# STALO_1.net
KiCad netlist of a schematic drawn in Altium Designer
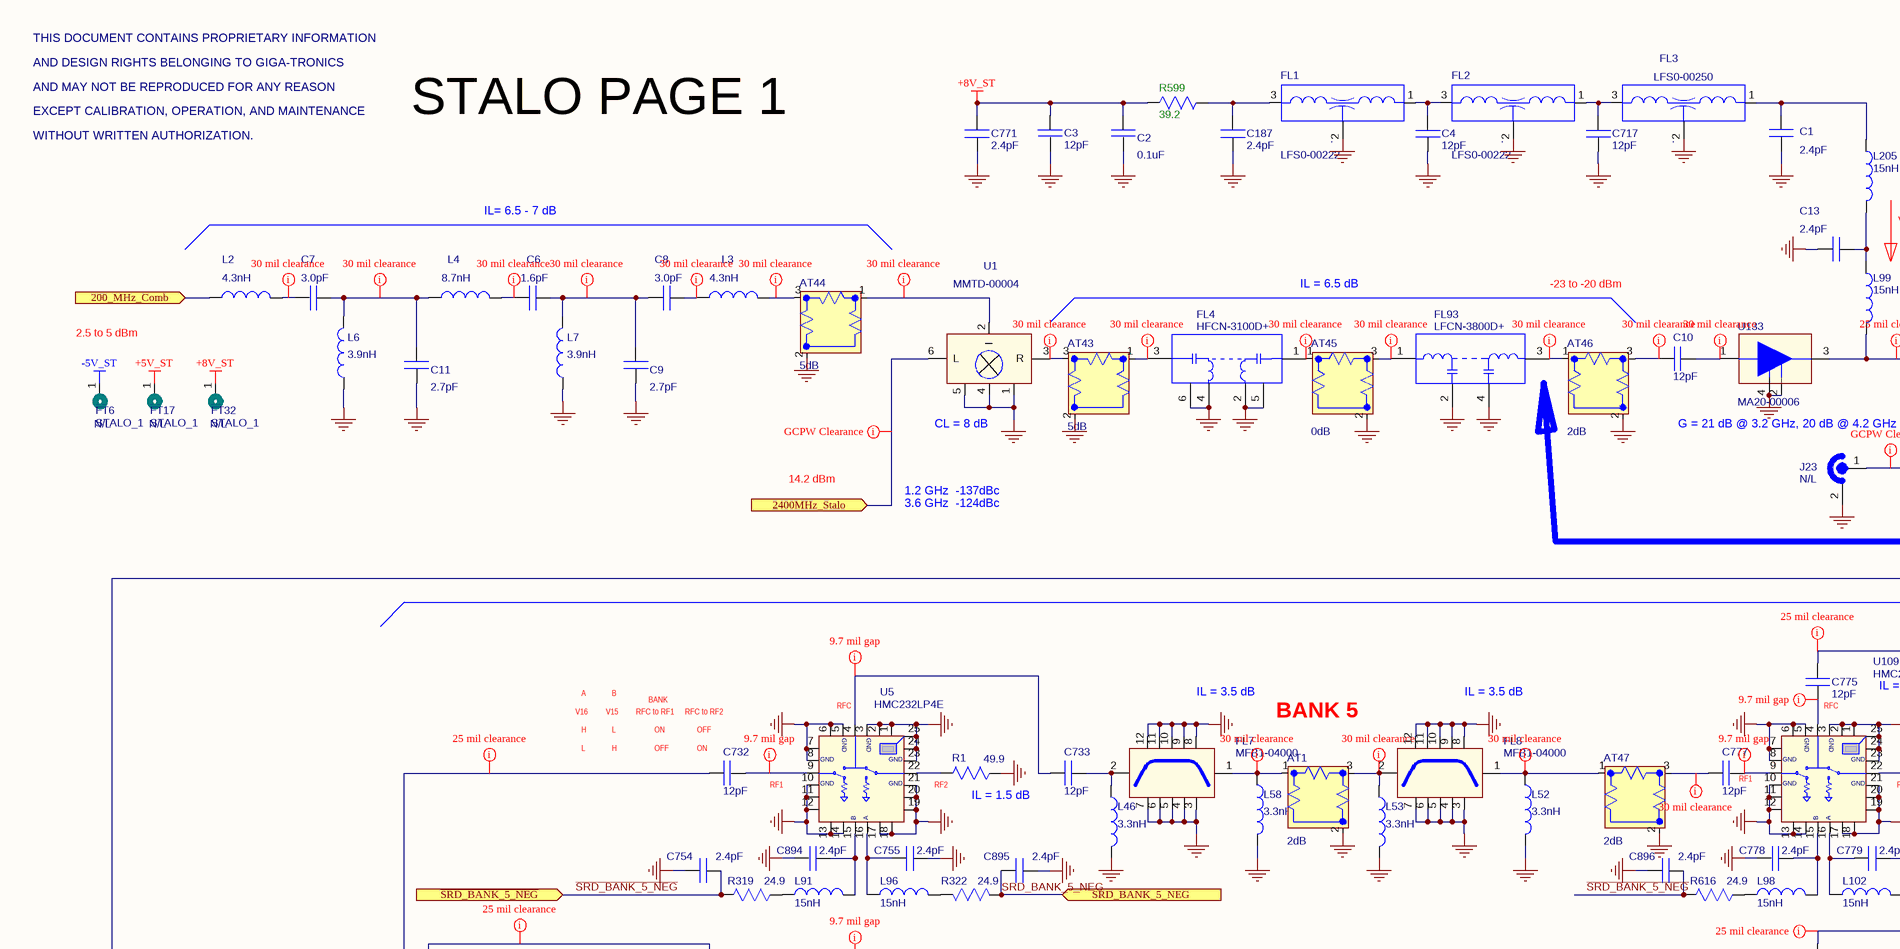
[diagram p0: STALO_1.SchDoc, top left]
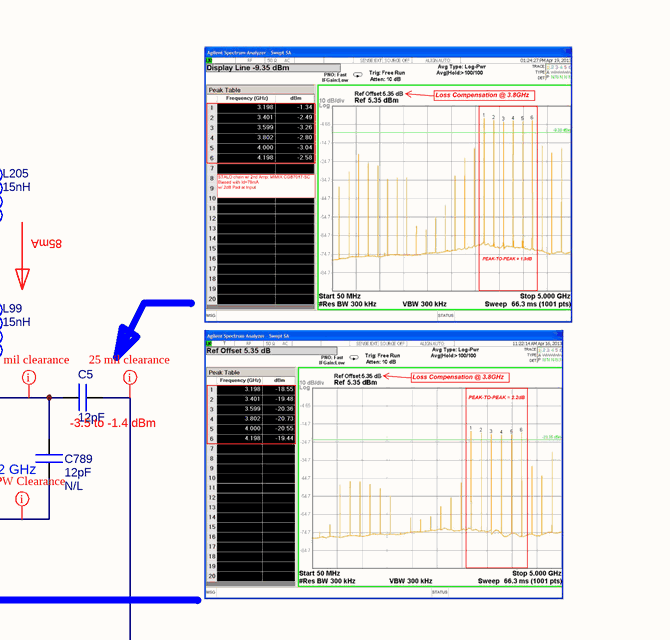
[diagram p1: STALO_1.SchDoc, top right]
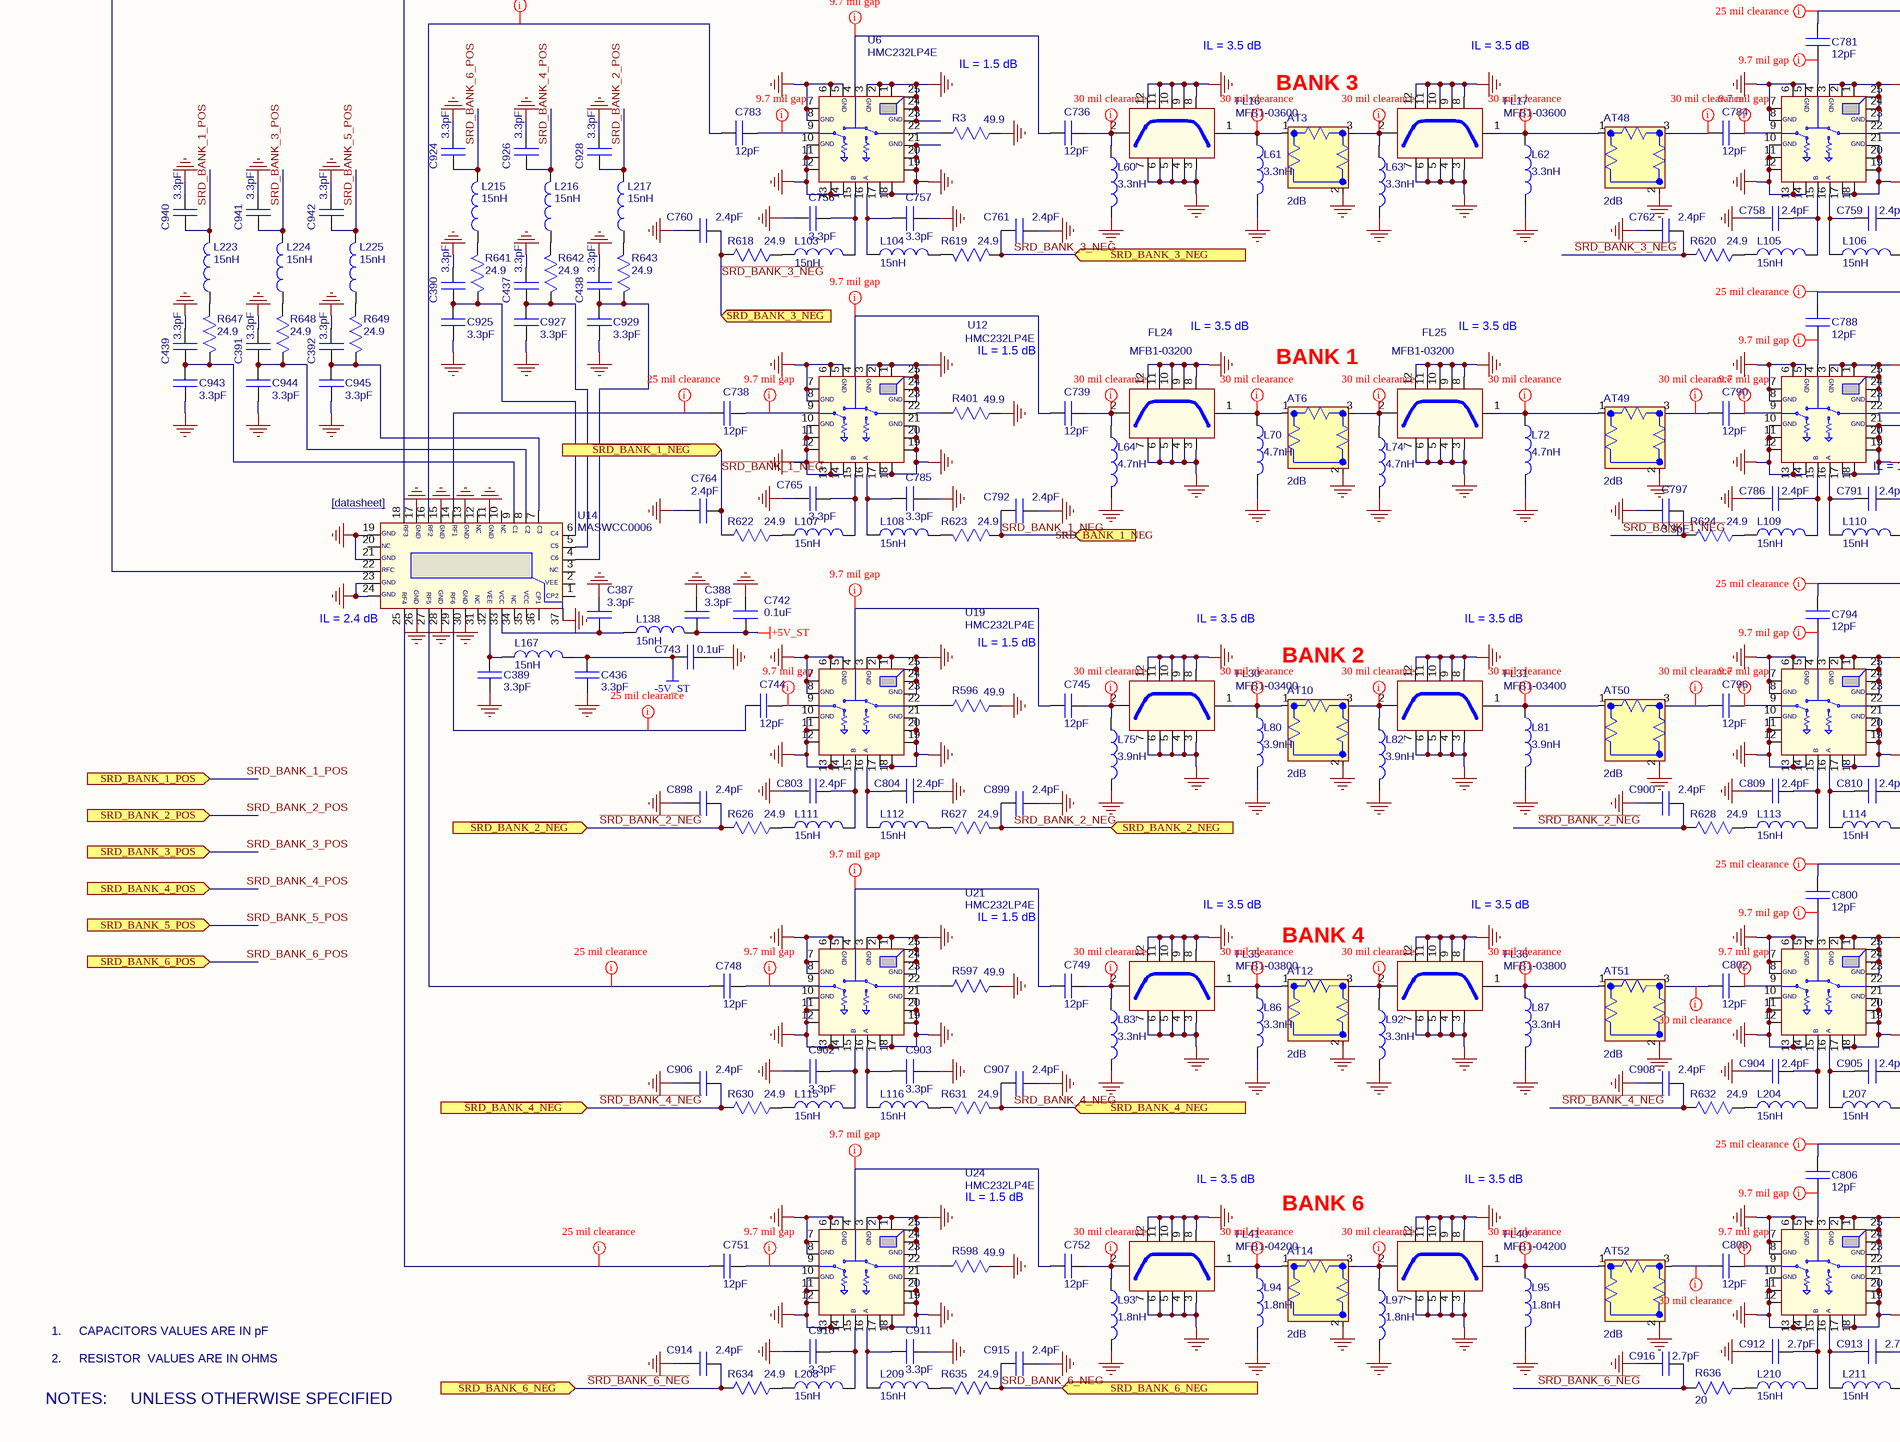
[diagram p2: STALO_1.SchDoc, bottom left]
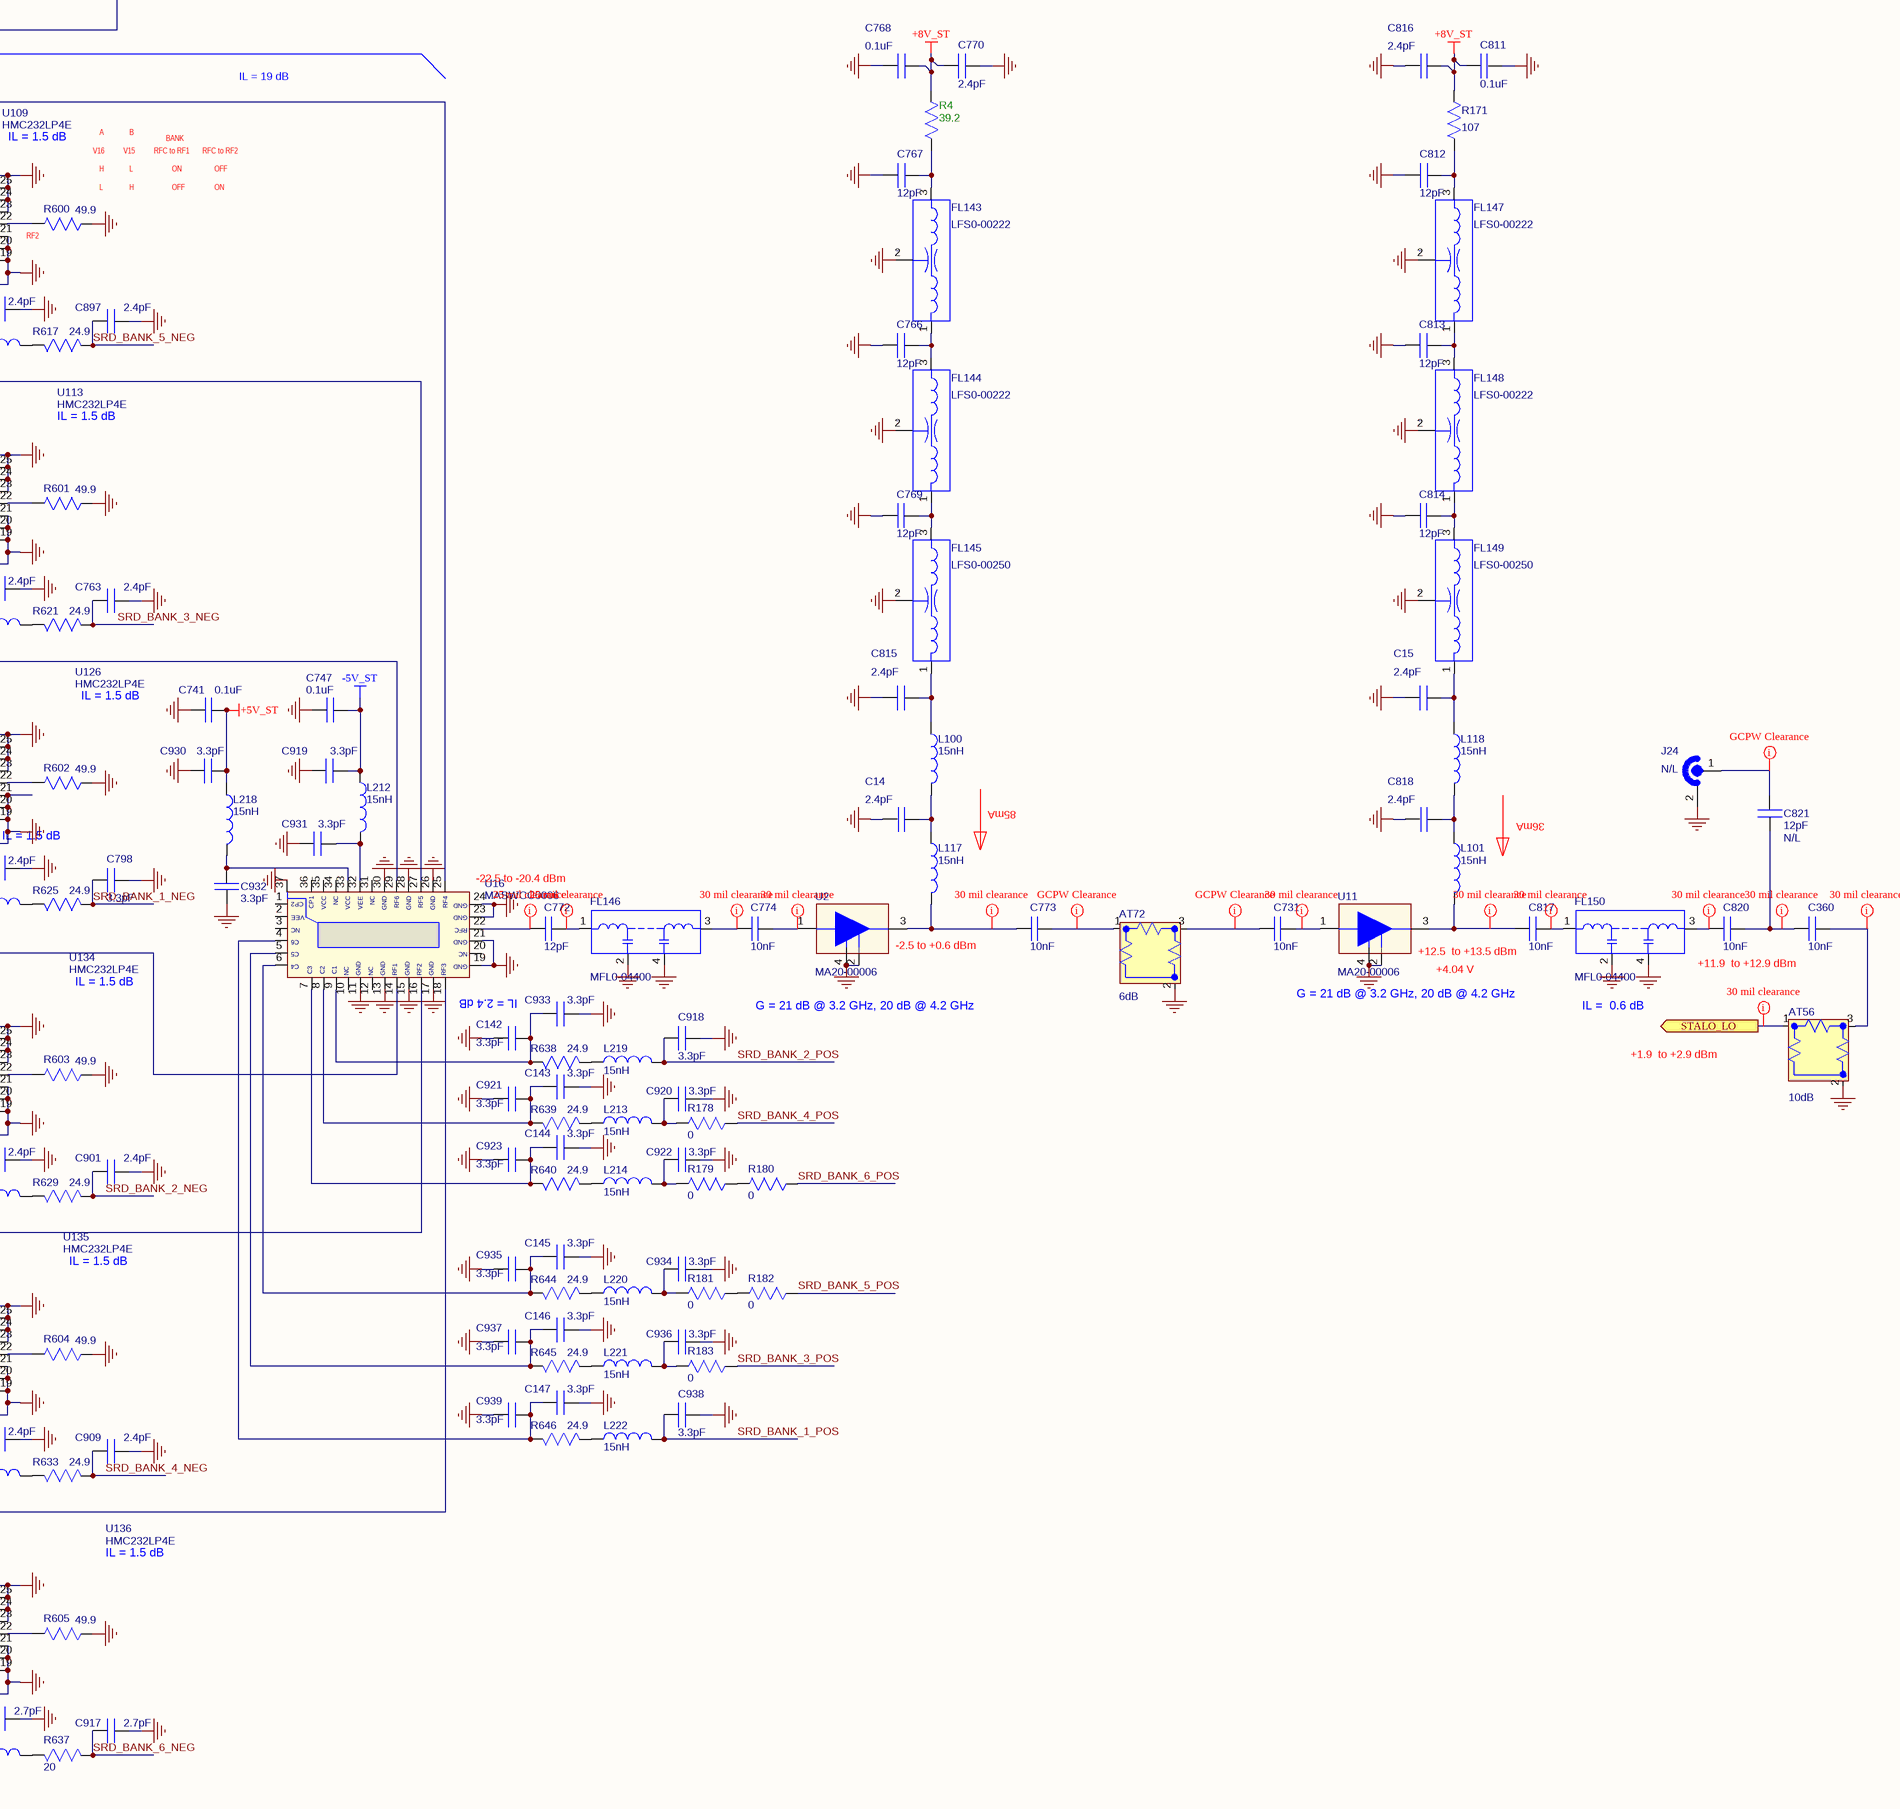
[diagram p3: STALO_1.SchDoc, bottom right]

(export (version "E")
  (design (tool "Eeschema 10.0.6"))
  (components
    (comp (ref "AT1")
      (value "2dB")
      (footprint "ATTN-IMS-0805")
      (description "PAD;CHIP;2dB;+/-.3dB;.08 x .05;50 OHM;FACE DOWN")
      (fields (field (name "APPROVED") "CL"))
      (libsource (lib "Giga-tronics") (part "MPFC-A1002"))
    )
    (comp (ref "AT3")
      (value "2dB")
      (footprint "ATTN-IMS-0805")
      (description "PAD;CHIP;2dB;+/-.3dB;.08 x .05;50 OHM;FACE DOWN")
      (fields (field (name "APPROVED") "CL"))
      (libsource (lib "Giga-tronics") (part "MPFC-A1002"))
    )
    (comp (ref "AT6")
      (value "2dB")
      (footprint "ATTN-IMS-0805")
      (description "PAD;CHIP;2dB;+/-.3dB;.08 x .05;50 OHM;FACE DOWN")
      (fields (field (name "APPROVED") "CL"))
      (libsource (lib "Giga-tronics") (part "MPFC-A1002"))
    )
    (comp (ref "AT10")
      (value "2dB")
      (footprint "ATTN-IMS-0805")
      (description "PAD;CHIP;2dB;+/-.3dB;.08 x .05;50 OHM;FACE DOWN")
      (fields (field (name "APPROVED") "CL"))
      (libsource (lib "Giga-tronics") (part "MPFC-A1002"))
    )
    (comp (ref "AT12")
      (value "2dB")
      (footprint "ATTN-IMS-0805")
      (description "PAD;CHIP;2dB;+/-.3dB;.08 x .05;50 OHM;FACE DOWN")
      (fields (field (name "APPROVED") "CL"))
      (libsource (lib "Giga-tronics") (part "MPFC-A1002"))
    )
    (comp (ref "AT14")
      (value "2dB")
      (footprint "ATTN-IMS-0805")
      (description "PAD;CHIP;2dB;+/-.3dB;.08 x .05;50 OHM;FACE DOWN")
      (fields (field (name "APPROVED") "CL"))
      (libsource (lib "Giga-tronics") (part "MPFC-A1002"))
    )
    (comp (ref "AT43")
      (value "5dB")
      (footprint "ATTN-IMS-0805")
      (description "PAD;CHIP;5dB;+/-.3dB;.08 x .05;50 OHM;FACE DOWN")
      (fields (field (name "APPROVED") "CL"))
      (libsource (lib "Giga-tronics") (part "MPFC-A1005"))
    )
    (comp (ref "AT44")
      (value "5dB")
      (footprint "ATTN-IMS-0805")
      (description "PAD;CHIP;5dB;+/-.3dB;.08 x .05;50 OHM;FACE DOWN")
      (fields (field (name "APPROVED") "CL"))
      (libsource (lib "Giga-tronics") (part "MPFC-A1005"))
    )
    (comp (ref "AT45")
      (value "0dB")
      (footprint "ATTN-IMS-0805")
      (description "PAD;CHIP;0dB;+/-.3dB;.08 x .05;50 OHM;FACE DOWN")
      (fields (field (name "APPROVED") "CL"))
      (libsource (lib "Giga-tronics") (part "MPFC-A1000"))
    )
    (comp (ref "AT46")
      (value "2dB")
      (footprint "ATTN-IMS-0805")
      (description "PAD;CHIP;2dB;+/-.3dB;.08 x .05;50 OHM;FACE DOWN")
      (fields (field (name "APPROVED") "CL"))
      (libsource (lib "Giga-tronics") (part "MPFC-A1002"))
    )
    (comp (ref "AT47")
      (value "2dB")
      (footprint "ATTN-IMS-0805")
      (description "PAD;CHIP;2dB;+/-.3dB;.08 x .05;50 OHM;FACE DOWN")
      (fields (field (name "APPROVED") "CL"))
      (libsource (lib "Giga-tronics") (part "MPFC-A1002"))
    )
    (comp (ref "AT48")
      (value "2dB")
      (footprint "ATTN-IMS-0805")
      (description "PAD;CHIP;2dB;+/-.3dB;.08 x .05;50 OHM;FACE DOWN")
      (fields (field (name "APPROVED") "CL"))
      (libsource (lib "Giga-tronics") (part "MPFC-A1002"))
    )
    (comp (ref "AT49")
      (value "2dB")
      (footprint "ATTN-IMS-0805")
      (description "PAD;CHIP;2dB;+/-.3dB;.08 x .05;50 OHM;FACE DOWN")
      (fields (field (name "APPROVED") "CL"))
      (libsource (lib "Giga-tronics") (part "MPFC-A1002"))
    )
    (comp (ref "AT50")
      (value "2dB")
      (footprint "ATTN-IMS-0805")
      (description "PAD;CHIP;2dB;+/-.3dB;.08 x .05;50 OHM;FACE DOWN")
      (fields (field (name "APPROVED") "CL"))
      (libsource (lib "Giga-tronics") (part "MPFC-A1002"))
    )
    (comp (ref "AT51")
      (value "2dB")
      (footprint "ATTN-IMS-0805")
      (description "PAD;CHIP;2dB;+/-.3dB;.08 x .05;50 OHM;FACE DOWN")
      (fields (field (name "APPROVED") "CL"))
      (libsource (lib "Giga-tronics") (part "MPFC-A1002"))
    )
    (comp (ref "AT52")
      (value "2dB")
      (footprint "ATTN-IMS-0805")
      (description "PAD;CHIP;2dB;+/-.3dB;.08 x .05;50 OHM;FACE DOWN")
      (fields (field (name "APPROVED") "CL"))
      (libsource (lib "Giga-tronics") (part "MPFC-A1002"))
    )
    (comp (ref "AT56")
      (value "10dB")
      (footprint "ATTN-IMS-0805")
      (description "PAD;CHIP;10dB;+/-.3dB;.08 x .05;50 OHM;FACE DOWN")
      (fields (field (name "APPROVED") "CL"))
      (libsource (lib "Giga-tronics") (part "MPFC-A1010"))
    )
    (comp (ref "AT72")
      (value "6dB")
      (footprint "ATTN-IMS-0805")
      (description "PAD;CHIP;6dB;+/-.3dB;.08 x .05;50 OHM;FACE DOWN")
      (fields (field (name "APPROVED") "CL"))
      (libsource (lib "Giga-tronics") (part "MPFC-A1006"))
    )
    (comp (ref "C1")
      (value "2.4pF")
      (footprint "CAP-0402-RF")
      (description "2.4 PF;200V;.05PF;HIGH Q;SMT;CERAMIC;0402")
      (fields (field (name "APPROVED") "CL"))
      (libsource (lib "Giga-tronics") (part "CK41-00024"))
    )
    (comp (ref "C2")
      (value "0.1uF")
      (footprint "CAP-0603-H035-N")
      (description ".1UF;10%;X7R;16V;CHIP;0603")
      (fields (field (name "APPROVED") "CL"))
      (libsource (lib "Giga-tronics") (part "CK45-04100"))
    )
    (comp (ref "C3")
      (value "12pF")
      (footprint "CAP-0402-N")
      (description "12 PF;5%;COG;>50V;CHIP;0402")
      (fields (field (name "APPROVED") "CL"))
      (libsource (lib "Giga-tronics") (part "CK40-00120"))
    )
    (comp (ref "C4")
      (value "12pF")
      (footprint "CAP-0402-N")
      (description "12 PF;5%;COG;>50V;CHIP;0402")
      (fields (field (name "APPROVED") "CL"))
      (libsource (lib "Giga-tronics") (part "CK40-00120"))
    )
    (comp (ref "C5")
      (value "12pF")
      (footprint "CAP-0402-N")
      (description "12 PF;5%;COG;>50V;CHIP;0402")
      (fields (field (name "APPROVED") "CL"))
      (libsource (lib "Giga-tronics") (part "CK40-00120"))
    )
    (comp (ref "C6")
      (value "1.6pF")
      (footprint "CAP-0402-RF")
      (description "1.6 PF;200V;.05PF;HIGH Q;SMT;CERAMIC;0402")
      (fields (field (name "APPROVED") "CL"))
      (libsource (lib "Giga-tronics") (part "CK41-00016"))
    )
    (comp (ref "C7")
      (value "3.0pF")
      (footprint "CAP-0402-RF")
      (description "3.0 PF;200V;.05PF;HIGH Q;SMT;CERAMIC;0402")
      (fields (field (name "APPROVED") "CL"))
      (libsource (lib "Giga-tronics") (part "CK41-00030"))
    )
    (comp (ref "C8")
      (value "3.0pF")
      (footprint "CAP-0402-RF")
      (description "3.0 PF;200V;.05PF;HIGH Q;SMT;CERAMIC;0402")
      (fields (field (name "APPROVED") "CL"))
      (libsource (lib "Giga-tronics") (part "CK41-00030"))
    )
    (comp (ref "C9")
      (value "2.7pF")
      (footprint "CAP-0402-RF")
      (description "2.7 PF;200V;.05PF;HIGH Q;SMT;CERAMIC;0402")
      (fields (field (name "APPROVED") "CL"))
      (libsource (lib "Giga-tronics") (part "CK41-00027"))
    )
    (comp (ref "C10")
      (value "12pF")
      (footprint "CAP-0402-N")
      (description "12 PF;5%;COG;>50V;CHIP;0402")
      (fields (field (name "APPROVED") "CL"))
      (libsource (lib "Giga-tronics") (part "CK40-00120"))
    )
    (comp (ref "C11")
      (value "2.7pF")
      (footprint "CAP-0402-RF")
      (description "2.7 PF;200V;.05PF;HIGH Q;SMT;CERAMIC;0402")
      (fields (field (name "APPROVED") "CL"))
      (libsource (lib "Giga-tronics") (part "CK41-00027"))
    )
    (comp (ref "C13")
      (value "2.4pF")
      (footprint "CAP-0402-RF")
      (description "2.4 PF;200V;.05PF;HIGH Q;SMT;CERAMIC;0402")
      (fields (field (name "APPROVED") "CL"))
      (libsource (lib "Giga-tronics") (part "CK41-00024"))
    )
    (comp (ref "C14")
      (value "2.4pF")
      (footprint "CAP-0402-RF")
      (description "2.4 PF;200V;.05PF;HIGH Q;SMT;CERAMIC;0402")
      (fields (field (name "APPROVED") "CL"))
      (libsource (lib "Giga-tronics") (part "CK41-00024"))
    )
    (comp (ref "C15")
      (value "2.4pF")
      (footprint "CAP-0402-RF")
      (description "2.4 PF;200V;.05PF;HIGH Q;SMT;CERAMIC;0402")
      (fields (field (name "APPROVED") "CL"))
      (libsource (lib "Giga-tronics") (part "CK41-00024"))
    )
    (comp (ref "C142")
      (value "3.3pF")
      (footprint "CAP-0201-N")
      (description "3.3pF;5%;COG;50V;CHIP;0201")
      (fields (field (name "APPROVED") "CL"))
      (libsource (lib "Giga-tronics") (part "CK35-00033"))
    )
    (comp (ref "C143")
      (value "3.3pF")
      (footprint "CAP-0201-N")
      (description "3.3pF;5%;COG;50V;CHIP;0201")
      (fields (field (name "APPROVED") "CL"))
      (libsource (lib "Giga-tronics") (part "CK35-00033"))
    )
    (comp (ref "C144")
      (value "3.3pF")
      (footprint "CAP-0201-N")
      (description "3.3pF;5%;COG;50V;CHIP;0201")
      (fields (field (name "APPROVED") "CL"))
      (libsource (lib "Giga-tronics") (part "CK35-00033"))
    )
    (comp (ref "C145")
      (value "3.3pF")
      (footprint "CAP-0201-N")
      (description "3.3pF;5%;COG;50V;CHIP;0201")
      (fields (field (name "APPROVED") "CL"))
      (libsource (lib "Giga-tronics") (part "CK35-00033"))
    )
    (comp (ref "C146")
      (value "3.3pF")
      (footprint "CAP-0201-N")
      (description "3.3pF;5%;COG;50V;CHIP;0201")
      (fields (field (name "APPROVED") "CL"))
      (libsource (lib "Giga-tronics") (part "CK35-00033"))
    )
    (comp (ref "C147")
      (value "3.3pF")
      (footprint "CAP-0201-N")
      (description "3.3pF;5%;COG;50V;CHIP;0201")
      (fields (field (name "APPROVED") "CL"))
      (libsource (lib "Giga-tronics") (part "CK35-00033"))
    )
    (comp (ref "C187")
      (value "2.4pF")
      (footprint "CAP-0402-RF")
      (description "2.4 PF;200V;.05PF;HIGH Q;SMT;CERAMIC;0402")
      (fields (field (name "APPROVED") "CL"))
      (libsource (lib "Giga-tronics") (part "CK41-00024"))
    )
    (comp (ref "C360")
      (value "10nF")
      (footprint "CAP-0402-N")
      (description "10nF;10%;X7R;16 WVDC;CHIP;0402")
      (fields (field (name "APPROVED") "CL"))
      (libsource (lib "Giga-tronics") (part "TCC3-03100"))
    )
    (comp (ref "C387")
      (value "3.3pF")
      (footprint "CAP-0201-N")
      (description "3.3pF;5%;COG;50V;CHIP;0201")
      (fields (field (name "APPROVED") "CL"))
      (libsource (lib "Giga-tronics") (part "CK35-00033"))
    )
    (comp (ref "C388")
      (value "3.3pF")
      (footprint "CAP-0201-N")
      (description "3.3pF;5%;COG;50V;CHIP;0201")
      (fields (field (name "APPROVED") "CL"))
      (libsource (lib "Giga-tronics") (part "CK35-00033"))
    )
    (comp (ref "C389")
      (value "3.3pF")
      (footprint "CAP-0201-N")
      (description "3.3pF;5%;COG;50V;CHIP;0201")
      (fields (field (name "APPROVED") "CL"))
      (libsource (lib "Giga-tronics") (part "CK35-00033"))
    )
    (comp (ref "C390")
      (value "3.3pF")
      (footprint "CAP-0201-N")
      (description "3.3pF;5%;COG;50V;CHIP;0201")
      (fields (field (name "APPROVED") "CL"))
      (libsource (lib "Giga-tronics") (part "CK35-00033"))
    )
    (comp (ref "C391")
      (value "3.3pF")
      (footprint "CAP-0201-N")
      (description "3.3pF;5%;COG;50V;CHIP;0201")
      (fields (field (name "APPROVED") "CL"))
      (libsource (lib "Giga-tronics") (part "CK35-00033"))
    )
    (comp (ref "C392")
      (value "3.3pF")
      (footprint "CAP-0201-N")
      (description "3.3pF;5%;COG;50V;CHIP;0201")
      (fields (field (name "APPROVED") "CL"))
      (libsource (lib "Giga-tronics") (part "CK35-00033"))
    )
    (comp (ref "C436")
      (value "3.3pF")
      (footprint "CAP-0201-N")
      (description "3.3pF;5%;COG;50V;CHIP;0201")
      (fields (field (name "APPROVED") "CL"))
      (libsource (lib "Giga-tronics") (part "CK35-00033"))
    )
    (comp (ref "C437")
      (value "3.3pF")
      (footprint "CAP-0201-N")
      (description "3.3pF;5%;COG;50V;CHIP;0201")
      (fields (field (name "APPROVED") "CL"))
      (libsource (lib "Giga-tronics") (part "CK35-00033"))
    )
    (comp (ref "C438")
      (value "3.3pF")
      (footprint "CAP-0201-N")
      (description "3.3pF;5%;COG;50V;CHIP;0201")
      (fields (field (name "APPROVED") "CL"))
      (libsource (lib "Giga-tronics") (part "CK35-00033"))
    )
    (comp (ref "C439")
      (value "3.3pF")
      (footprint "CAP-0201-N")
      (description "3.3pF;5%;COG;50V;CHIP;0201")
      (fields (field (name "APPROVED") "CL"))
      (libsource (lib "Giga-tronics") (part "CK35-00033"))
    )
    (comp (ref "C717")
      (value "12pF")
      (footprint "CAP-0402-N")
      (description "12 PF;5%;COG;>50V;CHIP;0402")
      (fields (field (name "APPROVED") "CL"))
      (libsource (lib "Giga-tronics") (part "CK40-00120"))
    )
    (comp (ref "C731")
      (value "10nF")
      (footprint "CAP-0402-N")
      (description "10nF;10%;X7R;16 WVDC;CHIP;0402")
      (fields (field (name "APPROVED") "CL"))
      (libsource (lib "Giga-tronics") (part "TCC3-03100"))
    )
    (comp (ref "C732")
      (value "12pF")
      (footprint "CAP-0402-N")
      (description "12 PF;5%;COG;>50V;CHIP;0402")
      (fields (field (name "APPROVED") "CL"))
      (libsource (lib "Giga-tronics") (part "CK40-00120"))
    )
    (comp (ref "C733")
      (value "12pF")
      (footprint "CAP-0402-N")
      (description "12 PF;5%;COG;>50V;CHIP;0402")
      (fields (field (name "APPROVED") "CL"))
      (libsource (lib "Giga-tronics") (part "CK40-00120"))
    )
    (comp (ref "C736")
      (value "12pF")
      (footprint "CAP-0402-N")
      (description "12 PF;5%;COG;>50V;CHIP;0402")
      (fields (field (name "APPROVED") "CL"))
      (libsource (lib "Giga-tronics") (part "CK40-00120"))
    )
    (comp (ref "C738")
      (value "12pF")
      (footprint "CAP-0402-N")
      (description "12 PF;5%;COG;>50V;CHIP;0402")
      (fields (field (name "APPROVED") "CL"))
      (libsource (lib "Giga-tronics") (part "CK40-00120"))
    )
    (comp (ref "C739")
      (value "12pF")
      (footprint "CAP-0402-N")
      (description "12 PF;5%;COG;>50V;CHIP;0402")
      (fields (field (name "APPROVED") "CL"))
      (libsource (lib "Giga-tronics") (part "CK40-00120"))
    )
    (comp (ref "C741")
      (value "0.1uF")
      (footprint "CAP-0402-N")
      (description ".1 UF,10%;X7R;16V,CHIP;0402")
      (fields (field (name "APPROVED") "CL"))
      (libsource (lib "Giga-tronics") (part "CK40-04100"))
    )
    (comp (ref "C742")
      (value "0.1uF")
      (footprint "CAP-0402-N")
      (description ".1 UF,10%;X7R;16V,CHIP;0402")
      (fields (field (name "APPROVED") "CL"))
      (libsource (lib "Giga-tronics") (part "CK40-04100"))
    )
    (comp (ref "C743")
      (value "0.1uF")
      (footprint "CAP-0402-N")
      (description ".1 UF,10%;X7R;16V,CHIP;0402")
      (fields (field (name "APPROVED") "CL"))
      (libsource (lib "Giga-tronics") (part "CK40-04100"))
    )
    (comp (ref "C744")
      (value "12pF")
      (footprint "CAP-0402-N")
      (description "12 PF;5%;COG;>50V;CHIP;0402")
      (fields (field (name "APPROVED") "CL"))
      (libsource (lib "Giga-tronics") (part "CK40-00120"))
    )
    (comp (ref "C745")
      (value "12pF")
      (footprint "CAP-0402-N")
      (description "12 PF;5%;COG;>50V;CHIP;0402")
      (fields (field (name "APPROVED") "CL"))
      (libsource (lib "Giga-tronics") (part "CK40-00120"))
    )
    (comp (ref "C747")
      (value "0.1uF")
      (footprint "CAP-0402-N")
      (description ".1 UF,10%;X7R;16V,CHIP;0402")
      (fields (field (name "APPROVED") "CL"))
      (libsource (lib "Giga-tronics") (part "CK40-04100"))
    )
    (comp (ref "C748")
      (value "12pF")
      (footprint "CAP-0402-N")
      (description "12 PF;5%;COG;>50V;CHIP;0402")
      (fields (field (name "APPROVED") "CL"))
      (libsource (lib "Giga-tronics") (part "CK40-00120"))
    )
    (comp (ref "C749")
      (value "12pF")
      (footprint "CAP-0402-N")
      (description "12 PF;5%;COG;>50V;CHIP;0402")
      (fields (field (name "APPROVED") "CL"))
      (libsource (lib "Giga-tronics") (part "CK40-00120"))
    )
    (comp (ref "C751")
      (value "12pF")
      (footprint "CAP-0402-N")
      (description "12 PF;5%;COG;>50V;CHIP;0402")
      (fields (field (name "APPROVED") "CL"))
      (libsource (lib "Giga-tronics") (part "CK40-00120"))
    )
    (comp (ref "C752")
      (value "12pF")
      (footprint "CAP-0402-N")
      (description "12 PF;5%;COG;>50V;CHIP;0402")
      (fields (field (name "APPROVED") "CL"))
      (libsource (lib "Giga-tronics") (part "CK40-00120"))
    )
    (comp (ref "C754")
      (value "2.4pF")
      (footprint "CAP-0402-RF")
      (description "2.4 PF;200V;.05PF;HIGH Q;SMT;CERAMIC;0402")
      (fields (field (name "APPROVED") "CL"))
      (libsource (lib "Giga-tronics") (part "CK41-00024"))
    )
    (comp (ref "C755")
      (value "2.4pF")
      (footprint "CAP-0402-RF")
      (description "2.4 PF;200V;.05PF;HIGH Q;SMT;CERAMIC;0402")
      (fields (field (name "APPROVED") "CL"))
      (libsource (lib "Giga-tronics") (part "CK41-00024"))
    )
    (comp (ref "C756")
      (value "3.3pF")
      (footprint "CAP-0201-N")
      (description "3.3pF;5%;COG;50V;CHIP;0201")
      (fields (field (name "APPROVED") "CL"))
      (libsource (lib "Giga-tronics") (part "CK35-00033"))
    )
    (comp (ref "C757")
      (value "3.3pF")
      (footprint "CAP-0201-N")
      (description "3.3pF;5%;COG;50V;CHIP;0201")
      (fields (field (name "APPROVED") "CL"))
      (libsource (lib "Giga-tronics") (part "CK35-00033"))
    )
    (comp (ref "C758")
      (value "2.4pF")
      (footprint "CAP-0402-RF")
      (description "2.4 PF;200V;.05PF;HIGH Q;SMT;CERAMIC;0402")
      (fields (field (name "APPROVED") "CL"))
      (libsource (lib "Giga-tronics") (part "CK41-00024"))
    )
    (comp (ref "C759")
      (value "2.4pF")
      (footprint "CAP-0402-RF")
      (description "2.4 PF;200V;.05PF;HIGH Q;SMT;CERAMIC;0402")
      (fields (field (name "APPROVED") "CL"))
      (libsource (lib "Giga-tronics") (part "CK41-00024"))
    )
    (comp (ref "C760")
      (value "2.4pF")
      (footprint "CAP-0402-RF")
      (description "2.4 PF;200V;.05PF;HIGH Q;SMT;CERAMIC;0402")
      (fields (field (name "APPROVED") "CL"))
      (libsource (lib "Giga-tronics") (part "CK41-00024"))
    )
    (comp (ref "C761")
      (value "2.4pF")
      (footprint "CAP-0402-RF")
      (description "2.4 PF;200V;.05PF;HIGH Q;SMT;CERAMIC;0402")
      (fields (field (name "APPROVED") "CL"))
      (libsource (lib "Giga-tronics") (part "CK41-00024"))
    )
    (comp (ref "C762")
      (value "2.4pF")
      (footprint "CAP-0402-RF")
      (description "2.4 PF;200V;.05PF;HIGH Q;SMT;CERAMIC;0402")
      (fields (field (name "APPROVED") "CL"))
      (libsource (lib "Giga-tronics") (part "CK41-00024"))
    )
    (comp (ref "C763")
      (value "2.4pF")
      (footprint "CAP-0402-RF")
      (description "2.4 PF;200V;.05PF;HIGH Q;SMT;CERAMIC;0402")
      (fields (field (name "APPROVED") "CL"))
      (libsource (lib "Giga-tronics") (part "CK41-00024"))
    )
    (comp (ref "C764")
      (value "2.4pF")
      (footprint "CAP-0402-RF")
      (description "2.4 PF;200V;.05PF;HIGH Q;SMT;CERAMIC;0402")
      (fields (field (name "APPROVED") "CL"))
      (libsource (lib "Giga-tronics") (part "CK41-00024"))
    )
    (comp (ref "C765")
      (value "3.3pF")
      (footprint "CAP-0201-N")
      (description "3.3pF;5%;COG;50V;CHIP;0201")
      (fields (field (name "APPROVED") "CL"))
      (libsource (lib "Giga-tronics") (part "CK35-00033"))
    )
    (comp (ref "C766")
      (value "12pF")
      (footprint "CAP-0402-N")
      (description "12 PF;5%;COG;>50V;CHIP;0402")
      (fields (field (name "APPROVED") "CL"))
      (libsource (lib "Giga-tronics") (part "CK40-00120"))
    )
    (comp (ref "C767")
      (value "12pF")
      (footprint "CAP-0402-N")
      (description "12 PF;5%;COG;>50V;CHIP;0402")
      (fields (field (name "APPROVED") "CL"))
      (libsource (lib "Giga-tronics") (part "CK40-00120"))
    )
    (comp (ref "C768")
      (value "0.1uF")
      (footprint "CAP-0603-H035-N")
      (description ".1UF;10%;X7R;16V;CHIP;0603")
      (fields (field (name "APPROVED") "CL"))
      (libsource (lib "Giga-tronics") (part "CK45-04100"))
    )
    (comp (ref "C769")
      (value "12pF")
      (footprint "CAP-0402-N")
      (description "12 PF;5%;COG;>50V;CHIP;0402")
      (fields (field (name "APPROVED") "CL"))
      (libsource (lib "Giga-tronics") (part "CK40-00120"))
    )
    (comp (ref "C770")
      (value "2.4pF")
      (footprint "CAP-0402-RF")
      (description "2.4 PF;200V;.05PF;HIGH Q;SMT;CERAMIC;0402")
      (fields (field (name "APPROVED") "CL"))
      (libsource (lib "Giga-tronics") (part "CK41-00024"))
    )
    (comp (ref "C771")
      (value "2.4pF")
      (footprint "CAP-0402-RF")
      (description "2.4 PF;200V;.05PF;HIGH Q;SMT;CERAMIC;0402")
      (fields (field (name "APPROVED") "CL"))
      (libsource (lib "Giga-tronics") (part "CK41-00024"))
    )
    (comp (ref "C772")
      (value "12pF")
      (footprint "CAP-0402-N")
      (description "12 PF;5%;COG;>50V;CHIP;0402")
      (fields (field (name "APPROVED") "CL"))
      (libsource (lib "Giga-tronics") (part "CK40-00120"))
    )
    (comp (ref "C773")
      (value "10nF")
      (footprint "CAP-0402-N")
      (description "10nF;10%;X7R;16 WVDC;CHIP;0402")
      (fields (field (name "APPROVED") "CL"))
      (libsource (lib "Giga-tronics") (part "TCC3-03100"))
    )
    (comp (ref "C774")
      (value "10nF")
      (footprint "CAP-0402-N")
      (description "10nF;10%;X7R;16 WVDC;CHIP;0402")
      (fields (field (name "APPROVED") "CL"))
      (libsource (lib "Giga-tronics") (part "TCC3-03100"))
    )
    (comp (ref "C775")
      (value "12pF")
      (footprint "CAP-0402-N")
      (description "12 PF;5%;COG;>50V;CHIP;0402")
      (fields (field (name "APPROVED") "CL"))
      (libsource (lib "Giga-tronics") (part "CK40-00120"))
    )
    (comp (ref "C777")
      (value "12pF")
      (footprint "CAP-0402-N")
      (description "12 PF;5%;COG;>50V;CHIP;0402")
      (fields (field (name "APPROVED") "CL"))
      (libsource (lib "Giga-tronics") (part "CK40-00120"))
    )
    (comp (ref "C778")
      (value "2.4pF")
      (footprint "CAP-0402-RF")
      (description "2.4 PF;200V;.05PF;HIGH Q;SMT;CERAMIC;0402")
      (fields (field (name "APPROVED") "CL"))
      (libsource (lib "Giga-tronics") (part "CK41-00024"))
    )
    (comp (ref "C779")
      (value "2.4pF")
      (footprint "CAP-0402-RF")
      (description "2.4 PF;200V;.05PF;HIGH Q;SMT;CERAMIC;0402")
      (fields (field (name "APPROVED") "CL"))
      (libsource (lib "Giga-tronics") (part "CK41-00024"))
    )
    (comp (ref "C781")
      (value "12pF")
      (footprint "CAP-0402-N")
      (description "12 PF;5%;COG;>50V;CHIP;0402")
      (fields (field (name "APPROVED") "CL"))
      (libsource (lib "Giga-tronics") (part "CK40-00120"))
    )
    (comp (ref "C783")
      (value "12pF")
      (footprint "CAP-0402-N")
      (description "12 PF;5%;COG;>50V;CHIP;0402")
      (fields (field (name "APPROVED") "CL"))
      (libsource (lib "Giga-tronics") (part "CK40-00120"))
    )
    (comp (ref "C784")
      (value "12pF")
      (footprint "CAP-0402-N")
      (description "12 PF;5%;COG;>50V;CHIP;0402")
      (fields (field (name "APPROVED") "CL"))
      (libsource (lib "Giga-tronics") (part "CK40-00120"))
    )
    (comp (ref "C785")
      (value "3.3pF")
      (footprint "CAP-0201-N")
      (description "3.3pF;5%;COG;50V;CHIP;0201")
      (fields (field (name "APPROVED") "CL"))
      (libsource (lib "Giga-tronics") (part "CK35-00033"))
    )
    (comp (ref "C786")
      (value "2.4pF")
      (footprint "CAP-0402-RF")
      (description "2.4 PF;200V;.05PF;HIGH Q;SMT;CERAMIC;0402")
      (fields (field (name "APPROVED") "CL"))
      (libsource (lib "Giga-tronics") (part "CK41-00024"))
    )
    (comp (ref "C788")
      (value "12pF")
      (footprint "CAP-0402-N")
      (description "12 PF;5%;COG;>50V;CHIP;0402")
      (fields (field (name "APPROVED") "CL"))
      (libsource (lib "Giga-tronics") (part "CK40-00120"))
    )
    (comp (ref "C789")
      (value "12pF")
      (footprint "CAP-0402-N")
      (description "12 PF;5%;COG;>50V;CHIP;0402")
      (fields (field (name "NOLOAD") "N/L") (field (name "APPROVED") "CL"))
      (libsource (lib "Giga-tronics") (part "CK40-00120"))
    )
    (comp (ref "C790")
      (value "12pF")
      (footprint "CAP-0402-N")
      (description "12 PF;5%;COG;>50V;CHIP;0402")
      (fields (field (name "APPROVED") "CL"))
      (libsource (lib "Giga-tronics") (part "CK40-00120"))
    )
    (comp (ref "C791")
      (value "2.4pF")
      (footprint "CAP-0402-RF")
      (description "2.4 PF;200V;.05PF;HIGH Q;SMT;CERAMIC;0402")
      (fields (field (name "APPROVED") "CL"))
      (libsource (lib "Giga-tronics") (part "CK41-00024"))
    )
    (comp (ref "C792")
      (value "2.4pF")
      (footprint "CAP-0402-RF")
      (description "2.4 PF;200V;.05PF;HIGH Q;SMT;CERAMIC;0402")
      (fields (field (name "APPROVED") "CL"))
      (libsource (lib "Giga-tronics") (part "CK41-00024"))
    )
    (comp (ref "C794")
      (value "12pF")
      (footprint "CAP-0402-N")
      (description "12 PF;5%;COG;>50V;CHIP;0402")
      (fields (field (name "APPROVED") "CL"))
      (libsource (lib "Giga-tronics") (part "CK40-00120"))
    )
    (comp (ref "C796")
      (value "12pF")
      (footprint "CAP-0402-N")
      (description "12 PF;5%;COG;>50V;CHIP;0402")
      (fields (field (name "APPROVED") "CL"))
      (libsource (lib "Giga-tronics") (part "CK40-00120"))
    )
    (comp (ref "C797")
      (value "3.3pF")
      (footprint "CAP-0201-N")
      (description "3.3pF;5%;COG;50V;CHIP;0201")
      (fields (field (name "APPROVED") "CL"))
      (libsource (lib "Giga-tronics") (part "CK35-00033"))
    )
    (comp (ref "C798")
      (value "3.3pF")
      (footprint "CAP-0201-N")
      (description "3.3pF;5%;COG;50V;CHIP;0201")
      (fields (field (name "APPROVED") "CL"))
      (libsource (lib "Giga-tronics") (part "CK35-00033"))
    )
    (comp (ref "C800")
      (value "12pF")
      (footprint "CAP-0402-N")
      (description "12 PF;5%;COG;>50V;CHIP;0402")
      (fields (field (name "APPROVED") "CL"))
      (libsource (lib "Giga-tronics") (part "CK40-00120"))
    )
    (comp (ref "C802")
      (value "12pF")
      (footprint "CAP-0402-N")
      (description "12 PF;5%;COG;>50V;CHIP;0402")
      (fields (field (name "APPROVED") "CL"))
      (libsource (lib "Giga-tronics") (part "CK40-00120"))
    )
    (comp (ref "C803")
      (value "2.4pF")
      (footprint "CAP-0402-RF")
      (description "2.4 PF;200V;.05PF;HIGH Q;SMT;CERAMIC;0402")
      (fields (field (name "APPROVED") "CL"))
      (libsource (lib "Giga-tronics") (part "CK41-00024"))
    )
    (comp (ref "C804")
      (value "2.4pF")
      (footprint "CAP-0402-RF")
      (description "2.4 PF;200V;.05PF;HIGH Q;SMT;CERAMIC;0402")
      (fields (field (name "APPROVED") "CL"))
      (libsource (lib "Giga-tronics") (part "CK41-00024"))
    )
    (comp (ref "C806")
      (value "12pF")
      (footprint "CAP-0402-N")
      (description "12 PF;5%;COG;>50V;CHIP;0402")
      (fields (field (name "APPROVED") "CL"))
      (libsource (lib "Giga-tronics") (part "CK40-00120"))
    )
    (comp (ref "C808")
      (value "12pF")
      (footprint "CAP-0402-N")
      (description "12 PF;5%;COG;>50V;CHIP;0402")
      (fields (field (name "APPROVED") "CL"))
      (libsource (lib "Giga-tronics") (part "CK40-00120"))
    )
    (comp (ref "C809")
      (value "2.4pF")
      (footprint "CAP-0402-RF")
      (description "2.4 PF;200V;.05PF;HIGH Q;SMT;CERAMIC;0402")
      (fields (field (name "APPROVED") "CL"))
      (libsource (lib "Giga-tronics") (part "CK41-00024"))
    )
    (comp (ref "C810")
      (value "2.4pF")
      (footprint "CAP-0402-RF")
      (description "2.4 PF;200V;.05PF;HIGH Q;SMT;CERAMIC;0402")
      (fields (field (name "APPROVED") "CL"))
      (libsource (lib "Giga-tronics") (part "CK41-00024"))
    )
    (comp (ref "C811")
      (value "0.1uF")
      (footprint "CAP-0603-H035-N")
      (description ".1UF;10%;X7R;16V;CHIP;0603")
      (fields (field (name "APPROVED") "CL"))
      (libsource (lib "Giga-tronics") (part "CK45-04100"))
    )
    (comp (ref "C812")
      (value "12pF")
      (footprint "CAP-0402-N")
      (description "12 PF;5%;COG;>50V;CHIP;0402")
      (fields (field (name "APPROVED") "CL"))
      (libsource (lib "Giga-tronics") (part "CK40-00120"))
    )
    (comp (ref "C813")
      (value "12pF")
      (footprint "CAP-0402-N")
      (description "12 PF;5%;COG;>50V;CHIP;0402")
      (fields (field (name "APPROVED") "CL"))
      (libsource (lib "Giga-tronics") (part "CK40-00120"))
    )
    (comp (ref "C814")
      (value "12pF")
      (footprint "CAP-0402-N")
      (description "12 PF;5%;COG;>50V;CHIP;0402")
      (fields (field (name "APPROVED") "CL"))
      (libsource (lib "Giga-tronics") (part "CK40-00120"))
    )
    (comp (ref "C815")
      (value "2.4pF")
      (footprint "CAP-0402-RF")
      (description "2.4 PF;200V;.05PF;HIGH Q;SMT;CERAMIC;0402")
      (fields (field (name "APPROVED") "CL"))
      (libsource (lib "Giga-tronics") (part "CK41-00024"))
    )
    (comp (ref "C816")
      (value "2.4pF")
      (footprint "CAP-0402-RF")
      (description "2.4 PF;200V;.05PF;HIGH Q;SMT;CERAMIC;0402")
      (fields (field (name "APPROVED") "CL"))
      (libsource (lib "Giga-tronics") (part "CK41-00024"))
    )
    (comp (ref "C817")
      (value "10nF")
      (footprint "CAP-0402-N")
      (description "10nF;10%;X7R;16 WVDC;CHIP;0402")
      (fields (field (name "APPROVED") "CL"))
      (libsource (lib "Giga-tronics") (part "TCC3-03100"))
    )
    (comp (ref "C818")
      (value "2.4pF")
      (footprint "CAP-0402-RF")
      (description "2.4 PF;200V;.05PF;HIGH Q;SMT;CERAMIC;0402")
      (fields (field (name "APPROVED") "CL"))
      (libsource (lib "Giga-tronics") (part "CK41-00024"))
    )
    (comp (ref "C820")
      (value "10nF")
      (footprint "CAP-0402-N")
      (description "10nF;10%;X7R;16 WVDC;CHIP;0402")
      (fields (field (name "APPROVED") "CL"))
      (libsource (lib "Giga-tronics") (part "TCC3-03100"))
    )
    (comp (ref "C821")
      (value "12pF")
      (footprint "CAP-0402-N")
      (description "12 PF;5%;COG;>50V;CHIP;0402")
      (fields (field (name "NOLOAD") "N/L") (field (name "APPROVED") "CL"))
      (libsource (lib "Giga-tronics") (part "CK40-00120"))
    )
    (comp (ref "C894")
      (value "2.4pF")
      (footprint "CAP-0402-RF")
      (description "2.4 PF;200V;.05PF;HIGH Q;SMT;CERAMIC;0402")
      (fields (field (name "APPROVED") "CL"))
      (libsource (lib "Giga-tronics") (part "CK41-00024"))
    )
    (comp (ref "C895")
      (value "2.4pF")
      (footprint "CAP-0402-RF")
      (description "2.4 PF;200V;.05PF;HIGH Q;SMT;CERAMIC;0402")
      (fields (field (name "APPROVED") "CL"))
      (libsource (lib "Giga-tronics") (part "CK41-00024"))
    )
    (comp (ref "C896")
      (value "2.4pF")
      (footprint "CAP-0402-RF")
      (description "2.4 PF;200V;.05PF;HIGH Q;SMT;CERAMIC;0402")
      (fields (field (name "APPROVED") "CL"))
      (libsource (lib "Giga-tronics") (part "CK41-00024"))
    )
    (comp (ref "C897")
      (value "2.4pF")
      (footprint "CAP-0402-RF")
      (description "2.4 PF;200V;.05PF;HIGH Q;SMT;CERAMIC;0402")
      (fields (field (name "APPROVED") "CL"))
      (libsource (lib "Giga-tronics") (part "CK41-00024"))
    )
    (comp (ref "C898")
      (value "2.4pF")
      (footprint "CAP-0402-RF")
      (description "2.4 PF;200V;.05PF;HIGH Q;SMT;CERAMIC;0402")
      (fields (field (name "APPROVED") "CL"))
      (libsource (lib "Giga-tronics") (part "CK41-00024"))
    )
    (comp (ref "C899")
      (value "2.4pF")
      (footprint "CAP-0402-RF")
      (description "2.4 PF;200V;.05PF;HIGH Q;SMT;CERAMIC;0402")
      (fields (field (name "APPROVED") "CL"))
      (libsource (lib "Giga-tronics") (part "CK41-00024"))
    )
    (comp (ref "C900")
      (value "2.4pF")
      (footprint "CAP-0402-RF")
      (description "2.4 PF;200V;.05PF;HIGH Q;SMT;CERAMIC;0402")
      (fields (field (name "APPROVED") "CL"))
      (libsource (lib "Giga-tronics") (part "CK41-00024"))
    )
    (comp (ref "C901")
      (value "2.4pF")
      (footprint "CAP-0402-RF")
      (description "2.4 PF;200V;.05PF;HIGH Q;SMT;CERAMIC;0402")
      (fields (field (name "APPROVED") "CL"))
      (libsource (lib "Giga-tronics") (part "CK41-00024"))
    )
    (comp (ref "C902")
      (value "3.3pF")
      (footprint "CAP-0201-N")
      (description "3.3pF;5%;COG;50V;CHIP;0201")
      (fields (field (name "APPROVED") "CL"))
      (libsource (lib "Giga-tronics") (part "CK35-00033"))
    )
    (comp (ref "C903")
      (value "3.3pF")
      (footprint "CAP-0201-N")
      (description "3.3pF;5%;COG;50V;CHIP;0201")
      (fields (field (name "APPROVED") "CL"))
      (libsource (lib "Giga-tronics") (part "CK35-00033"))
    )
    (comp (ref "C904")
      (value "2.4pF")
      (footprint "CAP-0402-RF")
      (description "2.4 PF;200V;.05PF;HIGH Q;SMT;CERAMIC;0402")
      (fields (field (name "APPROVED") "CL"))
      (libsource (lib "Giga-tronics") (part "CK41-00024"))
    )
    (comp (ref "C905")
      (value "2.4pF")
      (footprint "CAP-0402-RF")
      (description "2.4 PF;200V;.05PF;HIGH Q;SMT;CERAMIC;0402")
      (fields (field (name "APPROVED") "CL"))
      (libsource (lib "Giga-tronics") (part "CK41-00024"))
    )
    (comp (ref "C906")
      (value "2.4pF")
      (footprint "CAP-0402-RF")
      (description "2.4 PF;200V;.05PF;HIGH Q;SMT;CERAMIC;0402")
      (fields (field (name "APPROVED") "CL"))
      (libsource (lib "Giga-tronics") (part "CK41-00024"))
    )
    (comp (ref "C907")
      (value "2.4pF")
      (footprint "CAP-0402-RF")
      (description "2.4 PF;200V;.05PF;HIGH Q;SMT;CERAMIC;0402")
      (fields (field (name "APPROVED") "CL"))
      (libsource (lib "Giga-tronics") (part "CK41-00024"))
    )
    (comp (ref "C908")
      (value "2.4pF")
      (footprint "CAP-0402-RF")
      (description "2.4 PF;200V;.05PF;HIGH Q;SMT;CERAMIC;0402")
      (fields (field (name "APPROVED") "CL"))
      (libsource (lib "Giga-tronics") (part "CK41-00024"))
    )
    (comp (ref "C909")
      (value "2.4pF")
      (footprint "CAP-0402-RF")
      (description "2.4 PF;200V;.05PF;HIGH Q;SMT;CERAMIC;0402")
      (fields (field (name "APPROVED") "CL"))
      (libsource (lib "Giga-tronics") (part "CK41-00024"))
    )
    (comp (ref "C910")
      (value "3.3pF")
      (footprint "CAP-0201-N")
      (description "3.3pF;5%;COG;50V;CHIP;0201")
      (fields (field (name "APPROVED") "CL"))
      (libsource (lib "Giga-tronics") (part "CK35-00033"))
    )
    (comp (ref "C911")
      (value "3.3pF")
      (footprint "CAP-0201-N")
      (description "3.3pF;5%;COG;50V;CHIP;0201")
      (fields (field (name "APPROVED") "CL"))
      (libsource (lib "Giga-tronics") (part "CK35-00033"))
    )
    (comp (ref "C912")
      (value "2.7pF")
      (footprint "CAP-0201-N")
      (description "2.7pF;5%;COG;50V;CHIP;0201")
      (fields (field (name "APPROVED") "CL"))
      (libsource (lib "Giga-tronics") (part "CK35-00027"))
    )
    (comp (ref "C913")
      (value "2.7pF")
      (footprint "CAP-0201-N")
      (description "2.7pF;5%;COG;50V;CHIP;0201")
      (fields (field (name "APPROVED") "CL"))
      (libsource (lib "Giga-tronics") (part "CK35-00027"))
    )
    (comp (ref "C914")
      (value "2.4pF")
      (footprint "CAP-0402-RF")
      (description "2.4 PF;200V;.05PF;HIGH Q;SMT;CERAMIC;0402")
      (fields (field (name "APPROVED") "CL"))
      (libsource (lib "Giga-tronics") (part "CK41-00024"))
    )
    (comp (ref "C915")
      (value "2.4pF")
      (footprint "CAP-0402-RF")
      (description "2.4 PF;200V;.05PF;HIGH Q;SMT;CERAMIC;0402")
      (fields (field (name "APPROVED") "CL"))
      (libsource (lib "Giga-tronics") (part "CK41-00024"))
    )
    (comp (ref "C916")
      (value "2.7pF")
      (footprint "CAP-0201-N")
      (description "2.7pF;5%;COG;50V;CHIP;0201")
      (fields (field (name "APPROVED") "CL"))
      (libsource (lib "Giga-tronics") (part "CK35-00027"))
    )
    (comp (ref "C917")
      (value "2.7pF")
      (footprint "CAP-0201-N")
      (description "2.7pF;5%;COG;50V;CHIP;0201")
      (fields (field (name "APPROVED") "CL"))
      (libsource (lib "Giga-tronics") (part "CK35-00027"))
    )
    (comp (ref "C918")
      (value "3.3pF")
      (footprint "CAP-0201-N")
      (description "3.3pF;5%;COG;50V;CHIP;0201")
      (fields (field (name "APPROVED") "CL"))
      (libsource (lib "Giga-tronics") (part "CK35-00033"))
    )
    (comp (ref "C919")
      (value "3.3pF")
      (footprint "CAP-0201-N")
      (description "3.3pF;5%;COG;50V;CHIP;0201")
      (fields (field (name "APPROVED") "CL"))
      (libsource (lib "Giga-tronics") (part "CK35-00033"))
    )
    (comp (ref "C920")
      (value "3.3pF")
      (footprint "CAP-0201-N")
      (description "3.3pF;5%;COG;50V;CHIP;0201")
      (fields (field (name "APPROVED") "CL"))
      (libsource (lib "Giga-tronics") (part "CK35-00033"))
    )
    (comp (ref "C921")
      (value "3.3pF")
      (footprint "CAP-0201-N")
      (description "3.3pF;5%;COG;50V;CHIP;0201")
      (fields (field (name "APPROVED") "CL"))
      (libsource (lib "Giga-tronics") (part "CK35-00033"))
    )
    (comp (ref "C922")
      (value "3.3pF")
      (footprint "CAP-0201-N")
      (description "3.3pF;5%;COG;50V;CHIP;0201")
      (fields (field (name "APPROVED") "CL"))
      (libsource (lib "Giga-tronics") (part "CK35-00033"))
    )
    (comp (ref "C923")
      (value "3.3pF")
      (footprint "CAP-0201-N")
      (description "3.3pF;5%;COG;50V;CHIP;0201")
      (fields (field (name "APPROVED") "CL"))
      (libsource (lib "Giga-tronics") (part "CK35-00033"))
    )
    (comp (ref "C924")
      (value "3.3pF")
      (footprint "CAP-0201-N")
      (description "3.3pF;5%;COG;50V;CHIP;0201")
      (fields (field (name "APPROVED") "CL"))
      (libsource (lib "Giga-tronics") (part "CK35-00033"))
    )
    (comp (ref "C925")
      (value "3.3pF")
      (footprint "CAP-0201-N")
      (description "3.3pF;5%;COG;50V;CHIP;0201")
      (fields (field (name "APPROVED") "CL"))
      (libsource (lib "Giga-tronics") (part "CK35-00033"))
    )
    (comp (ref "C926")
      (value "3.3pF")
      (footprint "CAP-0201-N")
      (description "3.3pF;5%;COG;50V;CHIP;0201")
      (fields (field (name "APPROVED") "CL"))
      (libsource (lib "Giga-tronics") (part "CK35-00033"))
    )
    (comp (ref "C927")
      (value "3.3pF")
      (footprint "CAP-0201-N")
      (description "3.3pF;5%;COG;50V;CHIP;0201")
      (fields (field (name "APPROVED") "CL"))
      (libsource (lib "Giga-tronics") (part "CK35-00033"))
    )
    (comp (ref "C928")
      (value "3.3pF")
      (footprint "CAP-0201-N")
      (description "3.3pF;5%;COG;50V;CHIP;0201")
      (fields (field (name "APPROVED") "CL"))
      (libsource (lib "Giga-tronics") (part "CK35-00033"))
    )
    (comp (ref "C929")
      (value "3.3pF")
      (footprint "CAP-0201-N")
      (description "3.3pF;5%;COG;50V;CHIP;0201")
      (fields (field (name "APPROVED") "CL"))
      (libsource (lib "Giga-tronics") (part "CK35-00033"))
    )
    (comp (ref "C930")
      (value "3.3pF")
      (footprint "CAP-0201-N")
      (description "3.3pF;5%;COG;50V;CHIP;0201")
      (fields (field (name "APPROVED") "CL"))
      (libsource (lib "Giga-tronics") (part "CK35-00033"))
    )
    (comp (ref "C931")
      (value "3.3pF")
      (footprint "CAP-0201-N")
      (description "3.3pF;5%;COG;50V;CHIP;0201")
      (fields (field (name "APPROVED") "CL"))
      (libsource (lib "Giga-tronics") (part "CK35-00033"))
    )
    (comp (ref "C932")
      (value "3.3pF")
      (footprint "CAP-0201-N")
      (description "3.3pF;5%;COG;50V;CHIP;0201")
      (fields (field (name "APPROVED") "CL"))
      (libsource (lib "Giga-tronics") (part "CK35-00033"))
    )
    (comp (ref "C933")
      (value "3.3pF")
      (footprint "CAP-0201-N")
      (description "3.3pF;5%;COG;50V;CHIP;0201")
      (fields (field (name "APPROVED") "CL"))
      (libsource (lib "Giga-tronics") (part "CK35-00033"))
    )
    (comp (ref "C934")
      (value "3.3pF")
      (footprint "CAP-0201-N")
      (description "3.3pF;5%;COG;50V;CHIP;0201")
      (fields (field (name "APPROVED") "CL"))
      (libsource (lib "Giga-tronics") (part "CK35-00033"))
    )
    (comp (ref "C935")
      (value "3.3pF")
      (footprint "CAP-0201-N")
      (description "3.3pF;5%;COG;50V;CHIP;0201")
      (fields (field (name "APPROVED") "CL"))
      (libsource (lib "Giga-tronics") (part "CK35-00033"))
    )
    (comp (ref "C936")
      (value "3.3pF")
      (footprint "CAP-0201-N")
      (description "3.3pF;5%;COG;50V;CHIP;0201")
      (fields (field (name "APPROVED") "CL"))
      (libsource (lib "Giga-tronics") (part "CK35-00033"))
    )
    (comp (ref "C937")
      (value "3.3pF")
      (footprint "CAP-0201-N")
      (description "3.3pF;5%;COG;50V;CHIP;0201")
      (fields (field (name "APPROVED") "CL"))
      (libsource (lib "Giga-tronics") (part "CK35-00033"))
    )
    (comp (ref "C938")
      (value "3.3pF")
      (footprint "CAP-0201-N")
      (description "3.3pF;5%;COG;50V;CHIP;0201")
      (fields (field (name "APPROVED") "CL"))
      (libsource (lib "Giga-tronics") (part "CK35-00033"))
    )
    (comp (ref "C939")
      (value "3.3pF")
      (footprint "CAP-0201-N")
      (description "3.3pF;5%;COG;50V;CHIP;0201")
      (fields (field (name "APPROVED") "CL"))
      (libsource (lib "Giga-tronics") (part "CK35-00033"))
    )
    (comp (ref "C940")
      (value "3.3pF")
      (footprint "CAP-0201-N")
      (description "3.3pF;5%;COG;50V;CHIP;0201")
      (fields (field (name "APPROVED") "CL"))
      (libsource (lib "Giga-tronics") (part "CK35-00033"))
    )
    (comp (ref "C941")
      (value "3.3pF")
      (footprint "CAP-0201-N")
      (description "3.3pF;5%;COG;50V;CHIP;0201")
      (fields (field (name "APPROVED") "CL"))
      (libsource (lib "Giga-tronics") (part "CK35-00033"))
    )
    (comp (ref "C942")
      (value "3.3pF")
      (footprint "CAP-0201-N")
      (description "3.3pF;5%;COG;50V;CHIP;0201")
      (fields (field (name "APPROVED") "CL"))
      (libsource (lib "Giga-tronics") (part "CK35-00033"))
    )
    (comp (ref "C943")
      (value "3.3pF")
      (footprint "CAP-0201-N")
      (description "3.3pF;5%;COG;50V;CHIP;0201")
      (fields (field (name "APPROVED") "CL"))
      (libsource (lib "Giga-tronics") (part "CK35-00033"))
    )
    (comp (ref "C944")
      (value "3.3pF")
      (footprint "CAP-0201-N")
      (description "3.3pF;5%;COG;50V;CHIP;0201")
      (fields (field (name "APPROVED") "CL"))
      (libsource (lib "Giga-tronics") (part "CK35-00033"))
    )
    (comp (ref "C945")
      (value "3.3pF")
      (footprint "CAP-0201-N")
      (description "3.3pF;5%;COG;50V;CHIP;0201")
      (fields (field (name "APPROVED") "CL"))
      (libsource (lib "Giga-tronics") (part "CK35-00033"))
    )
    (comp (ref "FL1")
      (value "Filter EMI 2200PF,1206")
      (footprint "FIL-NFE31P-1206-4P")
      (fields (field (name "G_PN") "LFS0-00222") (field (name "APPROVED") "CL"))
      (libsource (lib "Giga-tronics") (part "LFS0-00222"))
    )
    (comp (ref "FL2")
      (value "Filter EMI 2200PF,1206")
      (footprint "FIL-NFE31P-1206-4P")
      (fields (field (name "G_PN") "LFS0-00222") (field (name "APPROVED") "CL"))
      (libsource (lib "Giga-tronics") (part "LFS0-00222"))
    )
    (comp (ref "FL3")
      (value "F/T FILTER;CHIP;2.5 DCR150MA;16V;T LC;25PF;200MHz;0603")
      (footprint "FIL-NFL18ST")
      (fields (field (name "G_PN") "LFS0-00250") (field (name "APPROVED") "NM"))
      (libsource (lib "Giga-tronics") (part "LFS0-00250"))
    )
    (comp (ref "FL4")
      (value "FILTER;HI PASS;3100MHz;5SEC;FV1206-1;RoHS")
      (footprint "FV1206-1")
      (fields (field (name "M_PN") "HFCN-3100D+") (field (name "APPROVED") "CL"))
      (libsource (lib "Giga-tronics") (part "MFH0-03100"))
    )
    (comp (ref "FL7")
      (value "FILTER;CER;BANDPASS;4000MHZ;70MHZ BW;6-SEC;SMT")
      (footprint "FIL-1060X380X240_2_10P")
      (fields (field (name "G_PN") "MFB1-04000") (field (name "APPROVED") "CL"))
      (libsource (lib "Giga-tronics") (part "MFB1-04000"))
    )
    (comp (ref "FL8")
      (value "FILTER;CER;BANDPASS;4000MHZ;70MHZ BW;6-SEC;SMT")
      (footprint "FIL-1060X380X240_2_10P")
      (fields (field (name "G_PN") "MFB1-04000") (field (name "APPROVED") "CL"))
      (libsource (lib "Giga-tronics") (part "MFB1-04000"))
    )
    (comp (ref "FL16")
      (value "4SD3600-U70-6CC")
      (footprint "FIL-1060X380X240_2_10P")
      (description "FILTER;CER;BANDPASS;3600MHZ;70MHZ BW;6-SEC;SMT")
      (fields (field (name "G_PN") "MFB1-03600") (field (name "APPROVED") "CL"))
      (libsource (lib "Giga-tronics") (part "MFB1-03600"))
    )
    (comp (ref "FL17")
      (value "4SD3600-U70-6CC")
      (footprint "FIL-1060X380X240_2_10P")
      (description "FILTER;CER;BANDPASS;3600MHZ;70MHZ BW;6-SEC;SMT")
      (fields (field (name "G_PN") "MFB1-03600") (field (name "APPROVED") "CL"))
      (libsource (lib "Giga-tronics") (part "MFB1-03600"))
    )
    (comp (ref "FL24")
      (value "FILTER;CER;BANDPASS;3200MHZ;70MHZ BW;6-SEC;SMT")
      (footprint "FIL-1060X380X240_2_10P")
      (fields (field (name "G_PN") "MFB1-03200") (field (name "APPROVED") "CL"))
      (libsource (lib "Giga-tronics") (part "MFB1-03200"))
    )
    (comp (ref "FL25")
      (value "FILTER;CER;BANDPASS;3200MHZ;70MHZ BW;6-SEC;SMT")
      (footprint "FIL-1060X380X240_2_10P")
      (fields (field (name "G_PN") "MFB1-03200") (field (name "APPROVED") "CL"))
      (libsource (lib "Giga-tronics") (part "MFB1-03200"))
    )
    (comp (ref "FL30")
      (value "FILTER;CER;BANDPASS;3400MHZ;70MHZ BW;6-SEC;SMT")
      (footprint "FIL-1060X380X240_2_10P")
      (fields (field (name "G_PN") "MFB1-03400") (field (name "APPROVED") "CL"))
      (libsource (lib "Giga-tronics") (part "MFB1-03400"))
    )
    (comp (ref "FL31")
      (value "FILTER;CER;BANDPASS;3400MHZ;70MHZ BW;6-SEC;SMT")
      (footprint "FIL-1060X380X240_2_10P")
      (fields (field (name "G_PN") "MFB1-03400") (field (name "APPROVED") "CL"))
      (libsource (lib "Giga-tronics") (part "MFB1-03400"))
    )
    (comp (ref "FL35")
      (value "FILTER;CER;BANDPASS;3800MHZ;70MHZ BW;6-SEC;SMT")
      (footprint "FIL-1060X380X240_2_10P")
      (fields (field (name "G_PN") "MFB1-03800") (field (name "APPROVED") "CL"))
      (libsource (lib "Giga-tronics") (part "MFB1-03800"))
    )
    (comp (ref "FL36")
      (value "FILTER;CER;BANDPASS;3800MHZ;70MHZ BW;6-SEC;SMT")
      (footprint "FIL-1060X380X240_2_10P")
      (fields (field (name "G_PN") "MFB1-03800") (field (name "APPROVED") "CL"))
      (libsource (lib "Giga-tronics") (part "MFB1-03800"))
    )
    (comp (ref "FL40")
      (value "FILTER;CER;BANDPASS;4200MHZ;70MHZ BW;6-SEC;SMT")
      (footprint "FIL-1060X380X240_2_10P")
      (fields (field (name "G_PN") "MFB1-04200") (field (name "APPROVED") "CL"))
      (libsource (lib "Giga-tronics") (part "MFB1-04200"))
    )
    (comp (ref "FL41")
      (value "FILTER;CER;BANDPASS;4200MHZ;70MHZ BW;6-SEC;SMT")
      (footprint "FIL-1060X380X240_2_10P")
      (fields (field (name "G_PN") "MFB1-04200") (field (name "APPROVED") "CL"))
      (libsource (lib "Giga-tronics") (part "MFB1-04200"))
    )
    (comp (ref "FL93")
      (value "FILTER;LOW PASS;3900MHz;7SEC;RoHS;FV1206")
      (footprint "FV1206")
      (fields (field (name "M_PN") "LFCN-3800D+") (field (name "APPROVED") "CL"))
      (libsource (lib "Giga-tronics") (part "MFL1-03900"))
    )
    (comp (ref "FL143")
      (value "Filter EMI 2200PF,1206")
      (footprint "FIL-NFE31P-1206-4P")
      (fields (field (name "G_PN") "LFS0-00222") (field (name "APPROVED") "CL"))
      (libsource (lib "Giga-tronics") (part "LFS0-00222"))
    )
    (comp (ref "FL144")
      (value "Filter EMI 2200PF,1206")
      (footprint "FIL-NFE31P-1206-4P")
      (fields (field (name "G_PN") "LFS0-00222") (field (name "APPROVED") "CL"))
      (libsource (lib "Giga-tronics") (part "LFS0-00222"))
    )
    (comp (ref "FL145")
      (value "F/T FILTER;CHIP;2.5 DCR150MA;16V;T LC;25PF;200MHz;0603")
      (footprint "FIL-NFL18ST")
      (fields (field (name "G_PN") "LFS0-00250") (field (name "APPROVED") "NM"))
      (libsource (lib "Giga-tronics") (part "LFS0-00250"))
    )
    (comp (ref "FL146")
      (value "FILTER;LOW PASS;4400MHz;7SEC;FV1206")
      (footprint "FV1206")
      (fields (field (name "G_PN") "MFL0-04400") (field (name "APPROVED") "NM"))
      (libsource (lib "Giga-tronics") (part "MFL0-04400"))
    )
    (comp (ref "FL147")
      (value "Filter EMI 2200PF,1206")
      (footprint "FIL-NFE31P-1206-4P")
      (fields (field (name "G_PN") "LFS0-00222") (field (name "APPROVED") "CL"))
      (libsource (lib "Giga-tronics") (part "LFS0-00222"))
    )
    (comp (ref "FL148")
      (value "Filter EMI 2200PF,1206")
      (footprint "FIL-NFE31P-1206-4P")
      (fields (field (name "G_PN") "LFS0-00222") (field (name "APPROVED") "CL"))
      (libsource (lib "Giga-tronics") (part "LFS0-00222"))
    )
    (comp (ref "FL149")
      (value "F/T FILTER;CHIP;2.5 DCR150MA;16V;T LC;25PF;200MHz;0603")
      (footprint "FIL-NFL18ST")
      (fields (field (name "G_PN") "LFS0-00250") (field (name "APPROVED") "NM"))
      (libsource (lib "Giga-tronics") (part "LFS0-00250"))
    )
    (comp (ref "FL150")
      (value "FILTER;LOW PASS;4400MHz;7SEC;FV1206")
      (footprint "FV1206")
      (fields (field (name "G_PN") "MFL0-04400") (field (name "APPROVED") "NM"))
      (libsource (lib "Giga-tronics") (part "MFL0-04400"))
    )
    (comp (ref "FT6")
      (value "STALO_1")
      (footprint "FromToNode_ML2")
      (fields (field (name "NOLOAD") "N/L") (field (name "APPROVED") "*"))
      (libsource (lib "Giga-tronics") (part "FromToNode"))
    )
    (comp (ref "FT17")
      (value "STALO_1")
      (footprint "FromToNode_ML2")
      (fields (field (name "NOLOAD") "N/L") (field (name "APPROVED") "*"))
      (libsource (lib "Giga-tronics") (part "FromToNode"))
    )
    (comp (ref "FT32")
      (value "STALO_1")
      (footprint "FromToNode_ML2")
      (fields (field (name "NOLOAD") "N/L") (field (name "APPROVED") "*"))
      (libsource (lib "Giga-tronics") (part "FromToNode"))
    )
    (comp (ref "J23")
      (value "SMPM;SB;MALE;STRAIGHT;SMT;.152X.152X.150;PCB;R/A CONTACT")
      (footprint "JRSM-40101")
      (fields (field (name "NOLOAD") "N/L") (field (name "APPROVED") "CL"))
      (libsource (lib "Giga-tronics") (part "JRSM-40101"))
    )
    (comp (ref "J24")
      (value "SMPM;SB;MALE;STRAIGHT;SMT;.152X.152X.150;PCB;R/A CONTACT")
      (footprint "JRSM-40101")
      (fields (field (name "NOLOAD") "N/L") (field (name "APPROVED") "CL"))
      (libsource (lib "Giga-tronics") (part "JRSM-40101"))
    )
    (comp (ref "L2")
      (value "4.3nH")
      (footprint "IND-0603HP")
      (description "INDUCTOR;4.3;2%;7.5GHZ SRF;91Q @1.7GHZ;.08 DCR;1.3A;0603")
      (fields (field (name "APPROVED") "CL"))
      (libsource (lib "Giga-tronics") (part "LSA5-02430"))
    )
    (comp (ref "L3")
      (value "4.3nH")
      (footprint "IND-0603HP")
      (description "INDUCTOR;4.3;2%;7.5GHZ SRF;91Q @1.7GHZ;.08 DCR;1.3A;0603")
      (fields (field (name "APPROVED") "CL"))
      (libsource (lib "Giga-tronics") (part "LSA5-02430"))
    )
    (comp (ref "L4")
      (value "8.7nH")
      (footprint "IND-0603HP")
      (description "INDUCTOR;8.7NH;2%;5.5G SRF;149Q @1.7G;.054 DCR;1.4A;0603")
      (fields (field (name "APPROVED") "CL"))
      (libsource (lib "Giga-tronics") (part "LSA5-02870"))
    )
    (comp (ref "L6")
      (value "3.9nH")
      (footprint "IND-0603HP")
      (description "INDUCTOR;3.9;2%;7.5GHZ SRF;108Q @1.7GHZ;.039 DCR;1.6A;0603")
      (fields (field (name "APPROVED") "CL"))
      (libsource (lib "") (part "LSA5-02390_1"))
    )
    (comp (ref "L7")
      (value "3.9nH")
      (footprint "IND-0603HP")
      (description "INDUCTOR;3.9;2%;7.5GHZ SRF;108Q @1.7GHZ;.039 DCR;1.6A;0603")
      (fields (field (name "APPROVED") "CL"))
      (libsource (lib "") (part "LSA5-02390_1"))
    )
    (comp (ref "L46")
      (value "3.3nH")
      (footprint "IND-0603HP")
      (description "INDUCTOR;3.3NH;2%;9.6G SRF;104Q @1.7G;.024 DCR;1.9A;0603")
      (fields (field (name "APPROVED") "CL"))
      (libsource (lib "Giga-tronics") (part "LSA5-02330"))
    )
    (comp (ref "L52")
      (value "3.3nH")
      (footprint "IND-0603HP")
      (description "INDUCTOR;3.3NH;2%;9.6G SRF;104Q @1.7G;.024 DCR;1.9A;0603")
      (fields (field (name "APPROVED") "CL"))
      (libsource (lib "Giga-tronics") (part "LSA5-02330"))
    )
    (comp (ref "L53")
      (value "3.3nH")
      (footprint "IND-0603HP")
      (description "INDUCTOR;3.3NH;2%;9.6G SRF;104Q @1.7G;.024 DCR;1.9A;0603")
      (fields (field (name "APPROVED") "CL"))
      (libsource (lib "Giga-tronics") (part "LSA5-02330"))
    )
    (comp (ref "L58")
      (value "3.3nH")
      (footprint "IND-0603HP")
      (description "INDUCTOR;3.3NH;2%;9.6G SRF;104Q @1.7G;.024 DCR;1.9A;0603")
      (fields (field (name "APPROVED") "CL"))
      (libsource (lib "Giga-tronics") (part "LSA5-02330"))
    )
    (comp (ref "L60")
      (value "3.3nH")
      (footprint "IND-0603HP")
      (description "INDUCTOR;3.3NH;2%;9.6G SRF;104Q @1.7G;.024 DCR;1.9A;0603")
      (fields (field (name "APPROVED") "CL"))
      (libsource (lib "Giga-tronics") (part "LSA5-02330"))
    )
    (comp (ref "L61")
      (value "3.3nH")
      (footprint "IND-0603HP")
      (description "INDUCTOR;3.3NH;2%;9.6G SRF;104Q @1.7G;.024 DCR;1.9A;0603")
      (fields (field (name "APPROVED") "CL"))
      (libsource (lib "Giga-tronics") (part "LSA5-02330"))
    )
    (comp (ref "L62")
      (value "3.3nH")
      (footprint "IND-0603HP")
      (description "INDUCTOR;3.3NH;2%;9.6G SRF;104Q @1.7G;.024 DCR;1.9A;0603")
      (fields (field (name "APPROVED") "CL"))
      (libsource (lib "Giga-tronics") (part "LSA5-02330"))
    )
    (comp (ref "L63")
      (value "3.3nH")
      (footprint "IND-0603HP")
      (description "INDUCTOR;3.3NH;2%;9.6G SRF;104Q @1.7G;.024 DCR;1.9A;0603")
      (fields (field (name "APPROVED") "CL"))
      (libsource (lib "Giga-tronics") (part "LSA5-02330"))
    )
    (comp (ref "L64")
      (value "4.7nH")
      (footprint "IND-0603HP")
      (description "INDUCTOR;4.7;2%;7.9GHZ SRF;75Q @1.7GHZ;.1 DCR;1.1A;0603")
      (fields (field (name "APPROVED") "CL"))
      (libsource (lib "Giga-tronics") (part "LSA5-02470"))
    )
    (comp (ref "L70")
      (value "4.7nH")
      (footprint "IND-0603HP")
      (description "INDUCTOR;4.7;2%;7.9GHZ SRF;75Q @1.7GHZ;.1 DCR;1.1A;0603")
      (fields (field (name "APPROVED") "CL"))
      (libsource (lib "Giga-tronics") (part "LSA5-02470"))
    )
    (comp (ref "L72")
      (value "4.7nH")
      (footprint "IND-0603HP")
      (description "INDUCTOR;4.7;2%;7.9GHZ SRF;75Q @1.7GHZ;.1 DCR;1.1A;0603")
      (fields (field (name "APPROVED") "CL"))
      (libsource (lib "Giga-tronics") (part "LSA5-02470"))
    )
    (comp (ref "L74")
      (value "4.7nH")
      (footprint "IND-0603HP")
      (description "INDUCTOR;4.7;2%;7.9GHZ SRF;75Q @1.7GHZ;.1 DCR;1.1A;0603")
      (fields (field (name "APPROVED") "CL"))
      (libsource (lib "Giga-tronics") (part "LSA5-02470"))
    )
    (comp (ref "L75")
      (value "3.9nH")
      (footprint "IND-0603HP")
      (description "INDUCTOR;3.9;2%;7.5GHZ SRF;108Q @1.7GHZ;.039 DCR;1.6A;0603")
      (fields (field (name "APPROVED") "CL"))
      (libsource (lib "Giga-tronics") (part "LSA5-02390"))
    )
    (comp (ref "L80")
      (value "3.9nH")
      (footprint "IND-0603HP")
      (description "INDUCTOR;3.9;2%;7.5GHZ SRF;108Q @1.7GHZ;.039 DCR;1.6A;0603")
      (fields (field (name "APPROVED") "CL"))
      (libsource (lib "Giga-tronics") (part "LSA5-02390"))
    )
    (comp (ref "L81")
      (value "3.9nH")
      (footprint "IND-0603HP")
      (description "INDUCTOR;3.9;2%;7.5GHZ SRF;108Q @1.7GHZ;.039 DCR;1.6A;0603")
      (fields (field (name "APPROVED") "CL"))
      (libsource (lib "Giga-tronics") (part "LSA5-02390"))
    )
    (comp (ref "L82")
      (value "3.9nH")
      (footprint "IND-0603HP")
      (description "INDUCTOR;3.9;2%;7.5GHZ SRF;108Q @1.7GHZ;.039 DCR;1.6A;0603")
      (fields (field (name "APPROVED") "CL"))
      (libsource (lib "Giga-tronics") (part "LSA5-02390"))
    )
    (comp (ref "L83")
      (value "3.3nH")
      (footprint "IND-0603HP")
      (description "INDUCTOR;3.3NH;2%;9.6G SRF;104Q @1.7G;.024 DCR;1.9A;0603")
      (fields (field (name "APPROVED") "CL"))
      (libsource (lib "Giga-tronics") (part "LSA5-02330"))
    )
    (comp (ref "L86")
      (value "3.3nH")
      (footprint "IND-0603HP")
      (description "INDUCTOR;3.3NH;2%;9.6G SRF;104Q @1.7G;.024 DCR;1.9A;0603")
      (fields (field (name "APPROVED") "CL"))
      (libsource (lib "Giga-tronics") (part "LSA5-02330"))
    )
    (comp (ref "L87")
      (value "3.3nH")
      (footprint "IND-0603HP")
      (description "INDUCTOR;3.3NH;2%;9.6G SRF;104Q @1.7G;.024 DCR;1.9A;0603")
      (fields (field (name "APPROVED") "CL"))
      (libsource (lib "Giga-tronics") (part "LSA5-02330"))
    )
    (comp (ref "L91")
      (value "15nH")
      (footprint "IND-0402HP")
      (description "INDUCTOR;15NH;2%;3.9GHZ SRF;85Q @1.7GHZ;.078 DCR;1.1A;0402")
      (fields (field (name "APPROVED") "CL"))
      (libsource (lib "Giga-tronics") (part "LSA6-03150"))
    )
    (comp (ref "L92")
      (value "3.3nH")
      (footprint "IND-0603HP")
      (description "INDUCTOR;3.3NH;2%;9.6G SRF;104Q @1.7G;.024 DCR;1.9A;0603")
      (fields (field (name "APPROVED") "CL"))
      (libsource (lib "Giga-tronics") (part "LSA5-02330"))
    )
    (comp (ref "L93")
      (value "1.8nH")
      (footprint "IND-0603HP")
      (description "INDUCTOR;1.8NH;5%;16G SRF;65Q @1.7G;.18 DCR;.033A;0603")
      (fields (field (name "APPROVED") "CL"))
      (libsource (lib "Giga-tronics") (part "LSA5-02180"))
    )
    (comp (ref "L94")
      (value "1.8nH")
      (footprint "IND-0603HP")
      (description "INDUCTOR;1.8NH;5%;16G SRF;65Q @1.7G;.18 DCR;.033A;0603")
      (fields (field (name "APPROVED") "CL"))
      (libsource (lib "Giga-tronics") (part "LSA5-02180"))
    )
    (comp (ref "L95")
      (value "1.8nH")
      (footprint "IND-0603HP")
      (description "INDUCTOR;1.8NH;5%;16G SRF;65Q @1.7G;.18 DCR;.033A;0603")
      (fields (field (name "APPROVED") "CL"))
      (libsource (lib "Giga-tronics") (part "LSA5-02180"))
    )
    (comp (ref "L96")
      (value "15nH")
      (footprint "IND-0402HP")
      (description "INDUCTOR;15NH;2%;3.9GHZ SRF;85Q @1.7GHZ;.078 DCR;1.1A;0402")
      (fields (field (name "APPROVED") "CL"))
      (libsource (lib "") (part "LSA6-03150_1"))
    )
    (comp (ref "L97")
      (value "1.8nH")
      (footprint "IND-0603HP")
      (description "INDUCTOR;1.8NH;5%;16G SRF;65Q @1.7G;.18 DCR;.033A;0603")
      (fields (field (name "APPROVED") "CL"))
      (libsource (lib "Giga-tronics") (part "LSA5-02180"))
    )
    (comp (ref "L98")
      (value "15nH")
      (footprint "IND-0402HP")
      (description "INDUCTOR;15NH;2%;3.9GHZ SRF;85Q @1.7GHZ;.078 DCR;1.1A;0402")
      (fields (field (name "APPROVED") "CL"))
      (libsource (lib "Giga-tronics") (part "LSA6-03150"))
    )
    (comp (ref "L99")
      (value "15nH")
      (footprint "IND-0402HP")
      (description "INDUCTOR;15NH;2%;3.9GHZ SRF;85Q @1.7GHZ;.078 DCR;1.1A;0402")
      (fields (field (name "APPROVED") "CL"))
      (libsource (lib "Giga-tronics") (part "LSA6-03150"))
    )
    (comp (ref "L100")
      (value "15nH")
      (footprint "IND-0402HP")
      (description "INDUCTOR;15NH;2%;3.9GHZ SRF;85Q @1.7GHZ;.078 DCR;1.1A;0402")
      (fields (field (name "APPROVED") "CL"))
      (libsource (lib "Giga-tronics") (part "LSA6-03150"))
    )
    (comp (ref "L101")
      (value "15nH")
      (footprint "IND-0402HP")
      (description "INDUCTOR;15NH;2%;3.9GHZ SRF;85Q @1.7GHZ;.078 DCR;1.1A;0402")
      (fields (field (name "APPROVED") "CL"))
      (libsource (lib "Giga-tronics") (part "LSA6-03150"))
    )
    (comp (ref "L102")
      (value "15nH")
      (footprint "IND-0402HP")
      (description "INDUCTOR;15NH;2%;3.9GHZ SRF;85Q @1.7GHZ;.078 DCR;1.1A;0402")
      (fields (field (name "APPROVED") "CL"))
      (libsource (lib "") (part "LSA6-03150_1"))
    )
    (comp (ref "L103")
      (value "15nH")
      (footprint "IND-0402HP")
      (description "INDUCTOR;15NH;2%;3.9GHZ SRF;85Q @1.7GHZ;.078 DCR;1.1A;0402")
      (fields (field (name "APPROVED") "CL"))
      (libsource (lib "Giga-tronics") (part "LSA6-03150"))
    )
    (comp (ref "L104")
      (value "15nH")
      (footprint "IND-0402HP")
      (description "INDUCTOR;15NH;2%;3.9GHZ SRF;85Q @1.7GHZ;.078 DCR;1.1A;0402")
      (fields (field (name "APPROVED") "CL"))
      (libsource (lib "") (part "LSA6-03150_1"))
    )
    (comp (ref "L105")
      (value "15nH")
      (footprint "IND-0402HP")
      (description "INDUCTOR;15NH;2%;3.9GHZ SRF;85Q @1.7GHZ;.078 DCR;1.1A;0402")
      (fields (field (name "APPROVED") "CL"))
      (libsource (lib "Giga-tronics") (part "LSA6-03150"))
    )
    (comp (ref "L106")
      (value "15nH")
      (footprint "IND-0402HP")
      (description "INDUCTOR;15NH;2%;3.9GHZ SRF;85Q @1.7GHZ;.078 DCR;1.1A;0402")
      (fields (field (name "APPROVED") "CL"))
      (libsource (lib "") (part "LSA6-03150_1"))
    )
    (comp (ref "L107")
      (value "15nH")
      (footprint "IND-0402HP")
      (description "INDUCTOR;15NH;2%;3.9GHZ SRF;85Q @1.7GHZ;.078 DCR;1.1A;0402")
      (fields (field (name "APPROVED") "CL"))
      (libsource (lib "Giga-tronics") (part "LSA6-03150"))
    )
    (comp (ref "L108")
      (value "15nH")
      (footprint "IND-0402HP")
      (description "INDUCTOR;15NH;2%;3.9GHZ SRF;85Q @1.7GHZ;.078 DCR;1.1A;0402")
      (fields (field (name "APPROVED") "CL"))
      (libsource (lib "") (part "LSA6-03150_1"))
    )
    (comp (ref "L109")
      (value "15nH")
      (footprint "IND-0402HP")
      (description "INDUCTOR;15NH;2%;3.9GHZ SRF;85Q @1.7GHZ;.078 DCR;1.1A;0402")
      (fields (field (name "APPROVED") "CL"))
      (libsource (lib "Giga-tronics") (part "LSA6-03150"))
    )
    (comp (ref "L110")
      (value "15nH")
      (footprint "IND-0402HP")
      (description "INDUCTOR;15NH;2%;3.9GHZ SRF;85Q @1.7GHZ;.078 DCR;1.1A;0402")
      (fields (field (name "APPROVED") "CL"))
      (libsource (lib "") (part "LSA6-03150_1"))
    )
    (comp (ref "L111")
      (value "15nH")
      (footprint "IND-0402HP")
      (description "INDUCTOR;15NH;2%;3.9GHZ SRF;85Q @1.7GHZ;.078 DCR;1.1A;0402")
      (fields (field (name "APPROVED") "CL"))
      (libsource (lib "Giga-tronics") (part "LSA6-03150"))
    )
    (comp (ref "L112")
      (value "15nH")
      (footprint "IND-0402HP")
      (description "INDUCTOR;15NH;2%;3.9GHZ SRF;85Q @1.7GHZ;.078 DCR;1.1A;0402")
      (fields (field (name "APPROVED") "CL"))
      (libsource (lib "") (part "LSA6-03150_1"))
    )
    (comp (ref "L113")
      (value "15nH")
      (footprint "IND-0402HP")
      (description "INDUCTOR;15NH;2%;3.9GHZ SRF;85Q @1.7GHZ;.078 DCR;1.1A;0402")
      (fields (field (name "APPROVED") "CL"))
      (libsource (lib "Giga-tronics") (part "LSA6-03150"))
    )
    (comp (ref "L114")
      (value "15nH")
      (footprint "IND-0402HP")
      (description "INDUCTOR;15NH;2%;3.9GHZ SRF;85Q @1.7GHZ;.078 DCR;1.1A;0402")
      (fields (field (name "APPROVED") "CL"))
      (libsource (lib "") (part "LSA6-03150_1"))
    )
    (comp (ref "L115")
      (value "15nH")
      (footprint "IND-0402HP")
      (description "INDUCTOR;15NH;2%;3.9GHZ SRF;85Q @1.7GHZ;.078 DCR;1.1A;0402")
      (fields (field (name "APPROVED") "CL"))
      (libsource (lib "Giga-tronics") (part "LSA6-03150"))
    )
    (comp (ref "L116")
      (value "15nH")
      (footprint "IND-0402HP")
      (description "INDUCTOR;15NH;2%;3.9GHZ SRF;85Q @1.7GHZ;.078 DCR;1.1A;0402")
      (fields (field (name "APPROVED") "CL"))
      (libsource (lib "") (part "LSA6-03150_1"))
    )
    (comp (ref "L117")
      (value "15nH")
      (footprint "IND-0402HP")
      (description "INDUCTOR;15NH;2%;3.9GHZ SRF;85Q @1.7GHZ;.078 DCR;1.1A;0402")
      (fields (field (name "APPROVED") "CL"))
      (libsource (lib "Giga-tronics") (part "LSA6-03150"))
    )
    (comp (ref "L118")
      (value "15nH")
      (footprint "IND-0402HP")
      (description "INDUCTOR;15NH;2%;3.9GHZ SRF;85Q @1.7GHZ;.078 DCR;1.1A;0402")
      (fields (field (name "APPROVED") "CL"))
      (libsource (lib "Giga-tronics") (part "LSA6-03150"))
    )
    (comp (ref "L138")
      (value "15nH")
      (footprint "IND-0402HP")
      (description "INDUCTOR;15NH;2%;3.9GHZ SRF;85Q @1.7GHZ;.078 DCR;1.1A;0402")
      (fields (field (name "APPROVED") "CL"))
      (libsource (lib "") (part "LSA6-03150_1"))
    )
    (comp (ref "L167")
      (value "15nH")
      (footprint "IND-0402HP")
      (description "INDUCTOR;15NH;2%;3.9GHZ SRF;85Q @1.7GHZ;.078 DCR;1.1A;0402")
      (fields (field (name "APPROVED") "CL"))
      (libsource (lib "") (part "LSA6-03150_1"))
    )
    (comp (ref "L204")
      (value "15nH")
      (footprint "IND-0402HP")
      (description "INDUCTOR;15NH;2%;3.9GHZ SRF;85Q @1.7GHZ;.078 DCR;1.1A;0402")
      (fields (field (name "APPROVED") "CL"))
      (libsource (lib "Giga-tronics") (part "LSA6-03150"))
    )
    (comp (ref "L205")
      (value "15nH")
      (footprint "IND-0402HP")
      (description "INDUCTOR;15NH;2%;3.9GHZ SRF;85Q @1.7GHZ;.078 DCR;1.1A;0402")
      (fields (field (name "APPROVED") "CL"))
      (libsource (lib "Giga-tronics") (part "LSA6-03150"))
    )
    (comp (ref "L207")
      (value "15nH")
      (footprint "IND-0402HP")
      (description "INDUCTOR;15NH;2%;3.9GHZ SRF;85Q @1.7GHZ;.078 DCR;1.1A;0402")
      (fields (field (name "APPROVED") "CL"))
      (libsource (lib "") (part "LSA6-03150_1"))
    )
    (comp (ref "L208")
      (value "15nH")
      (footprint "IND-0402HP")
      (description "INDUCTOR;15NH;2%;3.9GHZ SRF;85Q @1.7GHZ;.078 DCR;1.1A;0402")
      (fields (field (name "APPROVED") "CL"))
      (libsource (lib "Giga-tronics") (part "LSA6-03150"))
    )
    (comp (ref "L209")
      (value "15nH")
      (footprint "IND-0402HP")
      (description "INDUCTOR;15NH;2%;3.9GHZ SRF;85Q @1.7GHZ;.078 DCR;1.1A;0402")
      (fields (field (name "APPROVED") "CL"))
      (libsource (lib "") (part "LSA6-03150_1"))
    )
    (comp (ref "L210")
      (value "15nH")
      (footprint "IND-0402HP")
      (description "INDUCTOR;15NH;2%;3.9GHZ SRF;85Q @1.7GHZ;.078 DCR;1.1A;0402")
      (fields (field (name "APPROVED") "CL"))
      (libsource (lib "Giga-tronics") (part "LSA6-03150"))
    )
    (comp (ref "L211")
      (value "15nH")
      (footprint "IND-0402HP")
      (description "INDUCTOR;15NH;2%;3.9GHZ SRF;85Q @1.7GHZ;.078 DCR;1.1A;0402")
      (fields (field (name "APPROVED") "CL"))
      (libsource (lib "") (part "LSA6-03150_1"))
    )
    (comp (ref "L212")
      (value "15nH")
      (footprint "IND-0402HP")
      (description "INDUCTOR;15NH;2%;3.9GHZ SRF;85Q @1.7GHZ;.078 DCR;1.1A;0402")
      (fields (field (name "APPROVED") "CL"))
      (libsource (lib "") (part "LSA6-03150_1"))
    )
    (comp (ref "L213")
      (value "15nH")
      (footprint "IND-0402HP")
      (description "INDUCTOR;15NH;2%;3.9GHZ SRF;85Q @1.7GHZ;.078 DCR;1.1A;0402")
      (fields (field (name "APPROVED") "CL"))
      (libsource (lib "") (part "LSA6-03150_1"))
    )
    (comp (ref "L214")
      (value "15nH")
      (footprint "IND-0402HP")
      (description "INDUCTOR;15NH;2%;3.9GHZ SRF;85Q @1.7GHZ;.078 DCR;1.1A;0402")
      (fields (field (name "APPROVED") "CL"))
      (libsource (lib "") (part "LSA6-03150_1"))
    )
    (comp (ref "L215")
      (value "15nH")
      (footprint "IND-0402HP")
      (description "INDUCTOR;15NH;2%;3.9GHZ SRF;85Q @1.7GHZ;.078 DCR;1.1A;0402")
      (fields (field (name "APPROVED") "CL"))
      (libsource (lib "") (part "LSA6-03150_1"))
    )
    (comp (ref "L216")
      (value "15nH")
      (footprint "IND-0402HP")
      (description "INDUCTOR;15NH;2%;3.9GHZ SRF;85Q @1.7GHZ;.078 DCR;1.1A;0402")
      (fields (field (name "APPROVED") "CL"))
      (libsource (lib "") (part "LSA6-03150_1"))
    )
    (comp (ref "L217")
      (value "15nH")
      (footprint "IND-0402HP")
      (description "INDUCTOR;15NH;2%;3.9GHZ SRF;85Q @1.7GHZ;.078 DCR;1.1A;0402")
      (fields (field (name "APPROVED") "CL"))
      (libsource (lib "") (part "LSA6-03150_1"))
    )
    (comp (ref "L218")
      (value "15nH")
      (footprint "IND-0402HP")
      (description "INDUCTOR;15NH;2%;3.9GHZ SRF;85Q @1.7GHZ;.078 DCR;1.1A;0402")
      (fields (field (name "APPROVED") "CL"))
      (libsource (lib "") (part "LSA6-03150_1"))
    )
    (comp (ref "L219")
      (value "15nH")
      (footprint "IND-0402HP")
      (description "INDUCTOR;15NH;2%;3.9GHZ SRF;85Q @1.7GHZ;.078 DCR;1.1A;0402")
      (fields (field (name "APPROVED") "CL"))
      (libsource (lib "") (part "LSA6-03150_1"))
    )
    (comp (ref "L220")
      (value "15nH")
      (footprint "IND-0402HP")
      (description "INDUCTOR;15NH;2%;3.9GHZ SRF;85Q @1.7GHZ;.078 DCR;1.1A;0402")
      (fields (field (name "APPROVED") "CL"))
      (libsource (lib "") (part "LSA6-03150_1"))
    )
    (comp (ref "L221")
      (value "15nH")
      (footprint "IND-0402HP")
      (description "INDUCTOR;15NH;2%;3.9GHZ SRF;85Q @1.7GHZ;.078 DCR;1.1A;0402")
      (fields (field (name "APPROVED") "CL"))
      (libsource (lib "") (part "LSA6-03150_1"))
    )
    (comp (ref "L222")
      (value "15nH")
      (footprint "IND-0402HP")
      (description "INDUCTOR;15NH;2%;3.9GHZ SRF;85Q @1.7GHZ;.078 DCR;1.1A;0402")
      (fields (field (name "APPROVED") "CL"))
      (libsource (lib "") (part "LSA6-03150_1"))
    )
    (comp (ref "L223")
      (value "15nH")
      (footprint "IND-0402HP")
      (description "INDUCTOR;15NH;2%;3.9GHZ SRF;85Q @1.7GHZ;.078 DCR;1.1A;0402")
      (fields (field (name "APPROVED") "CL"))
      (libsource (lib "") (part "LSA6-03150_1"))
    )
    (comp (ref "L224")
      (value "15nH")
      (footprint "IND-0402HP")
      (description "INDUCTOR;15NH;2%;3.9GHZ SRF;85Q @1.7GHZ;.078 DCR;1.1A;0402")
      (fields (field (name "APPROVED") "CL"))
      (libsource (lib "") (part "LSA6-03150_1"))
    )
    (comp (ref "L225")
      (value "15nH")
      (footprint "IND-0402HP")
      (description "INDUCTOR;15NH;2%;3.9GHZ SRF;85Q @1.7GHZ;.078 DCR;1.1A;0402")
      (fields (field (name "APPROVED") "CL"))
      (libsource (lib "") (part "LSA6-03150_1"))
    )
    (comp (ref "R1")
      (value "49.9")
      (footprint "RES-0402-N")
      (description "49.9 OHMS;.06W;1%;200PPM;FILM;CHIP;0402")
      (fields (field (name "APPROVED") "CL"))
      (libsource (lib "Giga-tronics") (part "RK35-00499"))
    )
    (comp (ref "R3")
      (value "49.9")
      (footprint "RES-0402-N")
      (description "49.9 OHMS;.06W;1%;200PPM;FILM;CHIP;0402")
      (fields (field (name "APPROVED") "CL"))
      (libsource (lib "Giga-tronics") (part "RK35-00499"))
    )
    (comp (ref "R4")
      (value "39.2")
      (footprint "RES-2010-N")
      (description "39.2 OHM;.75W;1%;100PPM;FILM CHIP;2010")
      (fields (field (name "APPROVED") "CL"))
      (libsource (lib "Giga-tronics") (part "RK65-00392"))
    )
    (comp (ref "R171")
      (value "107")
      (footprint "RES-2010-N")
      (description "107 OHMS;0.75W;1%;100PPM;THICK FILM;CHIP;2010;RoHS")
      (fields (field (name "APPROVED") "CL"))
      (libsource (lib "Giga-tronics") (part "RK65-01107"))
    )
    (comp (ref "R178")
      (value "0")
      (footprint "RES-0603-N")
      (description "JUMPER;.05 OHMS MAX;1A MAX;0603")
      (fields (field (name "APPROVED") "CL"))
      (libsource (lib "Giga-tronics") (part "RK40-00000"))
    )
    (comp (ref "R179")
      (value "0")
      (footprint "RES-0603-N")
      (description "JUMPER;.05 OHMS MAX;1A MAX;0603")
      (fields (field (name "APPROVED") "CL"))
      (libsource (lib "Giga-tronics") (part "RK40-00000"))
    )
    (comp (ref "R180")
      (value "0")
      (footprint "RES-0603-N")
      (description "JUMPER;.05 OHMS MAX;1A MAX;0603")
      (fields (field (name "APPROVED") "CL"))
      (libsource (lib "Giga-tronics") (part "RK40-00000"))
    )
    (comp (ref "R181")
      (value "0")
      (footprint "RES-0603-N")
      (description "JUMPER;.05 OHMS MAX;1A MAX;0603")
      (fields (field (name "APPROVED") "CL"))
      (libsource (lib "Giga-tronics") (part "RK40-00000"))
    )
    (comp (ref "R182")
      (value "0")
      (footprint "RES-0603-N")
      (description "JUMPER;.05 OHMS MAX;1A MAX;0603")
      (fields (field (name "APPROVED") "CL"))
      (libsource (lib "Giga-tronics") (part "RK40-00000"))
    )
    (comp (ref "R183")
      (value "0")
      (footprint "RES-0603-N")
      (description "JUMPER;.05 OHMS MAX;1A MAX;0603")
      (fields (field (name "APPROVED") "CL"))
      (libsource (lib "Giga-tronics") (part "RK40-00000"))
    )
    (comp (ref "R319")
      (value "24.9")
      (footprint "RES-0402-N")
      (description "24.9 OHMS;.06W;1%;200PPM;FILM;CHIP;0402")
      (fields (field (name "APPROVED") "CL"))
      (libsource (lib "Giga-tronics") (part "RK35-00249"))
    )
    (comp (ref "R322")
      (value "24.9")
      (footprint "RES-0402-N")
      (description "24.9 OHMS;.06W;1%;200PPM;FILM;CHIP;0402")
      (fields (field (name "APPROVED") "CL"))
      (libsource (lib "Giga-tronics") (part "RK35-00249"))
    )
    (comp (ref "R401")
      (value "49.9")
      (footprint "RES-0402-N")
      (description "49.9 OHMS;.06W;1%;200PPM;FILM;CHIP;0402")
      (fields (field (name "APPROVED") "CL"))
      (libsource (lib "Giga-tronics") (part "RK35-00499"))
    )
    (comp (ref "R596")
      (value "49.9")
      (footprint "RES-0402-N")
      (description "49.9 OHMS;.06W;1%;200PPM;FILM;CHIP;0402")
      (fields (field (name "APPROVED") "CL"))
      (libsource (lib "Giga-tronics") (part "RK35-00499"))
    )
    (comp (ref "R597")
      (value "49.9")
      (footprint "RES-0402-N")
      (description "49.9 OHMS;.06W;1%;200PPM;FILM;CHIP;0402")
      (fields (field (name "APPROVED") "CL"))
      (libsource (lib "Giga-tronics") (part "RK35-00499"))
    )
    (comp (ref "R598")
      (value "49.9")
      (footprint "RES-0402-N")
      (description "49.9 OHMS;.06W;1%;200PPM;FILM;CHIP;0402")
      (fields (field (name "APPROVED") "CL"))
      (libsource (lib "Giga-tronics") (part "RK35-00499"))
    )
    (comp (ref "R599")
      (value "39.2")
      (footprint "RES-2010-N")
      (description "39.2 OHM;.75W;1%;100PPM;FILM CHIP;2010")
      (fields (field (name "APPROVED") "CL"))
      (libsource (lib "Giga-tronics") (part "RK65-00392"))
    )
    (comp (ref "R600")
      (value "49.9")
      (footprint "RES-0402-N")
      (description "49.9 OHMS;.06W;1%;200PPM;FILM;CHIP;0402")
      (fields (field (name "APPROVED") "CL"))
      (libsource (lib "Giga-tronics") (part "RK35-00499"))
    )
    (comp (ref "R601")
      (value "49.9")
      (footprint "RES-0402-N")
      (description "49.9 OHMS;.06W;1%;200PPM;FILM;CHIP;0402")
      (fields (field (name "APPROVED") "CL"))
      (libsource (lib "Giga-tronics") (part "RK35-00499"))
    )
    (comp (ref "R602")
      (value "49.9")
      (footprint "RES-0402-N")
      (description "49.9 OHMS;.06W;1%;200PPM;FILM;CHIP;0402")
      (fields (field (name "APPROVED") "CL"))
      (libsource (lib "Giga-tronics") (part "RK35-00499"))
    )
    (comp (ref "R603")
      (value "49.9")
      (footprint "RES-0402-N")
      (description "49.9 OHMS;.06W;1%;200PPM;FILM;CHIP;0402")
      (fields (field (name "APPROVED") "CL"))
      (libsource (lib "Giga-tronics") (part "RK35-00499"))
    )
    (comp (ref "R604")
      (value "49.9")
      (footprint "RES-0402-N")
      (description "49.9 OHMS;.06W;1%;200PPM;FILM;CHIP;0402")
      (fields (field (name "APPROVED") "CL"))
      (libsource (lib "Giga-tronics") (part "RK35-00499"))
    )
    (comp (ref "R605")
      (value "49.9")
      (footprint "RES-0402-N")
      (description "49.9 OHMS;.06W;1%;200PPM;FILM;CHIP;0402")
      (fields (field (name "APPROVED") "CL"))
      (libsource (lib "Giga-tronics") (part "RK35-00499"))
    )
    (comp (ref "R616")
      (value "24.9")
      (footprint "RES-0402-N")
      (description "24.9 OHMS;.06W;1%;200PPM;FILM;CHIP;0402")
      (fields (field (name "APPROVED") "CL"))
      (libsource (lib "Giga-tronics") (part "RK35-00249"))
    )
    (comp (ref "R617")
      (value "24.9")
      (footprint "RES-0402-N")
      (description "24.9 OHMS;.06W;1%;200PPM;FILM;CHIP;0402")
      (fields (field (name "APPROVED") "CL"))
      (libsource (lib "Giga-tronics") (part "RK35-00249"))
    )
    (comp (ref "R618")
      (value "24.9")
      (footprint "RES-0402-N")
      (description "24.9 OHMS;.06W;1%;200PPM;FILM;CHIP;0402")
      (fields (field (name "APPROVED") "CL"))
      (libsource (lib "Giga-tronics") (part "RK35-00249"))
    )
    (comp (ref "R619")
      (value "24.9")
      (footprint "RES-0402-N")
      (description "24.9 OHMS;.06W;1%;200PPM;FILM;CHIP;0402")
      (fields (field (name "APPROVED") "CL"))
      (libsource (lib "Giga-tronics") (part "RK35-00249"))
    )
    (comp (ref "R620")
      (value "24.9")
      (footprint "RES-0402-N")
      (description "24.9 OHMS;.06W;1%;200PPM;FILM;CHIP;0402")
      (fields (field (name "APPROVED") "CL"))
      (libsource (lib "Giga-tronics") (part "RK35-00249"))
    )
    (comp (ref "R621")
      (value "24.9")
      (footprint "RES-0402-N")
      (description "24.9 OHMS;.06W;1%;200PPM;FILM;CHIP;0402")
      (fields (field (name "APPROVED") "CL"))
      (libsource (lib "Giga-tronics") (part "RK35-00249"))
    )
    (comp (ref "R622")
      (value "24.9")
      (footprint "RES-0402-N")
      (description "24.9 OHMS;.06W;1%;200PPM;FILM;CHIP;0402")
      (fields (field (name "APPROVED") "CL"))
      (libsource (lib "Giga-tronics") (part "RK35-00249"))
    )
    (comp (ref "R623")
      (value "24.9")
      (footprint "RES-0402-N")
      (description "24.9 OHMS;.06W;1%;200PPM;FILM;CHIP;0402")
      (fields (field (name "APPROVED") "CL"))
      (libsource (lib "Giga-tronics") (part "RK35-00249"))
    )
    (comp (ref "R624")
      (value "24.9")
      (footprint "RES-0402-N")
      (description "24.9 OHMS;.06W;1%;200PPM;FILM;CHIP;0402")
      (fields (field (name "APPROVED") "CL"))
      (libsource (lib "Giga-tronics") (part "RK35-00249"))
    )
    (comp (ref "R625")
      (value "24.9")
      (footprint "RES-0402-N")
      (description "24.9 OHMS;.06W;1%;200PPM;FILM;CHIP;0402")
      (fields (field (name "APPROVED") "CL"))
      (libsource (lib "Giga-tronics") (part "RK35-00249"))
    )
    (comp (ref "R626")
      (value "24.9")
      (footprint "RES-0402-N")
      (description "24.9 OHMS;.06W;1%;200PPM;FILM;CHIP;0402")
      (fields (field (name "APPROVED") "CL"))
      (libsource (lib "Giga-tronics") (part "RK35-00249"))
    )
    (comp (ref "R627")
      (value "24.9")
      (footprint "RES-0402-N")
      (description "24.9 OHMS;.06W;1%;200PPM;FILM;CHIP;0402")
      (fields (field (name "APPROVED") "CL"))
      (libsource (lib "Giga-tronics") (part "RK35-00249"))
    )
    (comp (ref "R628")
      (value "24.9")
      (footprint "RES-0402-N")
      (description "24.9 OHMS;.06W;1%;200PPM;FILM;CHIP;0402")
      (fields (field (name "APPROVED") "CL"))
      (libsource (lib "Giga-tronics") (part "RK35-00249"))
    )
    (comp (ref "R629")
      (value "24.9")
      (footprint "RES-0402-N")
      (description "24.9 OHMS;.06W;1%;200PPM;FILM;CHIP;0402")
      (fields (field (name "APPROVED") "CL"))
      (libsource (lib "Giga-tronics") (part "RK35-00249"))
    )
    (comp (ref "R630")
      (value "24.9")
      (footprint "RES-0402-N")
      (description "24.9 OHMS;.06W;1%;200PPM;FILM;CHIP;0402")
      (fields (field (name "APPROVED") "CL"))
      (libsource (lib "Giga-tronics") (part "RK35-00249"))
    )
    (comp (ref "R631")
      (value "24.9")
      (footprint "RES-0402-N")
      (description "24.9 OHMS;.06W;1%;200PPM;FILM;CHIP;0402")
      (fields (field (name "APPROVED") "CL"))
      (libsource (lib "Giga-tronics") (part "RK35-00249"))
    )
    (comp (ref "R632")
      (value "24.9")
      (footprint "RES-0402-N")
      (description "24.9 OHMS;.06W;1%;200PPM;FILM;CHIP;0402")
      (fields (field (name "APPROVED") "CL"))
      (libsource (lib "Giga-tronics") (part "RK35-00249"))
    )
    (comp (ref "R633")
      (value "24.9")
      (footprint "RES-0402-N")
      (description "24.9 OHMS;.06W;1%;200PPM;FILM;CHIP;0402")
      (fields (field (name "APPROVED") "CL"))
      (libsource (lib "Giga-tronics") (part "RK35-00249"))
    )
    (comp (ref "R634")
      (value "24.9")
      (footprint "RES-0402-N")
      (description "24.9 OHMS;.06W;1%;200PPM;FILM;CHIP;0402")
      (fields (field (name "APPROVED") "CL"))
      (libsource (lib "Giga-tronics") (part "RK35-00249"))
    )
    (comp (ref "R635")
      (value "24.9")
      (footprint "RES-0402-N")
      (description "24.9 OHMS;.06W;1%;200PPM;FILM;CHIP;0402")
      (fields (field (name "APPROVED") "CL"))
      (libsource (lib "Giga-tronics") (part "RK35-00249"))
    )
    (comp (ref "R636")
      (value "20")
      (footprint "RES-0201-N")
      (description "20 OHMS;.05W;1%;200PPM;FILM CHIP;0201")
      (fields (field (name "APPROVED") "CL"))
      (libsource (lib "Giga-tronics") (part "RK30-00200"))
    )
    (comp (ref "R637")
      (value "20")
      (footprint "RES-0201-N")
      (description "20 OHMS;.05W;1%;200PPM;FILM CHIP;0201")
      (fields (field (name "APPROVED") "CL"))
      (libsource (lib "Giga-tronics") (part "RK30-00200"))
    )
    (comp (ref "R638")
      (value "24.9")
      (footprint "RES-0402-N")
      (description "24.9 OHMS;.06W;1%;200PPM;FILM;CHIP;0402")
      (fields (field (name "APPROVED") "CL"))
      (libsource (lib "Giga-tronics") (part "RK35-00249"))
    )
    (comp (ref "R639")
      (value "24.9")
      (footprint "RES-0402-N")
      (description "24.9 OHMS;.06W;1%;200PPM;FILM;CHIP;0402")
      (fields (field (name "APPROVED") "CL"))
      (libsource (lib "Giga-tronics") (part "RK35-00249"))
    )
    (comp (ref "R640")
      (value "24.9")
      (footprint "RES-0402-N")
      (description "24.9 OHMS;.06W;1%;200PPM;FILM;CHIP;0402")
      (fields (field (name "APPROVED") "CL"))
      (libsource (lib "Giga-tronics") (part "RK35-00249"))
    )
    (comp (ref "R641")
      (value "24.9")
      (footprint "RES-0402-N")
      (description "24.9 OHMS;.06W;1%;200PPM;FILM;CHIP;0402")
      (fields (field (name "APPROVED") "CL"))
      (libsource (lib "Giga-tronics") (part "RK35-00249"))
    )
    (comp (ref "R642")
      (value "24.9")
      (footprint "RES-0402-N")
      (description "24.9 OHMS;.06W;1%;200PPM;FILM;CHIP;0402")
      (fields (field (name "APPROVED") "CL"))
      (libsource (lib "Giga-tronics") (part "RK35-00249"))
    )
    (comp (ref "R643")
      (value "24.9")
      (footprint "RES-0402-N")
      (description "24.9 OHMS;.06W;1%;200PPM;FILM;CHIP;0402")
      (fields (field (name "APPROVED") "CL"))
      (libsource (lib "Giga-tronics") (part "RK35-00249"))
    )
    (comp (ref "R644")
      (value "24.9")
      (footprint "RES-0402-N")
      (description "24.9 OHMS;.06W;1%;200PPM;FILM;CHIP;0402")
      (fields (field (name "APPROVED") "CL"))
      (libsource (lib "Giga-tronics") (part "RK35-00249"))
    )
    (comp (ref "R645")
      (value "24.9")
      (footprint "RES-0402-N")
      (description "24.9 OHMS;.06W;1%;200PPM;FILM;CHIP;0402")
      (fields (field (name "APPROVED") "CL"))
      (libsource (lib "Giga-tronics") (part "RK35-00249"))
    )
    (comp (ref "R646")
      (value "24.9")
      (footprint "RES-0402-N")
      (description "24.9 OHMS;.06W;1%;200PPM;FILM;CHIP;0402")
      (fields (field (name "APPROVED") "CL"))
      (libsource (lib "Giga-tronics") (part "RK35-00249"))
    )
    (comp (ref "R647")
      (value "24.9")
      (footprint "RES-0402-N")
      (description "24.9 OHMS;.06W;1%;200PPM;FILM;CHIP;0402")
      (fields (field (name "APPROVED") "CL"))
      (libsource (lib "Giga-tronics") (part "RK35-00249"))
    )
    (comp (ref "R648")
      (value "24.9")
      (footprint "RES-0402-N")
      (description "24.9 OHMS;.06W;1%;200PPM;FILM;CHIP;0402")
      (fields (field (name "APPROVED") "CL"))
      (libsource (lib "Giga-tronics") (part "RK35-00249"))
    )
    (comp (ref "R649")
      (value "24.9")
      (footprint "RES-0402-N")
      (description "24.9 OHMS;.06W;1%;200PPM;FILM;CHIP;0402")
      (fields (field (name "APPROVED") "CL"))
      (libsource (lib "Giga-tronics") (part "RK35-00249"))
    )
    (comp (ref "U1")
      (value "MIXER;UP CONV;5-3500MHZ IF IN;5-4200MHZ LO/RF;CD542;RoHS")
      (footprint "CD542")
      (fields (field (name "G_PN") "MMTD-00004") (field (name "APPROVED") "NM"))
      (libsource (lib "Giga-tronics") (part "MMTD-00004"))
    )
    (comp (ref "U2")
      (value "AMP;0-6GHZ;20DB;+20DBM;5V;100MA;SOT-89")
      (footprint "SOT-89")
      (fields (field (name "G_PN") "MA20-00006") (field (name "APPROVED") "CL"))
      (libsource (lib "Giga-tronics") (part "MA20-00006"))
    )
    (comp (ref "U5")
      (value "MMIC SPDT;NON-REFLECTIVE;SWITCH;DC -12 GHz;RoHS")
      (footprint "QFN-24_HITTITE")
      (fields (field (name "M_PN") "HMC232LP4E") (field (name "APPROVED") "CL"))
      (libsource (lib "Giga-tronics") (part "MRSS-12012"))
    )
    (comp (ref "U6")
      (value "MMIC SPDT;NON-REFLECTIVE;SWITCH;DC -12 GHz;RoHS")
      (footprint "QFN-24_HITTITE")
      (fields (field (name "M_PN") "HMC232LP4E") (field (name "APPROVED") "CL"))
      (libsource (lib "Giga-tronics") (part "MRSS-12012"))
    )
    (comp (ref "U11")
      (value "AMP;0-6GHZ;20DB;+20DBM;5V;100MA;SOT-89")
      (footprint "SOT-89")
      (fields (field (name "G_PN") "MA20-00006") (field (name "APPROVED") "CL"))
      (libsource (lib "Giga-tronics") (part "MA20-00006"))
    )
    (comp (ref "U12")
      (value "MMIC SPDT;NON-REFLECTIVE;SWITCH;DC -12 GHz;RoHS")
      (footprint "QFN-24_HITTITE")
      (fields (field (name "M_PN") "HMC232LP4E") (field (name "APPROVED") "CL"))
      (libsource (lib "Giga-tronics") (part "MRSS-12012"))
    )
    (comp (ref "U14")
      (value "SWITCH;SP6T;DC-4GHZ;25DB ISO;20NS;27DBM P1;PQFN-36")
      (footprint "QFN36_MACOM")
      (fields (field (name "M_PN") "MASWCC0006") (field (name "APPROVED") "CL"))
      (libsource (lib "Giga-tronics") (part "MRSS-16004"))
    )
    (comp (ref "U16")
      (value "SWITCH;SP6T;DC-4GHZ;25DB ISO;20NS;27DBM P1;PQFN-36")
      (footprint "QFN36_MACOM")
      (fields (field (name "M_PN") "MASWCC0006") (field (name "APPROVED") "CL"))
      (libsource (lib "") (part "MRSS-16004_1"))
    )
    (comp (ref "U19")
      (value "MMIC SPDT;NON-REFLECTIVE;SWITCH;DC -12 GHz;RoHS")
      (footprint "QFN-24_HITTITE")
      (fields (field (name "M_PN") "HMC232LP4E") (field (name "APPROVED") "CL"))
      (libsource (lib "Giga-tronics") (part "MRSS-12012"))
    )
    (comp (ref "U21")
      (value "MMIC SPDT;NON-REFLECTIVE;SWITCH;DC -12 GHz;RoHS")
      (footprint "QFN-24_HITTITE")
      (fields (field (name "M_PN") "HMC232LP4E") (field (name "APPROVED") "CL"))
      (libsource (lib "Giga-tronics") (part "MRSS-12012"))
    )
    (comp (ref "U24")
      (value "MMIC SPDT;NON-REFLECTIVE;SWITCH;DC -12 GHz;RoHS")
      (footprint "QFN-24_HITTITE")
      (fields (field (name "M_PN") "HMC232LP4E") (field (name "APPROVED") "CL"))
      (libsource (lib "Giga-tronics") (part "MRSS-12012"))
    )
    (comp (ref "U109")
      (value "MMIC SPDT;NON-REFLECTIVE;SWITCH;DC -12 GHz;RoHS")
      (footprint "QFN-24_HITTITE")
      (fields (field (name "M_PN") "HMC232LP4E") (field (name "APPROVED") "CL"))
      (libsource (lib "Giga-tronics") (part "MRSS-12012"))
    )
    (comp (ref "U113")
      (value "MMIC SPDT;NON-REFLECTIVE;SWITCH;DC -12 GHz;RoHS")
      (footprint "QFN-24_HITTITE")
      (fields (field (name "M_PN") "HMC232LP4E") (field (name "APPROVED") "CL"))
      (libsource (lib "Giga-tronics") (part "MRSS-12012"))
    )
    (comp (ref "U126")
      (value "MMIC SPDT;NON-REFLECTIVE;SWITCH;DC -12 GHz;RoHS")
      (footprint "QFN-24_HITTITE")
      (fields (field (name "M_PN") "HMC232LP4E") (field (name "APPROVED") "CL"))
      (libsource (lib "Giga-tronics") (part "MRSS-12012"))
    )
    (comp (ref "U133")
      (value "AMP;0-6GHZ;20DB;+20DBM;5V;100MA;SOT-89")
      (footprint "SOT-89")
      (fields (field (name "G_PN") "MA20-00006") (field (name "APPROVED") "CL"))
      (libsource (lib "Giga-tronics") (part "MA20-00006"))
    )
    (comp (ref "U134")
      (value "MMIC SPDT;NON-REFLECTIVE;SWITCH;DC -12 GHz;RoHS")
      (footprint "QFN-24_HITTITE")
      (fields (field (name "M_PN") "HMC232LP4E") (field (name "APPROVED") "CL"))
      (libsource (lib "Giga-tronics") (part "MRSS-12012"))
    )
    (comp (ref "U135")
      (value "MMIC SPDT;NON-REFLECTIVE;SWITCH;DC -12 GHz;RoHS")
      (footprint "QFN-24_HITTITE")
      (fields (field (name "M_PN") "HMC232LP4E") (field (name "APPROVED") "CL"))
      (libsource (lib "Giga-tronics") (part "MRSS-12012"))
    )
    (comp (ref "U136")
      (value "MMIC SPDT;NON-REFLECTIVE;SWITCH;DC -12 GHz;RoHS")
      (footprint "QFN-24_HITTITE")
      (fields (field (name "M_PN") "HMC232LP4E") (field (name "APPROVED") "CL"))
      (libsource (lib "Giga-tronics") (part "MRSS-12012"))
    )
  )
  (nets
    (net (code "1") (name "+5V_ST") (class "Default")
      (node (ref "C388") (pin "1") (pintype "passive"))
      (node (ref "C741") (pin "1") (pintype "passive"))
      (node (ref "C742") (pin "1") (pintype "passive"))
      (node (ref "C930") (pin "2") (pintype "passive"))
      (node (ref "FT17") (pin "1") (pinfunction "1_1") (pintype "passive"))
      (node (ref "L138") (pin "1") (pinfunction "1_1") (pintype "passive"))
      (node (ref "L218") (pin "2") (pinfunction "2_2") (pintype "passive"))
    )
    (net (code "2") (name "+8V_ST") (class "Default")
      (node (ref "C2") (pin "1") (pintype "passive"))
      (node (ref "C3") (pin "1") (pintype "passive"))
      (node (ref "C768") (pin "1") (pintype "passive"))
      (node (ref "C770") (pin "2") (pintype "passive"))
      (node (ref "C771") (pin "2") (pintype "passive"))
      (node (ref "C811") (pin "1") (pintype "passive"))
      (node (ref "C816") (pin "1") (pintype "passive"))
      (node (ref "FT32") (pin "1") (pinfunction "1_1") (pintype "passive"))
      (node (ref "R171") (pin "1") (pintype "passive"))
      (node (ref "R4") (pin "1") (pintype "passive"))
      (node (ref "R599") (pin "2") (pintype "passive"))
    )
    (net (code "3") (name "-5V_ST") (class "Default")
      (node (ref "C436") (pin "1") (pintype "passive"))
      (node (ref "C743") (pin "1") (pintype "passive"))
      (node (ref "C747") (pin "1") (pintype "passive"))
      (node (ref "C919") (pin "2") (pintype "passive"))
      (node (ref "FT6") (pin "1") (pinfunction "1_1") (pintype "passive"))
      (node (ref "L167") (pin "1") (pinfunction "1_1") (pintype "passive"))
      (node (ref "L212") (pin "2") (pinfunction "2_2") (pintype "passive"))
    )
    (net (code "4") (name "/200_MHz_Comb") (class "Default")
      (node (ref "L2") (pin "1") (pinfunction "1_1") (pintype "passive"))
    )
    (net (code "5") (name "/2400MHz_Stalo") (class "Default")
      (node (ref "U1") (pin "6") (pinfunction "L_6") (pintype "passive"))
    )
    (net (code "6") (name "/SRD_BANK_1_NEG") (class "Default")
      (node (ref "C792") (pin "1") (pintype "passive"))
      (node (ref "C798") (pin "1") (pintype "passive"))
      (node (ref "R623") (pin "1") (pintype "passive"))
      (node (ref "R625") (pin "1") (pintype "passive"))
    )
    (net (code "7") (name "/SRD_BANK_1_POS") (class "Default")
      (node (ref "C938") (pin "1") (pintype "passive"))
      (node (ref "C940") (pin "1") (pintype "passive"))
      (node (ref "L222") (pin "1") (pinfunction "1_1") (pintype "passive"))
      (node (ref "L223") (pin "1") (pinfunction "1_1") (pintype "passive"))
    )
    (net (code "8") (name "/SRD_BANK_2_NEG") (class "Default")
      (node (ref "C899") (pin "1") (pintype "passive"))
      (node (ref "C901") (pin "1") (pintype "passive"))
      (node (ref "R627") (pin "1") (pintype "passive"))
      (node (ref "R629") (pin "1") (pintype "passive"))
    )
    (net (code "9") (name "/SRD_BANK_2_POS") (class "Default")
      (node (ref "C918") (pin "1") (pintype "passive"))
      (node (ref "C928") (pin "1") (pintype "passive"))
      (node (ref "L217") (pin "1") (pinfunction "1_1") (pintype "passive"))
      (node (ref "L219") (pin "1") (pinfunction "1_1") (pintype "passive"))
    )
    (net (code "10") (name "/SRD_BANK_3_NEG") (class "Default")
      (node (ref "C761") (pin "1") (pintype "passive"))
      (node (ref "C763") (pin "1") (pintype "passive"))
      (node (ref "R619") (pin "1") (pintype "passive"))
      (node (ref "R621") (pin "1") (pintype "passive"))
    )
    (net (code "11") (name "/SRD_BANK_3_POS") (class "Default")
      (node (ref "C941") (pin "1") (pintype "passive"))
      (node (ref "L224") (pin "1") (pinfunction "1_1") (pintype "passive"))
      (node (ref "R183") (pin "2") (pintype "passive"))
    )
    (net (code "12") (name "/SRD_BANK_4_NEG") (class "Default")
      (node (ref "C907") (pin "1") (pintype "passive"))
      (node (ref "C909") (pin "1") (pintype "passive"))
      (node (ref "R631") (pin "1") (pintype "passive"))
      (node (ref "R633") (pin "1") (pintype "passive"))
    )
    (net (code "13") (name "/SRD_BANK_4_POS") (class "Default")
      (node (ref "C926") (pin "1") (pintype "passive"))
      (node (ref "L216") (pin "1") (pinfunction "1_1") (pintype "passive"))
      (node (ref "R178") (pin "2") (pintype "passive"))
    )
    (net (code "14") (name "/SRD_BANK_5_NEG") (class "Default")
      (node (ref "C895") (pin "1") (pintype "passive"))
      (node (ref "C897") (pin "1") (pintype "passive"))
      (node (ref "R322") (pin "1") (pintype "passive"))
      (node (ref "R617") (pin "1") (pintype "passive"))
    )
    (net (code "15") (name "/SRD_BANK_5_POS") (class "Default")
      (node (ref "C942") (pin "1") (pintype "passive"))
      (node (ref "L225") (pin "1") (pinfunction "1_1") (pintype "passive"))
      (node (ref "R182") (pin "2") (pintype "passive"))
    )
    (net (code "16") (name "/SRD_BANK_6_NEG") (class "Default")
      (node (ref "C915") (pin "1") (pintype "passive"))
      (node (ref "C917") (pin "1") (pintype "passive"))
      (node (ref "R635") (pin "1") (pintype "passive"))
      (node (ref "R637") (pin "1") (pintype "passive"))
    )
    (net (code "17") (name "/SRD_BANK_6_POS") (class "Default")
      (node (ref "C924") (pin "1") (pintype "passive"))
      (node (ref "L215") (pin "1") (pinfunction "1_1") (pintype "passive"))
      (node (ref "R180") (pin "2") (pintype "passive"))
    )
    (net (code "18") (name "/STALO_LO") (class "Default")
      (node (ref "AT56") (pin "1") (pinfunction "IN/OUT_1") (pintype "passive"))
    )
    (net (code "19") (name "/~{SRD_BANK_1_NEG}") (class "Default")
      (node (ref "C764") (pin "1") (pintype "passive"))
      (node (ref "C797") (pin "1") (pintype "passive"))
      (node (ref "R622") (pin "1") (pintype "passive"))
      (node (ref "R624") (pin "1") (pintype "passive"))
    )
    (net (code "20") (name "/~{SRD_BANK_2_NEG}") (class "Default")
      (node (ref "C898") (pin "1") (pintype "passive"))
      (node (ref "C900") (pin "1") (pintype "passive"))
      (node (ref "R626") (pin "1") (pintype "passive"))
      (node (ref "R628") (pin "1") (pintype "passive"))
    )
    (net (code "21") (name "/~{SRD_BANK_3_NEG}") (class "Default")
      (node (ref "C760") (pin "1") (pintype "passive"))
      (node (ref "C762") (pin "1") (pintype "passive"))
      (node (ref "R618") (pin "1") (pintype "passive"))
      (node (ref "R620") (pin "1") (pintype "passive"))
    )
    (net (code "22") (name "/~{SRD_BANK_4_NEG}") (class "Default")
      (node (ref "C906") (pin "1") (pintype "passive"))
      (node (ref "C908") (pin "1") (pintype "passive"))
      (node (ref "R630") (pin "1") (pintype "passive"))
      (node (ref "R632") (pin "1") (pintype "passive"))
    )
    (net (code "23") (name "/~{SRD_BANK_5_NEG}") (class "Default")
      (node (ref "C754") (pin "1") (pintype "passive"))
      (node (ref "C896") (pin "1") (pintype "passive"))
      (node (ref "R319") (pin "1") (pintype "passive"))
      (node (ref "R616") (pin "1") (pintype "passive"))
    )
    (net (code "24") (name "/~{SRD_BANK_6_NEG}") (class "Default")
      (node (ref "C914") (pin "1") (pintype "passive"))
      (node (ref "C916") (pin "1") (pintype "passive"))
      (node (ref "R634") (pin "1") (pintype "passive"))
      (node (ref "R636") (pin "1") (pintype "passive"))
    )
    (net (code "25") (name "GND") (class "Default")
      (node (ref "AT1") (pin "2") (pinfunction "GND_2") (pintype "power_in"))
      (node (ref "AT10") (pin "2") (pinfunction "GND_2") (pintype "power_in"))
      (node (ref "AT12") (pin "2") (pinfunction "GND_2") (pintype "power_in"))
      (node (ref "AT14") (pin "2") (pinfunction "GND_2") (pintype "power_in"))
      (node (ref "AT3") (pin "2") (pinfunction "GND_2") (pintype "power_in"))
      (node (ref "AT43") (pin "2") (pinfunction "GND_2") (pintype "power_in"))
      (node (ref "AT44") (pin "2") (pinfunction "GND_2") (pintype "power_in"))
      (node (ref "AT45") (pin "2") (pinfunction "GND_2") (pintype "power_in"))
      (node (ref "AT46") (pin "2") (pinfunction "GND_2") (pintype "power_in"))
      (node (ref "AT47") (pin "2") (pinfunction "GND_2") (pintype "power_in"))
      (node (ref "AT48") (pin "2") (pinfunction "GND_2") (pintype "power_in"))
      (node (ref "AT49") (pin "2") (pinfunction "GND_2") (pintype "power_in"))
      (node (ref "AT50") (pin "2") (pinfunction "GND_2") (pintype "power_in"))
      (node (ref "AT51") (pin "2") (pinfunction "GND_2") (pintype "power_in"))
      (node (ref "AT52") (pin "2") (pinfunction "GND_2") (pintype "power_in"))
      (node (ref "AT56") (pin "2") (pinfunction "GND_2") (pintype "power_in"))
      (node (ref "AT6") (pin "2") (pinfunction "GND_2") (pintype "power_in"))
      (node (ref "AT72") (pin "2") (pinfunction "GND_2") (pintype "power_in"))
      (node (ref "C1") (pin "2") (pintype "passive"))
      (node (ref "C11") (pin "1") (pintype "passive"))
      (node (ref "C13") (pin "2") (pintype "passive"))
      (node (ref "C14") (pin "2") (pintype "passive"))
      (node (ref "C142") (pin "1") (pintype "passive"))
      (node (ref "C143") (pin "2") (pintype "passive"))
      (node (ref "C144") (pin "2") (pintype "passive"))
      (node (ref "C145") (pin "2") (pintype "passive"))
      (node (ref "C146") (pin "2") (pintype "passive"))
      (node (ref "C147") (pin "2") (pintype "passive"))
      (node (ref "C15") (pin "1") (pintype "passive"))
      (node (ref "C187") (pin "1") (pintype "passive"))
      (node (ref "C2") (pin "2") (pintype "passive"))
      (node (ref "C3") (pin "2") (pintype "passive"))
      (node (ref "C387") (pin "2") (pintype "passive"))
      (node (ref "C388") (pin "2") (pintype "passive"))
      (node (ref "C389") (pin "2") (pintype "passive"))
      (node (ref "C390") (pin "2") (pintype "passive"))
      (node (ref "C391") (pin "2") (pintype "passive"))
      (node (ref "C392") (pin "2") (pintype "passive"))
      (node (ref "C4") (pin "1") (pintype "passive"))
      (node (ref "C436") (pin "2") (pintype "passive"))
      (node (ref "C437") (pin "2") (pintype "passive"))
      (node (ref "C438") (pin "2") (pintype "passive"))
      (node (ref "C439") (pin "2") (pintype "passive"))
      (node (ref "C717") (pin "1") (pintype "passive"))
      (node (ref "C741") (pin "2") (pintype "passive"))
      (node (ref "C742") (pin "2") (pintype "passive"))
      (node (ref "C743") (pin "2") (pintype "passive"))
      (node (ref "C747") (pin "2") (pintype "passive"))
      (node (ref "C754") (pin "2") (pintype "passive"))
      (node (ref "C755") (pin "2") (pintype "passive"))
      (node (ref "C756") (pin "2") (pintype "passive"))
      (node (ref "C757") (pin "2") (pintype "passive"))
      (node (ref "C758") (pin "2") (pintype "passive"))
      (node (ref "C759") (pin "2") (pintype "passive"))
      (node (ref "C760") (pin "2") (pintype "passive"))
      (node (ref "C761") (pin "2") (pintype "passive"))
      (node (ref "C762") (pin "2") (pintype "passive"))
      (node (ref "C763") (pin "2") (pintype "passive"))
      (node (ref "C764") (pin "2") (pintype "passive"))
      (node (ref "C765") (pin "2") (pintype "passive"))
      (node (ref "C766") (pin "1") (pintype "passive"))
      (node (ref "C767") (pin "2") (pintype "passive"))
      (node (ref "C768") (pin "2") (pintype "passive"))
      (node (ref "C769") (pin "1") (pintype "passive"))
      (node (ref "C770") (pin "1") (pintype "passive"))
      (node (ref "C771") (pin "1") (pintype "passive"))
      (node (ref "C778") (pin "2") (pintype "passive"))
      (node (ref "C779") (pin "2") (pintype "passive"))
      (node (ref "C785") (pin "2") (pintype "passive"))
      (node (ref "C786") (pin "2") (pintype "passive"))
      (node (ref "C791") (pin "2") (pintype "passive"))
      (node (ref "C792") (pin "2") (pintype "passive"))
      (node (ref "C797") (pin "2") (pintype "passive"))
      (node (ref "C798") (pin "2") (pintype "passive"))
      (node (ref "C803") (pin "2") (pintype "passive"))
      (node (ref "C804") (pin "2") (pintype "passive"))
      (node (ref "C809") (pin "2") (pintype "passive"))
      (node (ref "C810") (pin "2") (pintype "passive"))
      (node (ref "C811") (pin "2") (pintype "passive"))
      (node (ref "C812") (pin "2") (pintype "passive"))
      (node (ref "C813") (pin "1") (pintype "passive"))
      (node (ref "C814") (pin "1") (pintype "passive"))
      (node (ref "C815") (pin "1") (pintype "passive"))
      (node (ref "C816") (pin "2") (pintype "passive"))
      (node (ref "C818") (pin "2") (pintype "passive"))
      (node (ref "C894") (pin "2") (pintype "passive"))
      (node (ref "C895") (pin "2") (pintype "passive"))
      (node (ref "C896") (pin "2") (pintype "passive"))
      (node (ref "C897") (pin "2") (pintype "passive"))
      (node (ref "C898") (pin "2") (pintype "passive"))
      (node (ref "C899") (pin "2") (pintype "passive"))
      (node (ref "C9") (pin "1") (pintype "passive"))
      (node (ref "C900") (pin "2") (pintype "passive"))
      (node (ref "C901") (pin "2") (pintype "passive"))
      (node (ref "C902") (pin "2") (pintype "passive"))
      (node (ref "C903") (pin "2") (pintype "passive"))
      (node (ref "C904") (pin "2") (pintype "passive"))
      (node (ref "C905") (pin "2") (pintype "passive"))
      (node (ref "C906") (pin "2") (pintype "passive"))
      (node (ref "C907") (pin "2") (pintype "passive"))
      (node (ref "C908") (pin "2") (pintype "passive"))
      (node (ref "C909") (pin "2") (pintype "passive"))
      (node (ref "C910") (pin "2") (pintype "passive"))
      (node (ref "C911") (pin "2") (pintype "passive"))
      (node (ref "C912") (pin "2") (pintype "passive"))
      (node (ref "C913") (pin "2") (pintype "passive"))
      (node (ref "C914") (pin "2") (pintype "passive"))
      (node (ref "C915") (pin "2") (pintype "passive"))
      (node (ref "C916") (pin "2") (pintype "passive"))
      (node (ref "C917") (pin "2") (pintype "passive"))
      (node (ref "C918") (pin "2") (pintype "passive"))
      (node (ref "C919") (pin "1") (pintype "passive"))
      (node (ref "C920") (pin "2") (pintype "passive"))
      (node (ref "C921") (pin "1") (pintype "passive"))
      (node (ref "C922") (pin "2") (pintype "passive"))
      (node (ref "C923") (pin "1") (pintype "passive"))
      (node (ref "C924") (pin "2") (pintype "passive"))
      (node (ref "C925") (pin "1") (pintype "passive"))
      (node (ref "C926") (pin "2") (pintype "passive"))
      (node (ref "C927") (pin "1") (pintype "passive"))
      (node (ref "C928") (pin "2") (pintype "passive"))
      (node (ref "C929") (pin "1") (pintype "passive"))
      (node (ref "C930") (pin "1") (pintype "passive"))
      (node (ref "C931") (pin "1") (pintype "passive"))
      (node (ref "C932") (pin "1") (pintype "passive"))
      (node (ref "C933") (pin "2") (pintype "passive"))
      (node (ref "C934") (pin "2") (pintype "passive"))
      (node (ref "C935") (pin "1") (pintype "passive"))
      (node (ref "C936") (pin "2") (pintype "passive"))
      (node (ref "C937") (pin "1") (pintype "passive"))
      (node (ref "C938") (pin "2") (pintype "passive"))
      (node (ref "C939") (pin "1") (pintype "passive"))
      (node (ref "C940") (pin "2") (pintype "passive"))
      (node (ref "C941") (pin "2") (pintype "passive"))
      (node (ref "C942") (pin "2") (pintype "passive"))
      (node (ref "C943") (pin "1") (pintype "passive"))
      (node (ref "C944") (pin "1") (pintype "passive"))
      (node (ref "C945") (pin "1") (pintype "passive"))
      (node (ref "FL1") (pin "2") (pinfunction "GND_2") (pintype "passive"))
      (node (ref "FL143") (pin "2") (pinfunction "GND_2") (pintype "passive"))
      (node (ref "FL144") (pin "2") (pinfunction "GND_2") (pintype "passive"))
      (node (ref "FL145") (pin "2") (pinfunction "GND_2") (pintype "passive"))
      (node (ref "FL146") (pin "2") (pinfunction "OUT_2") (pintype "passive"))
      (node (ref "FL146") (pin "4") (pinfunction "GND_4") (pintype "passive"))
      (node (ref "FL147") (pin "2") (pinfunction "GND_2") (pintype "passive"))
      (node (ref "FL148") (pin "2") (pinfunction "GND_2") (pintype "passive"))
      (node (ref "FL149") (pin "2") (pinfunction "GND_2") (pintype "passive"))
      (node (ref "FL150") (pin "2") (pinfunction "OUT_2") (pintype "passive"))
      (node (ref "FL150") (pin "4") (pinfunction "GND_4") (pintype "passive"))
      (node (ref "FL16") (pin "10") (pinfunction "10_10") (pintype "passive"))
      (node (ref "FL16") (pin "11") (pinfunction "11_11") (pintype "passive"))
      (node (ref "FL16") (pin "12") (pinfunction "12_12") (pintype "passive"))
      (node (ref "FL16") (pin "3") (pinfunction "3_3") (pintype "passive"))
      (node (ref "FL16") (pin "4") (pinfunction "4_4") (pintype "passive"))
      (node (ref "FL16") (pin "5") (pinfunction "5_5") (pintype "passive"))
      (node (ref "FL16") (pin "6") (pinfunction "6_6") (pintype "passive"))
      (node (ref "FL16") (pin "7") (pinfunction "7_7") (pintype "passive"))
      (node (ref "FL16") (pin "8") (pinfunction "8_8") (pintype "passive"))
      (node (ref "FL16") (pin "9") (pinfunction "9_9") (pintype "passive"))
      (node (ref "FL17") (pin "10") (pinfunction "10_10") (pintype "passive"))
      (node (ref "FL17") (pin "11") (pinfunction "11_11") (pintype "passive"))
      (node (ref "FL17") (pin "12") (pinfunction "12_12") (pintype "passive"))
      (node (ref "FL17") (pin "3") (pinfunction "3_3") (pintype "passive"))
      (node (ref "FL17") (pin "4") (pinfunction "4_4") (pintype "passive"))
      (node (ref "FL17") (pin "5") (pinfunction "5_5") (pintype "passive"))
      (node (ref "FL17") (pin "6") (pinfunction "6_6") (pintype "passive"))
      (node (ref "FL17") (pin "7") (pinfunction "7_7") (pintype "passive"))
      (node (ref "FL17") (pin "8") (pinfunction "8_8") (pintype "passive"))
      (node (ref "FL17") (pin "9") (pinfunction "9_9") (pintype "passive"))
      (node (ref "FL2") (pin "2") (pinfunction "GND_2") (pintype "passive"))
      (node (ref "FL24") (pin "10") (pinfunction "10_10") (pintype "passive"))
      (node (ref "FL24") (pin "11") (pinfunction "11_11") (pintype "passive"))
      (node (ref "FL24") (pin "12") (pinfunction "12_12") (pintype "passive"))
      (node (ref "FL24") (pin "3") (pinfunction "3_3") (pintype "passive"))
      (node (ref "FL24") (pin "4") (pinfunction "4_4") (pintype "passive"))
      (node (ref "FL24") (pin "5") (pinfunction "5_5") (pintype "passive"))
      (node (ref "FL24") (pin "6") (pinfunction "6_6") (pintype "passive"))
      (node (ref "FL24") (pin "7") (pinfunction "7_7") (pintype "passive"))
      (node (ref "FL24") (pin "8") (pinfunction "8_8") (pintype "passive"))
      (node (ref "FL24") (pin "9") (pinfunction "9_9") (pintype "passive"))
      (node (ref "FL25") (pin "10") (pinfunction "10_10") (pintype "passive"))
      (node (ref "FL25") (pin "11") (pinfunction "11_11") (pintype "passive"))
      (node (ref "FL25") (pin "12") (pinfunction "12_12") (pintype "passive"))
      (node (ref "FL25") (pin "3") (pinfunction "3_3") (pintype "passive"))
      (node (ref "FL25") (pin "4") (pinfunction "4_4") (pintype "passive"))
      (node (ref "FL25") (pin "5") (pinfunction "5_5") (pintype "passive"))
      (node (ref "FL25") (pin "6") (pinfunction "6_6") (pintype "passive"))
      (node (ref "FL25") (pin "7") (pinfunction "7_7") (pintype "passive"))
      (node (ref "FL25") (pin "8") (pinfunction "8_8") (pintype "passive"))
      (node (ref "FL25") (pin "9") (pinfunction "9_9") (pintype "passive"))
      (node (ref "FL3") (pin "2") (pinfunction "GND_2") (pintype "passive"))
      (node (ref "FL30") (pin "10") (pinfunction "10_10") (pintype "passive"))
      (node (ref "FL30") (pin "11") (pinfunction "11_11") (pintype "passive"))
      (node (ref "FL30") (pin "12") (pinfunction "12_12") (pintype "passive"))
      (node (ref "FL30") (pin "3") (pinfunction "3_3") (pintype "passive"))
      (node (ref "FL30") (pin "4") (pinfunction "4_4") (pintype "passive"))
      (node (ref "FL30") (pin "5") (pinfunction "5_5") (pintype "passive"))
      (node (ref "FL30") (pin "6") (pinfunction "6_6") (pintype "passive"))
      (node (ref "FL30") (pin "7") (pinfunction "7_7") (pintype "passive"))
      (node (ref "FL30") (pin "8") (pinfunction "8_8") (pintype "passive"))
      (node (ref "FL30") (pin "9") (pinfunction "9_9") (pintype "passive"))
      (node (ref "FL31") (pin "10") (pinfunction "10_10") (pintype "passive"))
      (node (ref "FL31") (pin "11") (pinfunction "11_11") (pintype "passive"))
      (node (ref "FL31") (pin "12") (pinfunction "12_12") (pintype "passive"))
      (node (ref "FL31") (pin "3") (pinfunction "3_3") (pintype "passive"))
      (node (ref "FL31") (pin "4") (pinfunction "4_4") (pintype "passive"))
      (node (ref "FL31") (pin "5") (pinfunction "5_5") (pintype "passive"))
      (node (ref "FL31") (pin "6") (pinfunction "6_6") (pintype "passive"))
      (node (ref "FL31") (pin "7") (pinfunction "7_7") (pintype "passive"))
      (node (ref "FL31") (pin "8") (pinfunction "8_8") (pintype "passive"))
      (node (ref "FL31") (pin "9") (pinfunction "9_9") (pintype "passive"))
      (node (ref "FL35") (pin "10") (pinfunction "10_10") (pintype "passive"))
      (node (ref "FL35") (pin "11") (pinfunction "11_11") (pintype "passive"))
      (node (ref "FL35") (pin "12") (pinfunction "12_12") (pintype "passive"))
      (node (ref "FL35") (pin "3") (pinfunction "3_3") (pintype "passive"))
      (node (ref "FL35") (pin "4") (pinfunction "4_4") (pintype "passive"))
      (node (ref "FL35") (pin "5") (pinfunction "5_5") (pintype "passive"))
      (node (ref "FL35") (pin "6") (pinfunction "6_6") (pintype "passive"))
      (node (ref "FL35") (pin "7") (pinfunction "7_7") (pintype "passive"))
      (node (ref "FL35") (pin "8") (pinfunction "8_8") (pintype "passive"))
      (node (ref "FL35") (pin "9") (pinfunction "9_9") (pintype "passive"))
      (node (ref "FL36") (pin "10") (pinfunction "10_10") (pintype "passive"))
      (node (ref "FL36") (pin "11") (pinfunction "11_11") (pintype "passive"))
      (node (ref "FL36") (pin "12") (pinfunction "12_12") (pintype "passive"))
      (node (ref "FL36") (pin "3") (pinfunction "3_3") (pintype "passive"))
      (node (ref "FL36") (pin "4") (pinfunction "4_4") (pintype "passive"))
      (node (ref "FL36") (pin "5") (pinfunction "5_5") (pintype "passive"))
      (node (ref "FL36") (pin "6") (pinfunction "6_6") (pintype "passive"))
      (node (ref "FL36") (pin "7") (pinfunction "7_7") (pintype "passive"))
      (node (ref "FL36") (pin "8") (pinfunction "8_8") (pintype "passive"))
      (node (ref "FL36") (pin "9") (pinfunction "9_9") (pintype "passive"))
      (node (ref "FL4") (pin "2") (pinfunction "GND_2") (pintype "passive"))
      (node (ref "FL4") (pin "4") (pinfunction "GND_4") (pintype "passive"))
      (node (ref "FL4") (pin "5") (pinfunction "GND_5") (pintype "passive"))
      (node (ref "FL4") (pin "6") (pinfunction "GND_6") (pintype "passive"))
      (node (ref "FL40") (pin "10") (pinfunction "10_10") (pintype "passive"))
      (node (ref "FL40") (pin "11") (pinfunction "11_11") (pintype "passive"))
      (node (ref "FL40") (pin "12") (pinfunction "12_12") (pintype "passive"))
      (node (ref "FL40") (pin "3") (pinfunction "3_3") (pintype "passive"))
      (node (ref "FL40") (pin "4") (pinfunction "4_4") (pintype "passive"))
      (node (ref "FL40") (pin "5") (pinfunction "5_5") (pintype "passive"))
      (node (ref "FL40") (pin "6") (pinfunction "6_6") (pintype "passive"))
      (node (ref "FL40") (pin "7") (pinfunction "7_7") (pintype "passive"))
      (node (ref "FL40") (pin "8") (pinfunction "8_8") (pintype "passive"))
      (node (ref "FL40") (pin "9") (pinfunction "9_9") (pintype "passive"))
      (node (ref "FL41") (pin "10") (pinfunction "10_10") (pintype "passive"))
      (node (ref "FL41") (pin "11") (pinfunction "11_11") (pintype "passive"))
      (node (ref "FL41") (pin "12") (pinfunction "12_12") (pintype "passive"))
      (node (ref "FL41") (pin "3") (pinfunction "3_3") (pintype "passive"))
      (node (ref "FL41") (pin "4") (pinfunction "4_4") (pintype "passive"))
      (node (ref "FL41") (pin "5") (pinfunction "5_5") (pintype "passive"))
      (node (ref "FL41") (pin "6") (pinfunction "6_6") (pintype "passive"))
      (node (ref "FL41") (pin "7") (pinfunction "7_7") (pintype "passive"))
      (node (ref "FL41") (pin "8") (pinfunction "8_8") (pintype "passive"))
      (node (ref "FL41") (pin "9") (pinfunction "9_9") (pintype "passive"))
      (node (ref "FL7") (pin "10") (pinfunction "10_10") (pintype "passive"))
      (node (ref "FL7") (pin "11") (pinfunction "11_11") (pintype "passive"))
      (node (ref "FL7") (pin "12") (pinfunction "12_12") (pintype "passive"))
      (node (ref "FL7") (pin "3") (pinfunction "3_3") (pintype "passive"))
      (node (ref "FL7") (pin "4") (pinfunction "4_4") (pintype "passive"))
      (node (ref "FL7") (pin "5") (pinfunction "5_5") (pintype "passive"))
      (node (ref "FL7") (pin "6") (pinfunction "6_6") (pintype "passive"))
      (node (ref "FL7") (pin "7") (pinfunction "7_7") (pintype "passive"))
      (node (ref "FL7") (pin "8") (pinfunction "8_8") (pintype "passive"))
      (node (ref "FL7") (pin "9") (pinfunction "9_9") (pintype "passive"))
      (node (ref "FL8") (pin "10") (pinfunction "10_10") (pintype "passive"))
      (node (ref "FL8") (pin "11") (pinfunction "11_11") (pintype "passive"))
      (node (ref "FL8") (pin "12") (pinfunction "12_12") (pintype "passive"))
      (node (ref "FL8") (pin "3") (pinfunction "3_3") (pintype "passive"))
      (node (ref "FL8") (pin "4") (pinfunction "4_4") (pintype "passive"))
      (node (ref "FL8") (pin "5") (pinfunction "5_5") (pintype "passive"))
      (node (ref "FL8") (pin "6") (pinfunction "6_6") (pintype "passive"))
      (node (ref "FL8") (pin "7") (pinfunction "7_7") (pintype "passive"))
      (node (ref "FL8") (pin "8") (pinfunction "8_8") (pintype "passive"))
      (node (ref "FL8") (pin "9") (pinfunction "9_9") (pintype "passive"))
      (node (ref "FL93") (pin "2") (pinfunction "GND_2") (pintype "passive"))
      (node (ref "FL93") (pin "4") (pinfunction "GND_4") (pintype "passive"))
      (node (ref "J23") (pin "2") (pinfunction "GND_2") (pintype "passive"))
      (node (ref "J24") (pin "2") (pinfunction "GND_2") (pintype "passive"))
      (node (ref "L46") (pin "1") (pinfunction "1_1") (pintype "passive"))
      (node (ref "L52") (pin "1") (pinfunction "1_1") (pintype "passive"))
      (node (ref "L53") (pin "1") (pinfunction "1_1") (pintype "passive"))
      (node (ref "L58") (pin "1") (pinfunction "1_1") (pintype "passive"))
      (node (ref "L6") (pin "1") (pinfunction "1_1") (pintype "passive"))
      (node (ref "L60") (pin "1") (pinfunction "1_1") (pintype "passive"))
      (node (ref "L61") (pin "1") (pinfunction "1_1") (pintype "passive"))
      (node (ref "L62") (pin "1") (pinfunction "1_1") (pintype "passive"))
      (node (ref "L63") (pin "1") (pinfunction "1_1") (pintype "passive"))
      (node (ref "L64") (pin "1") (pinfunction "1_1") (pintype "passive"))
      (node (ref "L7") (pin "1") (pinfunction "1_1") (pintype "passive"))
      (node (ref "L70") (pin "1") (pinfunction "1_1") (pintype "passive"))
      (node (ref "L72") (pin "1") (pinfunction "1_1") (pintype "passive"))
      (node (ref "L74") (pin "1") (pinfunction "1_1") (pintype "passive"))
      (node (ref "L75") (pin "1") (pinfunction "1_1") (pintype "passive"))
      (node (ref "L80") (pin "1") (pinfunction "1_1") (pintype "passive"))
      (node (ref "L81") (pin "1") (pinfunction "1_1") (pintype "passive"))
      (node (ref "L82") (pin "1") (pinfunction "1_1") (pintype "passive"))
      (node (ref "L83") (pin "1") (pinfunction "1_1") (pintype "passive"))
      (node (ref "L86") (pin "1") (pinfunction "1_1") (pintype "passive"))
      (node (ref "L87") (pin "1") (pinfunction "1_1") (pintype "passive"))
      (node (ref "L92") (pin "1") (pinfunction "1_1") (pintype "passive"))
      (node (ref "L93") (pin "1") (pinfunction "1_1") (pintype "passive"))
      (node (ref "L94") (pin "1") (pinfunction "1_1") (pintype "passive"))
      (node (ref "L95") (pin "1") (pinfunction "1_1") (pintype "passive"))
      (node (ref "L97") (pin "1") (pinfunction "1_1") (pintype "passive"))
      (node (ref "R1") (pin "2") (pintype "passive"))
      (node (ref "R3") (pin "2") (pintype "passive"))
      (node (ref "R401") (pin "2") (pintype "passive"))
      (node (ref "R596") (pin "2") (pintype "passive"))
      (node (ref "R597") (pin "2") (pintype "passive"))
      (node (ref "R598") (pin "2") (pintype "passive"))
      (node (ref "R600") (pin "2") (pintype "passive"))
      (node (ref "R601") (pin "2") (pintype "passive"))
      (node (ref "R602") (pin "2") (pintype "passive"))
      (node (ref "R603") (pin "2") (pintype "passive"))
      (node (ref "R604") (pin "2") (pintype "passive"))
      (node (ref "R605") (pin "2") (pintype "passive"))
      (node (ref "U1") (pin "1") (pinfunction "GND_1") (pintype "passive"))
      (node (ref "U1") (pin "4") (pinfunction "GND_4") (pintype "passive"))
      (node (ref "U1") (pin "5") (pinfunction "GND_5") (pintype "passive"))
      (node (ref "U109") (pin "1") (pinfunction "Vdd_1") (pintype "passive"))
      (node (ref "U109") (pin "10") (pinfunction "G_10") (pintype "passive"))
      (node (ref "U109") (pin "11") (pinfunction "NC_11") (pintype "passive"))
      (node (ref "U109") (pin "12") (pinfunction "RF2_12") (pintype "passive"))
      (node (ref "U109") (pin "13") (pinfunction "NC_13") (pintype "passive"))
      (node (ref "U109") (pin "14") (pinfunction "NC_14") (pintype "passive"))
      (node (ref "U109") (pin "17") (pinfunction "NC_17") (pintype "passive"))
      (node (ref "U109") (pin "18") (pinfunction "NC_18") (pintype "passive"))
      (node (ref "U109") (pin "19") (pinfunction "NC_19") (pintype "passive"))
      (node (ref "U109") (pin "2") (pinfunction "Vctl_2") (pintype "passive"))
      (node (ref "U109") (pin "20") (pinfunction "NC_20") (pintype "passive"))
      (node (ref "U109") (pin "21") (pinfunction "G_21") (pintype "passive"))
      (node (ref "U109") (pin "23") (pinfunction "G_23") (pintype "passive"))
      (node (ref "U109") (pin "24") (pinfunction "NC_24") (pintype "passive"))
      (node (ref "U109") (pin "25") (pinfunction "G_25") (pintype "passive"))
      (node (ref "U109") (pin "3") (pinfunction "G_3") (pintype "passive"))
      (node (ref "U109") (pin "5") (pinfunction "G_5") (pintype "passive"))
      (node (ref "U109") (pin "6") (pinfunction "NC_6") (pintype "passive"))
      (node (ref "U109") (pin "7") (pinfunction "NC_7") (pintype "passive"))
      (node (ref "U109") (pin "8") (pinfunction "G_8") (pintype "passive"))
      (node (ref "U11") (pin "2") (pinfunction "GND_2") (pintype "passive"))
      (node (ref "U11") (pin "4") (pinfunction "4_4") (pintype "passive"))
      (node (ref "U113") (pin "1") (pinfunction "Vdd_1") (pintype "passive"))
      (node (ref "U113") (pin "10") (pinfunction "G_10") (pintype "passive"))
      (node (ref "U113") (pin "11") (pinfunction "NC_11") (pintype "passive"))
      (node (ref "U113") (pin "12") (pinfunction "RF2_12") (pintype "passive"))
      (node (ref "U113") (pin "13") (pinfunction "NC_13") (pintype "passive"))
      (node (ref "U113") (pin "14") (pinfunction "NC_14") (pintype "passive"))
      (node (ref "U113") (pin "17") (pinfunction "NC_17") (pintype "passive"))
      (node (ref "U113") (pin "18") (pinfunction "NC_18") (pintype "passive"))
      (node (ref "U113") (pin "19") (pinfunction "NC_19") (pintype "passive"))
      (node (ref "U113") (pin "2") (pinfunction "Vctl_2") (pintype "passive"))
      (node (ref "U113") (pin "20") (pinfunction "NC_20") (pintype "passive"))
      (node (ref "U113") (pin "21") (pinfunction "G_21") (pintype "passive"))
      (node (ref "U113") (pin "23") (pinfunction "G_23") (pintype "passive"))
      (node (ref "U113") (pin "24") (pinfunction "NC_24") (pintype "passive"))
      (node (ref "U113") (pin "25") (pinfunction "G_25") (pintype "passive"))
      (node (ref "U113") (pin "3") (pinfunction "G_3") (pintype "passive"))
      (node (ref "U113") (pin "5") (pinfunction "G_5") (pintype "passive"))
      (node (ref "U113") (pin "6") (pinfunction "NC_6") (pintype "passive"))
      (node (ref "U113") (pin "7") (pinfunction "NC_7") (pintype "passive"))
      (node (ref "U113") (pin "8") (pinfunction "G_8") (pintype "passive"))
      (node (ref "U12") (pin "1") (pinfunction "Vdd_1") (pintype "passive"))
      (node (ref "U12") (pin "10") (pinfunction "G_10") (pintype "passive"))
      (node (ref "U12") (pin "11") (pinfunction "NC_11") (pintype "passive"))
      (node (ref "U12") (pin "12") (pinfunction "RF2_12") (pintype "passive"))
      (node (ref "U12") (pin "13") (pinfunction "NC_13") (pintype "passive"))
      (node (ref "U12") (pin "14") (pinfunction "NC_14") (pintype "passive"))
      (node (ref "U12") (pin "17") (pinfunction "NC_17") (pintype "passive"))
      (node (ref "U12") (pin "18") (pinfunction "NC_18") (pintype "passive"))
      (node (ref "U12") (pin "19") (pinfunction "NC_19") (pintype "passive"))
      (node (ref "U12") (pin "2") (pinfunction "Vctl_2") (pintype "passive"))
      (node (ref "U12") (pin "20") (pinfunction "NC_20") (pintype "passive"))
      (node (ref "U12") (pin "21") (pinfunction "G_21") (pintype "passive"))
      (node (ref "U12") (pin "23") (pinfunction "G_23") (pintype "passive"))
      (node (ref "U12") (pin "24") (pinfunction "NC_24") (pintype "passive"))
      (node (ref "U12") (pin "25") (pinfunction "G_25") (pintype "passive"))
      (node (ref "U12") (pin "3") (pinfunction "G_3") (pintype "passive"))
      (node (ref "U12") (pin "5") (pinfunction "G_5") (pintype "passive"))
      (node (ref "U12") (pin "6") (pinfunction "NC_6") (pintype "passive"))
      (node (ref "U12") (pin "7") (pinfunction "NC_7") (pintype "passive"))
      (node (ref "U12") (pin "8") (pinfunction "G_8") (pintype "passive"))
      (node (ref "U126") (pin "1") (pinfunction "Vdd_1") (pintype "passive"))
      (node (ref "U126") (pin "10") (pinfunction "G_10") (pintype "passive"))
      (node (ref "U126") (pin "11") (pinfunction "NC_11") (pintype "passive"))
      (node (ref "U126") (pin "12") (pinfunction "RF2_12") (pintype "passive"))
      (node (ref "U126") (pin "13") (pinfunction "NC_13") (pintype "passive"))
      (node (ref "U126") (pin "14") (pinfunction "NC_14") (pintype "passive"))
      (node (ref "U126") (pin "17") (pinfunction "NC_17") (pintype "passive"))
      (node (ref "U126") (pin "18") (pinfunction "NC_18") (pintype "passive"))
      (node (ref "U126") (pin "19") (pinfunction "NC_19") (pintype "passive"))
      (node (ref "U126") (pin "2") (pinfunction "Vctl_2") (pintype "passive"))
      (node (ref "U126") (pin "20") (pinfunction "NC_20") (pintype "passive"))
      (node (ref "U126") (pin "21") (pinfunction "G_21") (pintype "passive"))
      (node (ref "U126") (pin "23") (pinfunction "G_23") (pintype "passive"))
      (node (ref "U126") (pin "24") (pinfunction "NC_24") (pintype "passive"))
      (node (ref "U126") (pin "25") (pinfunction "G_25") (pintype "passive"))
      (node (ref "U126") (pin "3") (pinfunction "G_3") (pintype "passive"))
      (node (ref "U126") (pin "5") (pinfunction "G_5") (pintype "passive"))
      (node (ref "U126") (pin "6") (pinfunction "NC_6") (pintype "passive"))
      (node (ref "U126") (pin "7") (pinfunction "NC_7") (pintype "passive"))
      (node (ref "U126") (pin "8") (pinfunction "G_8") (pintype "passive"))
      (node (ref "U133") (pin "2") (pinfunction "GND_2") (pintype "passive"))
      (node (ref "U133") (pin "4") (pinfunction "4_4") (pintype "passive"))
      (node (ref "U134") (pin "1") (pinfunction "Vdd_1") (pintype "passive"))
      (node (ref "U134") (pin "10") (pinfunction "G_10") (pintype "passive"))
      (node (ref "U134") (pin "11") (pinfunction "NC_11") (pintype "passive"))
      (node (ref "U134") (pin "12") (pinfunction "RF2_12") (pintype "passive"))
      (node (ref "U134") (pin "13") (pinfunction "NC_13") (pintype "passive"))
      (node (ref "U134") (pin "14") (pinfunction "NC_14") (pintype "passive"))
      (node (ref "U134") (pin "17") (pinfunction "NC_17") (pintype "passive"))
      (node (ref "U134") (pin "18") (pinfunction "NC_18") (pintype "passive"))
      (node (ref "U134") (pin "19") (pinfunction "NC_19") (pintype "passive"))
      (node (ref "U134") (pin "2") (pinfunction "Vctl_2") (pintype "passive"))
      (node (ref "U134") (pin "20") (pinfunction "NC_20") (pintype "passive"))
      (node (ref "U134") (pin "21") (pinfunction "G_21") (pintype "passive"))
      (node (ref "U134") (pin "23") (pinfunction "G_23") (pintype "passive"))
      (node (ref "U134") (pin "24") (pinfunction "NC_24") (pintype "passive"))
      (node (ref "U134") (pin "25") (pinfunction "G_25") (pintype "passive"))
      (node (ref "U134") (pin "3") (pinfunction "G_3") (pintype "passive"))
      (node (ref "U134") (pin "5") (pinfunction "G_5") (pintype "passive"))
      (node (ref "U134") (pin "6") (pinfunction "NC_6") (pintype "passive"))
      (node (ref "U134") (pin "7") (pinfunction "NC_7") (pintype "passive"))
      (node (ref "U134") (pin "8") (pinfunction "G_8") (pintype "passive"))
      (node (ref "U135") (pin "1") (pinfunction "Vdd_1") (pintype "passive"))
      (node (ref "U135") (pin "10") (pinfunction "G_10") (pintype "passive"))
      (node (ref "U135") (pin "11") (pinfunction "NC_11") (pintype "passive"))
      (node (ref "U135") (pin "12") (pinfunction "RF2_12") (pintype "passive"))
      (node (ref "U135") (pin "13") (pinfunction "NC_13") (pintype "passive"))
      (node (ref "U135") (pin "14") (pinfunction "NC_14") (pintype "passive"))
      (node (ref "U135") (pin "17") (pinfunction "NC_17") (pintype "passive"))
      (node (ref "U135") (pin "18") (pinfunction "NC_18") (pintype "passive"))
      (node (ref "U135") (pin "19") (pinfunction "NC_19") (pintype "passive"))
      (node (ref "U135") (pin "2") (pinfunction "Vctl_2") (pintype "passive"))
      (node (ref "U135") (pin "20") (pinfunction "NC_20") (pintype "passive"))
      (node (ref "U135") (pin "21") (pinfunction "G_21") (pintype "passive"))
      (node (ref "U135") (pin "23") (pinfunction "G_23") (pintype "passive"))
      (node (ref "U135") (pin "24") (pinfunction "NC_24") (pintype "passive"))
      (node (ref "U135") (pin "25") (pinfunction "G_25") (pintype "passive"))
      (node (ref "U135") (pin "3") (pinfunction "G_3") (pintype "passive"))
      (node (ref "U135") (pin "5") (pinfunction "G_5") (pintype "passive"))
      (node (ref "U135") (pin "6") (pinfunction "NC_6") (pintype "passive"))
      (node (ref "U135") (pin "7") (pinfunction "NC_7") (pintype "passive"))
      (node (ref "U135") (pin "8") (pinfunction "G_8") (pintype "passive"))
      (node (ref "U136") (pin "1") (pinfunction "Vdd_1") (pintype "passive"))
      (node (ref "U136") (pin "10") (pinfunction "G_10") (pintype "passive"))
      (node (ref "U136") (pin "11") (pinfunction "NC_11") (pintype "passive"))
      (node (ref "U136") (pin "12") (pinfunction "RF2_12") (pintype "passive"))
      (node (ref "U136") (pin "13") (pinfunction "NC_13") (pintype "passive"))
      (node (ref "U136") (pin "14") (pinfunction "NC_14") (pintype "passive"))
      (node (ref "U136") (pin "17") (pinfunction "NC_17") (pintype "passive"))
      (node (ref "U136") (pin "18") (pinfunction "NC_18") (pintype "passive"))
      (node (ref "U136") (pin "19") (pinfunction "NC_19") (pintype "passive"))
      (node (ref "U136") (pin "2") (pinfunction "Vctl_2") (pintype "passive"))
      (node (ref "U136") (pin "20") (pinfunction "NC_20") (pintype "passive"))
      (node (ref "U136") (pin "21") (pinfunction "G_21") (pintype "passive"))
      (node (ref "U136") (pin "23") (pinfunction "G_23") (pintype "passive"))
      (node (ref "U136") (pin "24") (pinfunction "NC_24") (pintype "passive"))
      (node (ref "U136") (pin "25") (pinfunction "G_25") (pintype "passive"))
      (node (ref "U136") (pin "3") (pinfunction "G_3") (pintype "passive"))
      (node (ref "U136") (pin "5") (pinfunction "G_5") (pintype "passive"))
      (node (ref "U136") (pin "6") (pinfunction "NC_6") (pintype "passive"))
      (node (ref "U136") (pin "7") (pinfunction "NC_7") (pintype "passive"))
      (node (ref "U136") (pin "8") (pinfunction "G_8") (pintype "passive"))
      (node (ref "U14") (pin "11") (pinfunction "GND_11") (pintype "passive"))
      (node (ref "U14") (pin "13") (pinfunction "GND_13") (pintype "passive"))
      (node (ref "U14") (pin "15") (pinfunction "GND_15") (pintype "passive"))
      (node (ref "U14") (pin "17") (pinfunction "GND_17") (pintype "passive"))
      (node (ref "U14") (pin "19") (pinfunction "GND_19") (pintype "passive"))
      (node (ref "U14") (pin "21") (pinfunction "GND_21") (pintype "passive"))
      (node (ref "U14") (pin "23") (pinfunction "GND_23") (pintype "passive"))
      (node (ref "U14") (pin "24") (pinfunction "GND_24") (pintype "passive"))
      (node (ref "U14") (pin "26") (pinfunction "GND_26") (pintype "passive"))
      (node (ref "U14") (pin "28") (pinfunction "GND_28") (pintype "passive"))
      (node (ref "U14") (pin "30") (pinfunction "GND_30") (pintype "passive"))
      (node (ref "U14") (pin "37") (pinfunction "GND_37") (pintype "passive"))
      (node (ref "U16") (pin "11") (pinfunction "GND_11") (pintype "passive"))
      (node (ref "U16") (pin "13") (pinfunction "GND_13") (pintype "passive"))
      (node (ref "U16") (pin "15") (pinfunction "GND_15") (pintype "passive"))
      (node (ref "U16") (pin "17") (pinfunction "GND_17") (pintype "passive"))
      (node (ref "U16") (pin "19") (pinfunction "GND_19") (pintype "passive"))
      (node (ref "U16") (pin "21") (pinfunction "GND_21") (pintype "passive"))
      (node (ref "U16") (pin "23") (pinfunction "GND_23") (pintype "passive"))
      (node (ref "U16") (pin "24") (pinfunction "GND_24") (pintype "passive"))
      (node (ref "U16") (pin "26") (pinfunction "GND_26") (pintype "passive"))
      (node (ref "U16") (pin "28") (pinfunction "GND_28") (pintype "passive"))
      (node (ref "U16") (pin "30") (pinfunction "GND_30") (pintype "passive"))
      (node (ref "U16") (pin "37") (pinfunction "GND_37") (pintype "passive"))
      (node (ref "U19") (pin "1") (pinfunction "Vdd_1") (pintype "passive"))
      (node (ref "U19") (pin "10") (pinfunction "G_10") (pintype "passive"))
      (node (ref "U19") (pin "11") (pinfunction "NC_11") (pintype "passive"))
      (node (ref "U19") (pin "12") (pinfunction "RF2_12") (pintype "passive"))
      (node (ref "U19") (pin "13") (pinfunction "NC_13") (pintype "passive"))
      (node (ref "U19") (pin "14") (pinfunction "NC_14") (pintype "passive"))
      (node (ref "U19") (pin "17") (pinfunction "NC_17") (pintype "passive"))
      (node (ref "U19") (pin "18") (pinfunction "NC_18") (pintype "passive"))
      (node (ref "U19") (pin "19") (pinfunction "NC_19") (pintype "passive"))
      (node (ref "U19") (pin "2") (pinfunction "Vctl_2") (pintype "passive"))
      (node (ref "U19") (pin "20") (pinfunction "NC_20") (pintype "passive"))
      (node (ref "U19") (pin "21") (pinfunction "G_21") (pintype "passive"))
      (node (ref "U19") (pin "23") (pinfunction "G_23") (pintype "passive"))
      (node (ref "U19") (pin "24") (pinfunction "NC_24") (pintype "passive"))
      (node (ref "U19") (pin "25") (pinfunction "G_25") (pintype "passive"))
      (node (ref "U19") (pin "3") (pinfunction "G_3") (pintype "passive"))
      (node (ref "U19") (pin "5") (pinfunction "G_5") (pintype "passive"))
      (node (ref "U19") (pin "6") (pinfunction "NC_6") (pintype "passive"))
      (node (ref "U19") (pin "7") (pinfunction "NC_7") (pintype "passive"))
      (node (ref "U19") (pin "8") (pinfunction "G_8") (pintype "passive"))
      (node (ref "U2") (pin "2") (pinfunction "GND_2") (pintype "passive"))
      (node (ref "U2") (pin "4") (pinfunction "4_4") (pintype "passive"))
      (node (ref "U21") (pin "1") (pinfunction "Vdd_1") (pintype "passive"))
      (node (ref "U21") (pin "10") (pinfunction "G_10") (pintype "passive"))
      (node (ref "U21") (pin "11") (pinfunction "NC_11") (pintype "passive"))
      (node (ref "U21") (pin "12") (pinfunction "RF2_12") (pintype "passive"))
      (node (ref "U21") (pin "13") (pinfunction "NC_13") (pintype "passive"))
      (node (ref "U21") (pin "14") (pinfunction "NC_14") (pintype "passive"))
      (node (ref "U21") (pin "17") (pinfunction "NC_17") (pintype "passive"))
      (node (ref "U21") (pin "18") (pinfunction "NC_18") (pintype "passive"))
      (node (ref "U21") (pin "19") (pinfunction "NC_19") (pintype "passive"))
      (node (ref "U21") (pin "2") (pinfunction "Vctl_2") (pintype "passive"))
      (node (ref "U21") (pin "20") (pinfunction "NC_20") (pintype "passive"))
      (node (ref "U21") (pin "21") (pinfunction "G_21") (pintype "passive"))
      (node (ref "U21") (pin "23") (pinfunction "G_23") (pintype "passive"))
      (node (ref "U21") (pin "24") (pinfunction "NC_24") (pintype "passive"))
      (node (ref "U21") (pin "25") (pinfunction "G_25") (pintype "passive"))
      (node (ref "U21") (pin "3") (pinfunction "G_3") (pintype "passive"))
      (node (ref "U21") (pin "5") (pinfunction "G_5") (pintype "passive"))
      (node (ref "U21") (pin "6") (pinfunction "NC_6") (pintype "passive"))
      (node (ref "U21") (pin "7") (pinfunction "NC_7") (pintype "passive"))
      (node (ref "U21") (pin "8") (pinfunction "G_8") (pintype "passive"))
      (node (ref "U24") (pin "1") (pinfunction "Vdd_1") (pintype "passive"))
      (node (ref "U24") (pin "10") (pinfunction "G_10") (pintype "passive"))
      (node (ref "U24") (pin "11") (pinfunction "NC_11") (pintype "passive"))
      (node (ref "U24") (pin "12") (pinfunction "RF2_12") (pintype "passive"))
      (node (ref "U24") (pin "13") (pinfunction "NC_13") (pintype "passive"))
      (node (ref "U24") (pin "14") (pinfunction "NC_14") (pintype "passive"))
      (node (ref "U24") (pin "17") (pinfunction "NC_17") (pintype "passive"))
      (node (ref "U24") (pin "18") (pinfunction "NC_18") (pintype "passive"))
      (node (ref "U24") (pin "19") (pinfunction "NC_19") (pintype "passive"))
      (node (ref "U24") (pin "2") (pinfunction "Vctl_2") (pintype "passive"))
      (node (ref "U24") (pin "20") (pinfunction "NC_20") (pintype "passive"))
      (node (ref "U24") (pin "21") (pinfunction "G_21") (pintype "passive"))
      (node (ref "U24") (pin "23") (pinfunction "G_23") (pintype "passive"))
      (node (ref "U24") (pin "24") (pinfunction "NC_24") (pintype "passive"))
      (node (ref "U24") (pin "25") (pinfunction "G_25") (pintype "passive"))
      (node (ref "U24") (pin "3") (pinfunction "G_3") (pintype "passive"))
      (node (ref "U24") (pin "5") (pinfunction "G_5") (pintype "passive"))
      (node (ref "U24") (pin "6") (pinfunction "NC_6") (pintype "passive"))
      (node (ref "U24") (pin "7") (pinfunction "NC_7") (pintype "passive"))
      (node (ref "U24") (pin "8") (pinfunction "G_8") (pintype "passive"))
      (node (ref "U5") (pin "1") (pinfunction "Vdd_1") (pintype "passive"))
      (node (ref "U5") (pin "10") (pinfunction "G_10") (pintype "passive"))
      (node (ref "U5") (pin "11") (pinfunction "NC_11") (pintype "passive"))
      (node (ref "U5") (pin "12") (pinfunction "RF2_12") (pintype "passive"))
      (node (ref "U5") (pin "13") (pinfunction "NC_13") (pintype "passive"))
      (node (ref "U5") (pin "14") (pinfunction "NC_14") (pintype "passive"))
      (node (ref "U5") (pin "17") (pinfunction "NC_17") (pintype "passive"))
      (node (ref "U5") (pin "18") (pinfunction "NC_18") (pintype "passive"))
      (node (ref "U5") (pin "19") (pinfunction "NC_19") (pintype "passive"))
      (node (ref "U5") (pin "2") (pinfunction "Vctl_2") (pintype "passive"))
      (node (ref "U5") (pin "20") (pinfunction "NC_20") (pintype "passive"))
      (node (ref "U5") (pin "21") (pinfunction "G_21") (pintype "passive"))
      (node (ref "U5") (pin "23") (pinfunction "G_23") (pintype "passive"))
      (node (ref "U5") (pin "24") (pinfunction "NC_24") (pintype "passive"))
      (node (ref "U5") (pin "25") (pinfunction "G_25") (pintype "passive"))
      (node (ref "U5") (pin "3") (pinfunction "G_3") (pintype "passive"))
      (node (ref "U5") (pin "5") (pinfunction "G_5") (pintype "passive"))
      (node (ref "U5") (pin "6") (pinfunction "NC_6") (pintype "passive"))
      (node (ref "U5") (pin "7") (pinfunction "NC_7") (pintype "passive"))
      (node (ref "U5") (pin "8") (pinfunction "G_8") (pintype "passive"))
      (node (ref "U6") (pin "1") (pinfunction "Vdd_1") (pintype "passive"))
      (node (ref "U6") (pin "10") (pinfunction "G_10") (pintype "passive"))
      (node (ref "U6") (pin "11") (pinfunction "NC_11") (pintype "passive"))
      (node (ref "U6") (pin "12") (pinfunction "RF2_12") (pintype "passive"))
      (node (ref "U6") (pin "13") (pinfunction "NC_13") (pintype "passive"))
      (node (ref "U6") (pin "14") (pinfunction "NC_14") (pintype "passive"))
      (node (ref "U6") (pin "17") (pinfunction "NC_17") (pintype "passive"))
      (node (ref "U6") (pin "18") (pinfunction "NC_18") (pintype "passive"))
      (node (ref "U6") (pin "19") (pinfunction "NC_19") (pintype "passive"))
      (node (ref "U6") (pin "2") (pinfunction "Vctl_2") (pintype "passive"))
      (node (ref "U6") (pin "20") (pinfunction "NC_20") (pintype "passive"))
      (node (ref "U6") (pin "21") (pinfunction "G_21") (pintype "passive"))
      (node (ref "U6") (pin "23") (pinfunction "G_23") (pintype "passive"))
      (node (ref "U6") (pin "24") (pinfunction "NC_24") (pintype "passive"))
      (node (ref "U6") (pin "25") (pinfunction "G_25") (pintype "passive"))
      (node (ref "U6") (pin "3") (pinfunction "G_3") (pintype "passive"))
      (node (ref "U6") (pin "5") (pinfunction "G_5") (pintype "passive"))
      (node (ref "U6") (pin "6") (pinfunction "NC_6") (pintype "passive"))
      (node (ref "U6") (pin "7") (pinfunction "NC_7") (pintype "passive"))
      (node (ref "U6") (pin "8") (pinfunction "G_8") (pintype "passive"))
    )
    (net (code "26") (name "Net-(AT1-IN{slash}OUT-Pad1)") (class "Default")
      (node (ref "AT1") (pin "1") (pinfunction "IN/OUT_1") (pintype "passive"))
      (node (ref "FL7") (pin "1") (pinfunction "1_1") (pintype "passive"))
      (node (ref "L58") (pin "2") (pinfunction "2_2") (pintype "passive"))
    )
    (net (code "27") (name "Net-(AT1-IN{slash}OUT-Pad3)") (class "Default")
      (node (ref "AT1") (pin "3") (pinfunction "IN/OUT_3") (pintype "passive"))
      (node (ref "FL8") (pin "2") (pinfunction "2_2") (pintype "passive"))
      (node (ref "L53") (pin "2") (pinfunction "2_2") (pintype "passive"))
    )
    (net (code "28") (name "Net-(AT3-IN{slash}OUT-Pad1)") (class "Default")
      (node (ref "AT3") (pin "1") (pinfunction "IN/OUT_1") (pintype "passive"))
      (node (ref "FL16") (pin "1") (pinfunction "1_1") (pintype "passive"))
      (node (ref "L61") (pin "2") (pinfunction "2_2") (pintype "passive"))
    )
    (net (code "29") (name "Net-(AT3-IN{slash}OUT-Pad3)") (class "Default")
      (node (ref "AT3") (pin "3") (pinfunction "IN/OUT_3") (pintype "passive"))
      (node (ref "FL17") (pin "2") (pinfunction "2_2") (pintype "passive"))
      (node (ref "L63") (pin "2") (pinfunction "2_2") (pintype "passive"))
    )
    (net (code "30") (name "Net-(AT6-IN{slash}OUT-Pad1)") (class "Default")
      (node (ref "AT6") (pin "1") (pinfunction "IN/OUT_1") (pintype "passive"))
      (node (ref "FL24") (pin "1") (pinfunction "1_1") (pintype "passive"))
      (node (ref "L70") (pin "2") (pinfunction "2_2") (pintype "passive"))
    )
    (net (code "31") (name "Net-(AT6-IN{slash}OUT-Pad3)") (class "Default")
      (node (ref "AT6") (pin "3") (pinfunction "IN/OUT_3") (pintype "passive"))
      (node (ref "FL25") (pin "2") (pinfunction "2_2") (pintype "passive"))
      (node (ref "L74") (pin "2") (pinfunction "2_2") (pintype "passive"))
    )
    (net (code "32") (name "Net-(AT10-IN{slash}OUT-Pad1)") (class "Default")
      (node (ref "AT10") (pin "1") (pinfunction "IN/OUT_1") (pintype "passive"))
      (node (ref "FL30") (pin "1") (pinfunction "1_1") (pintype "passive"))
      (node (ref "L80") (pin "2") (pinfunction "2_2") (pintype "passive"))
    )
    (net (code "33") (name "Net-(AT10-IN{slash}OUT-Pad3)") (class "Default")
      (node (ref "AT10") (pin "3") (pinfunction "IN/OUT_3") (pintype "passive"))
      (node (ref "FL31") (pin "2") (pinfunction "2_2") (pintype "passive"))
      (node (ref "L82") (pin "2") (pinfunction "2_2") (pintype "passive"))
    )
    (net (code "34") (name "Net-(AT12-IN{slash}OUT-Pad1)") (class "Default")
      (node (ref "AT12") (pin "1") (pinfunction "IN/OUT_1") (pintype "passive"))
      (node (ref "FL35") (pin "1") (pinfunction "1_1") (pintype "passive"))
      (node (ref "L86") (pin "2") (pinfunction "2_2") (pintype "passive"))
    )
    (net (code "35") (name "Net-(AT12-IN{slash}OUT-Pad3)") (class "Default")
      (node (ref "AT12") (pin "3") (pinfunction "IN/OUT_3") (pintype "passive"))
      (node (ref "FL36") (pin "2") (pinfunction "2_2") (pintype "passive"))
      (node (ref "L92") (pin "2") (pinfunction "2_2") (pintype "passive"))
    )
    (net (code "36") (name "Net-(AT14-IN{slash}OUT-Pad1)") (class "Default")
      (node (ref "AT14") (pin "1") (pinfunction "IN/OUT_1") (pintype "passive"))
      (node (ref "FL41") (pin "1") (pinfunction "1_1") (pintype "passive"))
      (node (ref "L94") (pin "2") (pinfunction "2_2") (pintype "passive"))
    )
    (net (code "37") (name "Net-(AT14-IN{slash}OUT-Pad3)") (class "Default")
      (node (ref "AT14") (pin "3") (pinfunction "IN/OUT_3") (pintype "passive"))
      (node (ref "FL40") (pin "2") (pinfunction "2_2") (pintype "passive"))
      (node (ref "L97") (pin "2") (pinfunction "2_2") (pintype "passive"))
    )
    (net (code "38") (name "Net-(AT44-IN{slash}OUT-Pad3)") (class "Default")
      (node (ref "AT44") (pin "3") (pinfunction "IN/OUT_3") (pintype "passive"))
      (node (ref "L3") (pin "2") (pinfunction "2_2") (pintype "passive"))
    )
    (net (code "39") (name "Net-(AT46-IN{slash}OUT-Pad3)") (class "Default")
      (node (ref "AT46") (pin "3") (pinfunction "IN/OUT_3") (pintype "passive"))
      (node (ref "C10") (pin "1") (pintype "passive"))
    )
    (net (code "40") (name "Net-(AT47-IN{slash}OUT-Pad1)") (class "Default")
      (node (ref "AT47") (pin "1") (pinfunction "IN/OUT_1") (pintype "passive"))
      (node (ref "FL8") (pin "1") (pinfunction "1_1") (pintype "passive"))
      (node (ref "L52") (pin "2") (pinfunction "2_2") (pintype "passive"))
    )
    (net (code "41") (name "Net-(AT47-IN{slash}OUT-Pad3)") (class "Default")
      (node (ref "AT47") (pin "3") (pinfunction "IN/OUT_3") (pintype "passive"))
      (node (ref "C777") (pin "1") (pintype "passive"))
    )
    (net (code "42") (name "Net-(AT48-IN{slash}OUT-Pad1)") (class "Default")
      (node (ref "AT48") (pin "1") (pinfunction "IN/OUT_1") (pintype "passive"))
      (node (ref "FL17") (pin "1") (pinfunction "1_1") (pintype "passive"))
      (node (ref "L62") (pin "2") (pinfunction "2_2") (pintype "passive"))
    )
    (net (code "43") (name "Net-(AT48-IN{slash}OUT-Pad3)") (class "Default")
      (node (ref "AT48") (pin "3") (pinfunction "IN/OUT_3") (pintype "passive"))
      (node (ref "C784") (pin "1") (pintype "passive"))
    )
    (net (code "44") (name "Net-(AT49-IN{slash}OUT-Pad1)") (class "Default")
      (node (ref "AT49") (pin "1") (pinfunction "IN/OUT_1") (pintype "passive"))
      (node (ref "FL25") (pin "1") (pinfunction "1_1") (pintype "passive"))
      (node (ref "L72") (pin "2") (pinfunction "2_2") (pintype "passive"))
    )
    (net (code "45") (name "Net-(AT49-IN{slash}OUT-Pad3)") (class "Default")
      (node (ref "AT49") (pin "3") (pinfunction "IN/OUT_3") (pintype "passive"))
      (node (ref "C790") (pin "1") (pintype "passive"))
    )
    (net (code "46") (name "Net-(AT50-IN{slash}OUT-Pad1)") (class "Default")
      (node (ref "AT50") (pin "1") (pinfunction "IN/OUT_1") (pintype "passive"))
      (node (ref "FL31") (pin "1") (pinfunction "1_1") (pintype "passive"))
      (node (ref "L81") (pin "2") (pinfunction "2_2") (pintype "passive"))
    )
    (net (code "47") (name "Net-(AT50-IN{slash}OUT-Pad3)") (class "Default")
      (node (ref "AT50") (pin "3") (pinfunction "IN/OUT_3") (pintype "passive"))
      (node (ref "C796") (pin "1") (pintype "passive"))
    )
    (net (code "48") (name "Net-(AT51-IN{slash}OUT-Pad1)") (class "Default")
      (node (ref "AT51") (pin "1") (pinfunction "IN/OUT_1") (pintype "passive"))
      (node (ref "FL36") (pin "1") (pinfunction "1_1") (pintype "passive"))
      (node (ref "L87") (pin "2") (pinfunction "2_2") (pintype "passive"))
    )
    (net (code "49") (name "Net-(AT51-IN{slash}OUT-Pad3)") (class "Default")
      (node (ref "AT51") (pin "3") (pinfunction "IN/OUT_3") (pintype "passive"))
      (node (ref "C802") (pin "1") (pintype "passive"))
    )
    (net (code "50") (name "Net-(AT52-IN{slash}OUT-Pad1)") (class "Default")
      (node (ref "AT52") (pin "1") (pinfunction "IN/OUT_1") (pintype "passive"))
      (node (ref "FL40") (pin "1") (pinfunction "1_1") (pintype "passive"))
      (node (ref "L95") (pin "2") (pinfunction "2_2") (pintype "passive"))
    )
    (net (code "51") (name "Net-(AT52-IN{slash}OUT-Pad3)") (class "Default")
      (node (ref "AT52") (pin "3") (pinfunction "IN/OUT_3") (pintype "passive"))
      (node (ref "C808") (pin "1") (pintype "passive"))
    )
    (net (code "52") (name "Net-(AT56-IN{slash}OUT-Pad3)") (class "Default")
      (node (ref "AT56") (pin "3") (pinfunction "IN/OUT_3") (pintype "passive"))
      (node (ref "C360") (pin "2") (pintype "passive"))
    )
    (net (code "53") (name "Net-(AT72-IN{slash}OUT-Pad1)") (class "Default")
      (node (ref "AT72") (pin "1") (pinfunction "IN/OUT_1") (pintype "passive"))
      (node (ref "C773") (pin "2") (pintype "passive"))
    )
    (net (code "54") (name "Net-(AT72-IN{slash}OUT-Pad3)") (class "Default")
      (node (ref "AT72") (pin "3") (pinfunction "IN/OUT_3") (pintype "passive"))
      (node (ref "C731") (pin "1") (pintype "passive"))
    )
    (net (code "55") (name "Net-(C5-Pad1)") (class "Default")
      (node (ref "C5") (pin "1") (pintype "passive"))
      (node (ref "C789") (pin "2") (pintype "passive"))
      (node (ref "L99") (pin "2") (pinfunction "2_2") (pintype "passive"))
      (node (ref "U133") (pin "3") (pinfunction "3_3") (pintype "passive"))
    )
    (net (code "56") (name "Net-(C6-Pad1)") (class "Default")
      (node (ref "C6") (pin "1") (pintype "passive"))
      (node (ref "C8") (pin "2") (pintype "passive"))
      (node (ref "C9") (pin "2") (pintype "passive"))
      (node (ref "L7") (pin "2") (pinfunction "2_2") (pintype "passive"))
    )
    (net (code "57") (name "Net-(C6-Pad2)") (class "Default")
      (node (ref "C6") (pin "2") (pintype "passive"))
      (node (ref "L4") (pin "2") (pinfunction "2_2") (pintype "passive"))
    )
    (net (code "58") (name "Net-(C7-Pad2)") (class "Default")
      (node (ref "C7") (pin "2") (pintype "passive"))
      (node (ref "L2") (pin "2") (pinfunction "2_2") (pintype "passive"))
    )
    (net (code "59") (name "Net-(C8-Pad1)") (class "Default")
      (node (ref "C8") (pin "1") (pintype "passive"))
      (node (ref "L3") (pin "1") (pinfunction "1_1") (pintype "passive"))
    )
    (net (code "60") (name "Net-(C10-Pad2)") (class "Default")
      (node (ref "C10") (pin "2") (pintype "passive"))
      (node (ref "U133") (pin "1") (pinfunction "1_1") (pintype "passive"))
    )
    (net (code "61") (name "Net-(C11-Pad2)") (class "Default")
      (node (ref "C11") (pin "2") (pintype "passive"))
      (node (ref "C7") (pin "1") (pintype "passive"))
      (node (ref "L4") (pin "1") (pinfunction "1_1") (pintype "passive"))
      (node (ref "L6") (pin "2") (pinfunction "2_2") (pintype "passive"))
    )
    (net (code "62") (name "Net-(C13-Pad1)") (class "Default")
      (node (ref "C13") (pin "1") (pintype "passive"))
      (node (ref "L205") (pin "2") (pinfunction "2_2") (pintype "passive"))
      (node (ref "L99") (pin "1") (pinfunction "1_1") (pintype "passive"))
    )
    (net (code "63") (name "Net-(C14-Pad1)") (class "Default")
      (node (ref "C14") (pin "1") (pintype "passive"))
      (node (ref "L100") (pin "2") (pinfunction "2_2") (pintype "passive"))
      (node (ref "L117") (pin "1") (pinfunction "1_1") (pintype "passive"))
    )
    (net (code "64") (name "Net-(C360-Pad1)") (class "Default")
      (node (ref "C360") (pin "1") (pintype "passive"))
      (node (ref "C820") (pin "2") (pintype "passive"))
      (node (ref "C821") (pin "1") (pintype "passive"))
    )
    (net (code "65") (name "Net-(C387-Pad1)") (class "Default")
      (node (ref "C387") (pin "1") (pintype "passive"))
      (node (ref "L138") (pin "2") (pinfunction "2_2") (pintype "passive"))
      (node (ref "U14") (pin "33") (pinfunction "VCC_33") (pintype "passive"))
    )
    (net (code "66") (name "Net-(C389-Pad1)") (class "Default")
      (node (ref "C389") (pin "1") (pintype "passive"))
      (node (ref "L167") (pin "2") (pinfunction "2_2") (pintype "passive"))
      (node (ref "U14") (pin "32") (pinfunction "VEE_32") (pintype "passive"))
    )
    (net (code "67") (name "Net-(C731-Pad2)") (class "Default")
      (node (ref "C731") (pin "2") (pintype "passive"))
      (node (ref "U11") (pin "1") (pinfunction "1_1") (pintype "passive"))
    )
    (net (code "68") (name "Net-(C733-Pad1)") (class "Default")
      (node (ref "C733") (pin "1") (pintype "passive"))
      (node (ref "U5") (pin "4") (pinfunction "NC_4") (pintype "passive"))
    )
    (net (code "69") (name "Net-(C733-Pad2)") (class "Default")
      (node (ref "C733") (pin "2") (pintype "passive"))
      (node (ref "FL7") (pin "2") (pinfunction "2_2") (pintype "passive"))
      (node (ref "L46") (pin "2") (pinfunction "2_2") (pintype "passive"))
    )
    (net (code "70") (name "Net-(C736-Pad1)") (class "Default")
      (node (ref "C736") (pin "1") (pintype "passive"))
      (node (ref "U6") (pin "4") (pinfunction "NC_4") (pintype "passive"))
    )
    (net (code "71") (name "Net-(C736-Pad2)") (class "Default")
      (node (ref "C736") (pin "2") (pintype "passive"))
      (node (ref "FL16") (pin "2") (pinfunction "2_2") (pintype "passive"))
      (node (ref "L60") (pin "2") (pinfunction "2_2") (pintype "passive"))
    )
    (net (code "72") (name "Net-(C739-Pad1)") (class "Default")
      (node (ref "C739") (pin "1") (pintype "passive"))
      (node (ref "U12") (pin "4") (pinfunction "NC_4") (pintype "passive"))
    )
    (net (code "73") (name "Net-(C739-Pad2)") (class "Default")
      (node (ref "C739") (pin "2") (pintype "passive"))
      (node (ref "FL24") (pin "2") (pinfunction "2_2") (pintype "passive"))
      (node (ref "L64") (pin "2") (pinfunction "2_2") (pintype "passive"))
    )
    (net (code "74") (name "Net-(C745-Pad1)") (class "Default")
      (node (ref "C745") (pin "1") (pintype "passive"))
      (node (ref "U19") (pin "4") (pinfunction "NC_4") (pintype "passive"))
    )
    (net (code "75") (name "Net-(C745-Pad2)") (class "Default")
      (node (ref "C745") (pin "2") (pintype "passive"))
      (node (ref "FL30") (pin "2") (pinfunction "2_2") (pintype "passive"))
      (node (ref "L75") (pin "2") (pinfunction "2_2") (pintype "passive"))
    )
    (net (code "76") (name "Net-(C749-Pad1)") (class "Default")
      (node (ref "C749") (pin "1") (pintype "passive"))
      (node (ref "U21") (pin "4") (pinfunction "NC_4") (pintype "passive"))
    )
    (net (code "77") (name "Net-(C749-Pad2)") (class "Default")
      (node (ref "C749") (pin "2") (pintype "passive"))
      (node (ref "FL35") (pin "2") (pinfunction "2_2") (pintype "passive"))
      (node (ref "L83") (pin "2") (pinfunction "2_2") (pintype "passive"))
    )
    (net (code "78") (name "Net-(C752-Pad1)") (class "Default")
      (node (ref "C752") (pin "1") (pintype "passive"))
      (node (ref "U24") (pin "4") (pinfunction "NC_4") (pintype "passive"))
    )
    (net (code "79") (name "Net-(C752-Pad2)") (class "Default")
      (node (ref "C752") (pin "2") (pintype "passive"))
      (node (ref "FL41") (pin "2") (pinfunction "2_2") (pintype "passive"))
      (node (ref "L93") (pin "2") (pinfunction "2_2") (pintype "passive"))
    )
    (net (code "80") (name "Net-(C773-Pad1)") (class "Default")
      (node (ref "C773") (pin "1") (pintype "passive"))
      (node (ref "L117") (pin "2") (pinfunction "2_2") (pintype "passive"))
      (node (ref "U2") (pin "3") (pinfunction "3_3") (pintype "passive"))
    )
    (net (code "81") (name "Net-(C774-Pad1)") (class "Default")
      (node (ref "C774") (pin "1") (pintype "passive"))
      (node (ref "FL146") (pin "3") (pinfunction "GND_3") (pintype "passive"))
    )
    (net (code "82") (name "Net-(C774-Pad2)") (class "Default")
      (node (ref "C774") (pin "2") (pintype "passive"))
      (node (ref "U2") (pin "1") (pinfunction "1_1") (pintype "passive"))
    )
    (net (code "83") (name "Net-(C775-Pad1)") (class "Default")
      (node (ref "C775") (pin "1") (pintype "passive"))
      (node (ref "U109") (pin "4") (pinfunction "NC_4") (pintype "passive"))
    )
    (net (code "84") (name "Net-(C781-Pad1)") (class "Default")
      (node (ref "C781") (pin "1") (pintype "passive"))
      (node (ref "U113") (pin "4") (pinfunction "NC_4") (pintype "passive"))
    )
    (net (code "85") (name "Net-(C788-Pad1)") (class "Default")
      (node (ref "C788") (pin "1") (pintype "passive"))
      (node (ref "U126") (pin "4") (pinfunction "NC_4") (pintype "passive"))
    )
    (net (code "86") (name "Net-(C794-Pad1)") (class "Default")
      (node (ref "C794") (pin "1") (pintype "passive"))
      (node (ref "U134") (pin "4") (pinfunction "NC_4") (pintype "passive"))
    )
    (net (code "87") (name "Net-(C800-Pad1)") (class "Default")
      (node (ref "C800") (pin "1") (pintype "passive"))
      (node (ref "U135") (pin "4") (pinfunction "NC_4") (pintype "passive"))
    )
    (net (code "88") (name "Net-(C806-Pad1)") (class "Default")
      (node (ref "C806") (pin "1") (pintype "passive"))
      (node (ref "U136") (pin "4") (pinfunction "NC_4") (pintype "passive"))
    )
    (net (code "89") (name "Net-(C817-Pad1)") (class "Default")
      (node (ref "C817") (pin "1") (pintype "passive"))
      (node (ref "L101") (pin "2") (pinfunction "2_2") (pintype "passive"))
      (node (ref "U11") (pin "3") (pinfunction "3_3") (pintype "passive"))
    )
    (net (code "90") (name "Net-(C818-Pad1)") (class "Default")
      (node (ref "C818") (pin "1") (pintype "passive"))
      (node (ref "L101") (pin "1") (pinfunction "1_1") (pintype "passive"))
      (node (ref "L118") (pin "2") (pinfunction "2_2") (pintype "passive"))
    )
    (net (code "91") (name "Net-(C820-Pad1)") (class "Default")
      (node (ref "C820") (pin "1") (pintype "passive"))
      (node (ref "FL150") (pin "3") (pinfunction "GND_3") (pintype "passive"))
    )
    (net (code "92") (name "Net-(C920-Pad1)") (class "Default")
      (node (ref "C920") (pin "1") (pintype "passive"))
      (node (ref "L213") (pin "1") (pinfunction "1_1") (pintype "passive"))
      (node (ref "R178") (pin "1") (pintype "passive"))
    )
    (net (code "93") (name "Net-(C922-Pad1)") (class "Default")
      (node (ref "C922") (pin "1") (pintype "passive"))
      (node (ref "L214") (pin "1") (pinfunction "1_1") (pintype "passive"))
      (node (ref "R179") (pin "1") (pintype "passive"))
    )
    (net (code "94") (name "Net-(C931-Pad2)") (class "Default")
      (node (ref "C931") (pin "2") (pintype "passive"))
      (node (ref "L212") (pin "1") (pinfunction "1_1") (pintype "passive"))
      (node (ref "U16") (pin "32") (pinfunction "VEE_32") (pintype "passive"))
    )
    (net (code "95") (name "Net-(C932-Pad2)") (class "Default")
      (node (ref "C932") (pin "2") (pintype "passive"))
      (node (ref "L218") (pin "1") (pinfunction "1_1") (pintype "passive"))
      (node (ref "U16") (pin "33") (pinfunction "VCC_33") (pintype "passive"))
    )
    (net (code "96") (name "Net-(C934-Pad1)") (class "Default")
      (node (ref "C934") (pin "1") (pintype "passive"))
      (node (ref "L220") (pin "1") (pinfunction "1_1") (pintype "passive"))
      (node (ref "R181") (pin "1") (pintype "passive"))
    )
    (net (code "97") (name "Net-(C936-Pad1)") (class "Default")
      (node (ref "C936") (pin "1") (pintype "passive"))
      (node (ref "L221") (pin "1") (pinfunction "1_1") (pintype "passive"))
      (node (ref "R183") (pin "1") (pintype "passive"))
    )
    (net (code "98") (name "Net-(FL1-IN)") (class "Default")
      (node (ref "C4") (pin "2") (pintype "passive"))
      (node (ref "FL1") (pin "1") (pinfunction "IN_1") (pintype "passive"))
      (node (ref "FL2") (pin "3") (pinfunction "OUT_3") (pintype "passive"))
    )
    (net (code "99") (name "Net-(FL1-OUT)") (class "Default")
      (node (ref "C187") (pin "2") (pintype "passive"))
      (node (ref "FL1") (pin "3") (pinfunction "OUT_3") (pintype "passive"))
      (node (ref "R599") (pin "1") (pintype "passive"))
    )
    (net (code "100") (name "Net-(FL2-IN)") (class "Default")
      (node (ref "C717") (pin "2") (pintype "passive"))
      (node (ref "FL2") (pin "1") (pinfunction "IN_1") (pintype "passive"))
      (node (ref "FL3") (pin "3") (pinfunction "OUT_3") (pintype "passive"))
    )
    (net (code "101") (name "Net-(FL3-IN)") (class "Default")
      (node (ref "C1") (pin "1") (pintype "passive"))
      (node (ref "FL3") (pin "1") (pinfunction "IN_1") (pintype "passive"))
      (node (ref "L205") (pin "1") (pinfunction "1_1") (pintype "passive"))
    )
    (net (code "102") (name "Net-(FL4-IN)") (class "Default")
      (node (ref "AT45") (pin "1") (pinfunction "IN/OUT_1") (pintype "passive"))
      (node (ref "FL4") (pin "1") (pinfunction "IN_1") (pintype "passive"))
    )
    (net (code "103") (name "Net-(FL4-OUT)") (class "Default")
      (node (ref "AT43") (pin "1") (pinfunction "IN/OUT_1") (pintype "passive"))
      (node (ref "FL4") (pin "3") (pinfunction "OUT_3") (pintype "passive"))
    )
    (net (code "104") (name "Net-(FL93-IN)") (class "Default")
      (node (ref "AT45") (pin "3") (pinfunction "IN/OUT_3") (pintype "passive"))
      (node (ref "FL93") (pin "1") (pinfunction "IN_1") (pintype "passive"))
    )
    (net (code "105") (name "Net-(FL93-OUT)") (class "Default")
      (node (ref "AT46") (pin "1") (pinfunction "IN/OUT_1") (pintype "passive"))
      (node (ref "FL93") (pin "3") (pinfunction "OUT_3") (pintype "passive"))
    )
    (net (code "106") (name "Net-(FL143-IN)") (class "Default")
      (node (ref "C766") (pin "2") (pintype "passive"))
      (node (ref "FL143") (pin "1") (pinfunction "IN_1") (pintype "passive"))
      (node (ref "FL144") (pin "3") (pinfunction "OUT_3") (pintype "passive"))
    )
    (net (code "107") (name "Net-(FL143-OUT)") (class "Default")
      (node (ref "C767") (pin "1") (pintype "passive"))
      (node (ref "FL143") (pin "3") (pinfunction "OUT_3") (pintype "passive"))
      (node (ref "R4") (pin "2") (pintype "passive"))
    )
    (net (code "108") (name "Net-(FL144-IN)") (class "Default")
      (node (ref "C769") (pin "2") (pintype "passive"))
      (node (ref "FL144") (pin "1") (pinfunction "IN_1") (pintype "passive"))
      (node (ref "FL145") (pin "3") (pinfunction "OUT_3") (pintype "passive"))
    )
    (net (code "109") (name "Net-(FL145-IN)") (class "Default")
      (node (ref "C815") (pin "2") (pintype "passive"))
      (node (ref "FL145") (pin "1") (pinfunction "IN_1") (pintype "passive"))
      (node (ref "L100") (pin "1") (pinfunction "1_1") (pintype "passive"))
    )
    (net (code "110") (name "Net-(FL146-IN)") (class "Default")
      (node (ref "C772") (pin "2") (pintype "passive"))
      (node (ref "FL146") (pin "1") (pinfunction "IN_1") (pintype "passive"))
    )
    (net (code "111") (name "Net-(FL147-IN)") (class "Default")
      (node (ref "C813") (pin "2") (pintype "passive"))
      (node (ref "FL147") (pin "1") (pinfunction "IN_1") (pintype "passive"))
      (node (ref "FL148") (pin "3") (pinfunction "OUT_3") (pintype "passive"))
    )
    (net (code "112") (name "Net-(FL147-OUT)") (class "Default")
      (node (ref "C812") (pin "1") (pintype "passive"))
      (node (ref "FL147") (pin "3") (pinfunction "OUT_3") (pintype "passive"))
      (node (ref "R171") (pin "2") (pintype "passive"))
    )
    (net (code "113") (name "Net-(FL148-IN)") (class "Default")
      (node (ref "C814") (pin "2") (pintype "passive"))
      (node (ref "FL148") (pin "1") (pinfunction "IN_1") (pintype "passive"))
      (node (ref "FL149") (pin "3") (pinfunction "OUT_3") (pintype "passive"))
    )
    (net (code "114") (name "Net-(FL149-IN)") (class "Default")
      (node (ref "C15") (pin "2") (pintype "passive"))
      (node (ref "FL149") (pin "1") (pinfunction "IN_1") (pintype "passive"))
      (node (ref "L118") (pin "1") (pinfunction "1_1") (pintype "passive"))
    )
    (net (code "115") (name "Net-(FL150-IN)") (class "Default")
      (node (ref "C817") (pin "2") (pintype "passive"))
      (node (ref "FL150") (pin "1") (pinfunction "IN_1") (pintype "passive"))
    )
    (net (code "116") (name "Net-(J23-CNTR)") (class "Default")
      (node (ref "C789") (pin "1") (pintype "passive"))
      (node (ref "J23") (pin "1") (pinfunction "CNTR_1") (pintype "passive"))
    )
    (net (code "117") (name "Net-(J24-CNTR)") (class "Default")
      (node (ref "C821") (pin "2") (pintype "passive"))
      (node (ref "J24") (pin "1") (pinfunction "CNTR_1") (pintype "passive"))
    )
    (net (code "118") (name "Net-(L91-Pad1)") (class "Default")
      (node (ref "L91") (pin "1") (pinfunction "1_1") (pintype "passive"))
      (node (ref "R319") (pin "2") (pintype "passive"))
    )
    (net (code "119") (name "Net-(L96-Pad1)") (class "Default")
      (node (ref "L96") (pin "1") (pinfunction "1_1") (pintype "passive"))
      (node (ref "R322") (pin "2") (pintype "passive"))
    )
    (net (code "120") (name "Net-(L98-Pad1)") (class "Default")
      (node (ref "L98") (pin "1") (pinfunction "1_1") (pintype "passive"))
      (node (ref "R616") (pin "2") (pintype "passive"))
    )
    (net (code "121") (name "Net-(L102-Pad1)") (class "Default")
      (node (ref "L102") (pin "1") (pinfunction "1_1") (pintype "passive"))
      (node (ref "R617") (pin "2") (pintype "passive"))
    )
    (net (code "122") (name "Net-(L103-Pad1)") (class "Default")
      (node (ref "L103") (pin "1") (pinfunction "1_1") (pintype "passive"))
      (node (ref "R618") (pin "2") (pintype "passive"))
    )
    (net (code "123") (name "Net-(L104-Pad1)") (class "Default")
      (node (ref "L104") (pin "1") (pinfunction "1_1") (pintype "passive"))
      (node (ref "R619") (pin "2") (pintype "passive"))
    )
    (net (code "124") (name "Net-(L105-Pad1)") (class "Default")
      (node (ref "L105") (pin "1") (pinfunction "1_1") (pintype "passive"))
      (node (ref "R620") (pin "2") (pintype "passive"))
    )
    (net (code "125") (name "Net-(L106-Pad1)") (class "Default")
      (node (ref "L106") (pin "1") (pinfunction "1_1") (pintype "passive"))
      (node (ref "R621") (pin "2") (pintype "passive"))
    )
    (net (code "126") (name "Net-(L107-Pad1)") (class "Default")
      (node (ref "L107") (pin "1") (pinfunction "1_1") (pintype "passive"))
      (node (ref "R622") (pin "2") (pintype "passive"))
    )
    (net (code "127") (name "Net-(L108-Pad1)") (class "Default")
      (node (ref "L108") (pin "1") (pinfunction "1_1") (pintype "passive"))
      (node (ref "R623") (pin "2") (pintype "passive"))
    )
    (net (code "128") (name "Net-(L109-Pad1)") (class "Default")
      (node (ref "L109") (pin "1") (pinfunction "1_1") (pintype "passive"))
      (node (ref "R624") (pin "2") (pintype "passive"))
    )
    (net (code "129") (name "Net-(L110-Pad1)") (class "Default")
      (node (ref "L110") (pin "1") (pinfunction "1_1") (pintype "passive"))
      (node (ref "R625") (pin "2") (pintype "passive"))
    )
    (net (code "130") (name "Net-(L111-Pad1)") (class "Default")
      (node (ref "L111") (pin "1") (pinfunction "1_1") (pintype "passive"))
      (node (ref "R626") (pin "2") (pintype "passive"))
    )
    (net (code "131") (name "Net-(L112-Pad1)") (class "Default")
      (node (ref "L112") (pin "1") (pinfunction "1_1") (pintype "passive"))
      (node (ref "R627") (pin "2") (pintype "passive"))
    )
    (net (code "132") (name "Net-(L113-Pad1)") (class "Default")
      (node (ref "L113") (pin "1") (pinfunction "1_1") (pintype "passive"))
      (node (ref "R628") (pin "2") (pintype "passive"))
    )
    (net (code "133") (name "Net-(L114-Pad1)") (class "Default")
      (node (ref "L114") (pin "1") (pinfunction "1_1") (pintype "passive"))
      (node (ref "R629") (pin "2") (pintype "passive"))
    )
    (net (code "134") (name "Net-(L115-Pad1)") (class "Default")
      (node (ref "L115") (pin "1") (pinfunction "1_1") (pintype "passive"))
      (node (ref "R630") (pin "2") (pintype "passive"))
    )
    (net (code "135") (name "Net-(L116-Pad1)") (class "Default")
      (node (ref "L116") (pin "1") (pinfunction "1_1") (pintype "passive"))
      (node (ref "R631") (pin "2") (pintype "passive"))
    )
    (net (code "136") (name "Net-(L204-Pad1)") (class "Default")
      (node (ref "L204") (pin "1") (pinfunction "1_1") (pintype "passive"))
      (node (ref "R632") (pin "2") (pintype "passive"))
    )
    (net (code "137") (name "Net-(L207-Pad1)") (class "Default")
      (node (ref "L207") (pin "1") (pinfunction "1_1") (pintype "passive"))
      (node (ref "R633") (pin "2") (pintype "passive"))
    )
    (net (code "138") (name "Net-(L208-Pad1)") (class "Default")
      (node (ref "L208") (pin "1") (pinfunction "1_1") (pintype "passive"))
      (node (ref "R634") (pin "2") (pintype "passive"))
    )
    (net (code "139") (name "Net-(L209-Pad1)") (class "Default")
      (node (ref "L209") (pin "1") (pinfunction "1_1") (pintype "passive"))
      (node (ref "R635") (pin "2") (pintype "passive"))
    )
    (net (code "140") (name "Net-(L210-Pad1)") (class "Default")
      (node (ref "L210") (pin "1") (pinfunction "1_1") (pintype "passive"))
      (node (ref "R636") (pin "2") (pintype "passive"))
    )
    (net (code "141") (name "Net-(L211-Pad1)") (class "Default")
      (node (ref "L211") (pin "1") (pinfunction "1_1") (pintype "passive"))
      (node (ref "R637") (pin "2") (pintype "passive"))
    )
    (net (code "142") (name "Net-(L213-Pad2)") (class "Default")
      (node (ref "L213") (pin "2") (pinfunction "2_2") (pintype "passive"))
      (node (ref "R639") (pin "1") (pintype "passive"))
    )
    (net (code "143") (name "Net-(L214-Pad2)") (class "Default")
      (node (ref "L214") (pin "2") (pinfunction "2_2") (pintype "passive"))
      (node (ref "R640") (pin "1") (pintype "passive"))
    )
    (net (code "144") (name "Net-(L215-Pad2)") (class "Default")
      (node (ref "L215") (pin "2") (pinfunction "2_2") (pintype "passive"))
      (node (ref "R641") (pin "1") (pintype "passive"))
    )
    (net (code "145") (name "Net-(L216-Pad2)") (class "Default")
      (node (ref "L216") (pin "2") (pinfunction "2_2") (pintype "passive"))
      (node (ref "R642") (pin "1") (pintype "passive"))
    )
    (net (code "146") (name "Net-(L217-Pad2)") (class "Default")
      (node (ref "L217") (pin "2") (pinfunction "2_2") (pintype "passive"))
      (node (ref "R643") (pin "1") (pintype "passive"))
    )
    (net (code "147") (name "Net-(L219-Pad2)") (class "Default")
      (node (ref "L219") (pin "2") (pinfunction "2_2") (pintype "passive"))
      (node (ref "R638") (pin "1") (pintype "passive"))
    )
    (net (code "148") (name "Net-(L220-Pad2)") (class "Default")
      (node (ref "L220") (pin "2") (pinfunction "2_2") (pintype "passive"))
      (node (ref "R644") (pin "1") (pintype "passive"))
    )
    (net (code "149") (name "Net-(L221-Pad2)") (class "Default")
      (node (ref "L221") (pin "2") (pinfunction "2_2") (pintype "passive"))
      (node (ref "R645") (pin "1") (pintype "passive"))
    )
    (net (code "150") (name "Net-(L222-Pad2)") (class "Default")
      (node (ref "L222") (pin "2") (pinfunction "2_2") (pintype "passive"))
      (node (ref "R646") (pin "1") (pintype "passive"))
    )
    (net (code "151") (name "Net-(L223-Pad2)") (class "Default")
      (node (ref "L223") (pin "2") (pinfunction "2_2") (pintype "passive"))
      (node (ref "R647") (pin "1") (pintype "passive"))
    )
    (net (code "152") (name "Net-(L224-Pad2)") (class "Default")
      (node (ref "L224") (pin "2") (pinfunction "2_2") (pintype "passive"))
      (node (ref "R648") (pin "1") (pintype "passive"))
    )
    (net (code "153") (name "Net-(L225-Pad2)") (class "Default")
      (node (ref "L225") (pin "2") (pinfunction "2_2") (pintype "passive"))
      (node (ref "R649") (pin "1") (pintype "passive"))
    )
    (net (code "154") (name "Net-(R1-Pad1)") (class "Default")
      (node (ref "R1") (pin "1") (pintype "passive"))
      (node (ref "U5") (pin "22") (pinfunction "RF2_22") (pintype "passive"))
    )
    (net (code "155") (name "Net-(R3-Pad1)") (class "Default")
      (node (ref "R3") (pin "1") (pintype "passive"))
      (node (ref "U6") (pin "22") (pinfunction "RF2_22") (pintype "passive"))
    )
    (net (code "156") (name "Net-(R179-Pad2)") (class "Default")
      (node (ref "R179") (pin "2") (pintype "passive"))
      (node (ref "R180") (pin "1") (pintype "passive"))
    )
    (net (code "157") (name "Net-(R181-Pad2)") (class "Default")
      (node (ref "R181") (pin "2") (pintype "passive"))
      (node (ref "R182") (pin "1") (pintype "passive"))
    )
    (net (code "158") (name "Net-(R401-Pad1)") (class "Default")
      (node (ref "R401") (pin "1") (pintype "passive"))
      (node (ref "U12") (pin "22") (pinfunction "RF2_22") (pintype "passive"))
    )
    (net (code "159") (name "Net-(R596-Pad1)") (class "Default")
      (node (ref "R596") (pin "1") (pintype "passive"))
      (node (ref "U19") (pin "22") (pinfunction "RF2_22") (pintype "passive"))
    )
    (net (code "160") (name "Net-(R597-Pad1)") (class "Default")
      (node (ref "R597") (pin "1") (pintype "passive"))
      (node (ref "U21") (pin "22") (pinfunction "RF2_22") (pintype "passive"))
    )
    (net (code "161") (name "Net-(R598-Pad1)") (class "Default")
      (node (ref "R598") (pin "1") (pintype "passive"))
      (node (ref "U24") (pin "22") (pinfunction "RF2_22") (pintype "passive"))
    )
    (net (code "162") (name "Net-(R600-Pad1)") (class "Default")
      (node (ref "R600") (pin "1") (pintype "passive"))
      (node (ref "U109") (pin "22") (pinfunction "RF2_22") (pintype "passive"))
    )
    (net (code "163") (name "Net-(R601-Pad1)") (class "Default")
      (node (ref "R601") (pin "1") (pintype "passive"))
      (node (ref "U113") (pin "22") (pinfunction "RF2_22") (pintype "passive"))
    )
    (net (code "164") (name "Net-(R602-Pad1)") (class "Default")
      (node (ref "R602") (pin "1") (pintype "passive"))
      (node (ref "U126") (pin "22") (pinfunction "RF2_22") (pintype "passive"))
    )
    (net (code "165") (name "Net-(R603-Pad1)") (class "Default")
      (node (ref "R603") (pin "1") (pintype "passive"))
      (node (ref "U134") (pin "22") (pinfunction "RF2_22") (pintype "passive"))
    )
    (net (code "166") (name "Net-(R604-Pad1)") (class "Default")
      (node (ref "R604") (pin "1") (pintype "passive"))
      (node (ref "U135") (pin "22") (pinfunction "RF2_22") (pintype "passive"))
    )
    (net (code "167") (name "Net-(R605-Pad1)") (class "Default")
      (node (ref "R605") (pin "1") (pintype "passive"))
      (node (ref "U136") (pin "22") (pinfunction "RF2_22") (pintype "passive"))
    )
    (net (code "168") (name "Net-(U1-I)") (class "Default")
      (node (ref "AT44") (pin "1") (pinfunction "IN/OUT_1") (pintype "passive"))
      (node (ref "U1") (pin "2") (pinfunction "I_2") (pintype "passive"))
    )
    (net (code "169") (name "Net-(U1-R)") (class "Default")
      (node (ref "AT43") (pin "3") (pinfunction "IN/OUT_3") (pintype "passive"))
      (node (ref "U1") (pin "3") (pinfunction "R_3") (pintype "passive"))
    )
    (net (code "170") (name "Net-(U5-A)") (class "Default")
      (node (ref "C755") (pin "1") (pintype "passive"))
      (node (ref "L96") (pin "2") (pinfunction "2_2") (pintype "passive"))
      (node (ref "U5") (pin "16") (pinfunction "A_16") (pintype "passive"))
    )
    (net (code "171") (name "Net-(U5-B)") (class "Default")
      (node (ref "C894") (pin "1") (pintype "passive"))
      (node (ref "L91") (pin "2") (pinfunction "2_2") (pintype "passive"))
      (node (ref "U5") (pin "15") (pinfunction "B_15") (pintype "passive"))
    )
    (net (code "172") (name "Net-(U5-RF1)") (class "Default")
      (node (ref "C732") (pin "2") (pintype "passive"))
      (node (ref "U5") (pin "9") (pinfunction "RF1_9") (pintype "passive"))
    )
    (net (code "173") (name "Net-(U6-A)") (class "Default")
      (node (ref "C757") (pin "1") (pintype "passive"))
      (node (ref "L104") (pin "2") (pinfunction "2_2") (pintype "passive"))
      (node (ref "U6") (pin "16") (pinfunction "A_16") (pintype "passive"))
    )
    (net (code "174") (name "Net-(U6-B)") (class "Default")
      (node (ref "C756") (pin "1") (pintype "passive"))
      (node (ref "L103") (pin "2") (pinfunction "2_2") (pintype "passive"))
      (node (ref "U6") (pin "15") (pinfunction "B_15") (pintype "passive"))
    )
    (net (code "175") (name "Net-(U6-RF1)") (class "Default")
      (node (ref "C783") (pin "2") (pintype "passive"))
      (node (ref "U6") (pin "9") (pinfunction "RF1_9") (pintype "passive"))
    )
    (net (code "176") (name "Net-(U12-A)") (class "Default")
      (node (ref "C785") (pin "1") (pintype "passive"))
      (node (ref "L108") (pin "2") (pinfunction "2_2") (pintype "passive"))
      (node (ref "U12") (pin "16") (pinfunction "A_16") (pintype "passive"))
    )
    (net (code "177") (name "Net-(U12-B)") (class "Default")
      (node (ref "C765") (pin "1") (pintype "passive"))
      (node (ref "L107") (pin "2") (pinfunction "2_2") (pintype "passive"))
      (node (ref "U12") (pin "15") (pinfunction "B_15") (pintype "passive"))
    )
    (net (code "178") (name "Net-(U12-RF1)") (class "Default")
      (node (ref "C738") (pin "2") (pintype "passive"))
      (node (ref "U12") (pin "9") (pinfunction "RF1_9") (pintype "passive"))
    )
    (net (code "179") (name "Net-(U14-C1)") (class "Default")
      (node (ref "C439") (pin "1") (pintype "passive"))
      (node (ref "C943") (pin "2") (pintype "passive"))
      (node (ref "R647") (pin "2") (pintype "passive"))
      (node (ref "U14") (pin "9") (pinfunction "C1_9") (pintype "passive"))
    )
    (net (code "180") (name "Net-(U14-C2)") (class "Default")
      (node (ref "C391") (pin "1") (pintype "passive"))
      (node (ref "C944") (pin "2") (pintype "passive"))
      (node (ref "R648") (pin "2") (pintype "passive"))
      (node (ref "U14") (pin "8") (pinfunction "C2_8") (pintype "passive"))
    )
    (net (code "181") (name "Net-(U14-C3)") (class "Default")
      (node (ref "C392") (pin "1") (pintype "passive"))
      (node (ref "C945") (pin "2") (pintype "passive"))
      (node (ref "R649") (pin "2") (pintype "passive"))
      (node (ref "U14") (pin "7") (pinfunction "C3_7") (pintype "passive"))
    )
    (net (code "182") (name "Net-(U14-C4)") (class "Default")
      (node (ref "C390") (pin "1") (pintype "passive"))
      (node (ref "C925") (pin "2") (pintype "passive"))
      (node (ref "R641") (pin "2") (pintype "passive"))
      (node (ref "U14") (pin "6") (pinfunction "C4_6") (pintype "passive"))
    )
    (net (code "183") (name "Net-(U14-C5)") (class "Default")
      (node (ref "C437") (pin "1") (pintype "passive"))
      (node (ref "C927") (pin "2") (pintype "passive"))
      (node (ref "R642") (pin "2") (pintype "passive"))
      (node (ref "U14") (pin "5") (pinfunction "C5_5") (pintype "passive"))
    )
    (net (code "184") (name "Net-(U14-C6)") (class "Default")
      (node (ref "C438") (pin "1") (pintype "passive"))
      (node (ref "C929") (pin "2") (pintype "passive"))
      (node (ref "R643") (pin "2") (pintype "passive"))
      (node (ref "U14") (pin "4") (pinfunction "C6_4") (pintype "passive"))
    )
    (net (code "185") (name "Net-(U14-RF1)") (class "Default")
      (node (ref "C738") (pin "1") (pintype "passive"))
      (node (ref "U14") (pin "14") (pinfunction "RF1_14") (pintype "passive"))
    )
    (net (code "186") (name "Net-(U14-RF2)") (class "Default")
      (node (ref "C783") (pin "1") (pintype "passive"))
      (node (ref "U14") (pin "16") (pinfunction "RF2_16") (pintype "passive"))
    )
    (net (code "187") (name "Net-(U14-RF3)") (class "Default")
      (node (ref "C732") (pin "1") (pintype "passive"))
      (node (ref "U14") (pin "18") (pinfunction "RF3_18") (pintype "passive"))
    )
    (net (code "188") (name "Net-(U14-RF4)") (class "Default")
      (node (ref "C751") (pin "1") (pintype "passive"))
      (node (ref "U14") (pin "25") (pinfunction "RF4_25") (pintype "passive"))
    )
    (net (code "189") (name "Net-(U14-RF5)") (class "Default")
      (node (ref "C748") (pin "1") (pintype "passive"))
      (node (ref "U14") (pin "27") (pinfunction "RF5_27") (pintype "passive"))
    )
    (net (code "190") (name "Net-(U14-RF6)") (class "Default")
      (node (ref "C744") (pin "1") (pintype "passive"))
      (node (ref "U14") (pin "29") (pinfunction "RF6_29") (pintype "passive"))
    )
    (net (code "191") (name "Net-(U14-RFC)") (class "Default")
      (node (ref "C5") (pin "2") (pintype "passive"))
      (node (ref "U14") (pin "22") (pinfunction "RFC_22") (pintype "passive"))
    )
    (net (code "192") (name "Net-(U16-C1)") (class "Default")
      (node (ref "C142") (pin "2") (pintype "passive"))
      (node (ref "C933") (pin "1") (pintype "passive"))
      (node (ref "R638") (pin "2") (pintype "passive"))
      (node (ref "U16") (pin "9") (pinfunction "C1_9") (pintype "passive"))
    )
    (net (code "193") (name "Net-(U16-C2)") (class "Default")
      (node (ref "C143") (pin "1") (pintype "passive"))
      (node (ref "C921") (pin "2") (pintype "passive"))
      (node (ref "R639") (pin "2") (pintype "passive"))
      (node (ref "U16") (pin "8") (pinfunction "C2_8") (pintype "passive"))
    )
    (net (code "194") (name "Net-(U16-C3)") (class "Default")
      (node (ref "C144") (pin "1") (pintype "passive"))
      (node (ref "C923") (pin "2") (pintype "passive"))
      (node (ref "R640") (pin "2") (pintype "passive"))
      (node (ref "U16") (pin "7") (pinfunction "C3_7") (pintype "passive"))
    )
    (net (code "195") (name "Net-(U16-C4)") (class "Default")
      (node (ref "C145") (pin "1") (pintype "passive"))
      (node (ref "C935") (pin "2") (pintype "passive"))
      (node (ref "R644") (pin "2") (pintype "passive"))
      (node (ref "U16") (pin "6") (pinfunction "C4_6") (pintype "passive"))
    )
    (net (code "196") (name "Net-(U16-C5)") (class "Default")
      (node (ref "C146") (pin "1") (pintype "passive"))
      (node (ref "C937") (pin "2") (pintype "passive"))
      (node (ref "R645") (pin "2") (pintype "passive"))
      (node (ref "U16") (pin "5") (pinfunction "C5_5") (pintype "passive"))
    )
    (net (code "197") (name "Net-(U16-C6)") (class "Default")
      (node (ref "C147") (pin "1") (pintype "passive"))
      (node (ref "C939") (pin "2") (pintype "passive"))
      (node (ref "R646") (pin "2") (pintype "passive"))
      (node (ref "U16") (pin "4") (pinfunction "C6_4") (pintype "passive"))
    )
    (net (code "198") (name "Net-(U16-RF1)") (class "Default")
      (node (ref "C794") (pin "2") (pintype "passive"))
      (node (ref "U16") (pin "14") (pinfunction "RF1_14") (pintype "passive"))
    )
    (net (code "199") (name "Net-(U16-RF2)") (class "Default")
      (node (ref "C800") (pin "2") (pintype "passive"))
      (node (ref "U16") (pin "16") (pinfunction "RF2_16") (pintype "passive"))
    )
    (net (code "200") (name "Net-(U16-RF3)") (class "Default")
      (node (ref "C806") (pin "2") (pintype "passive"))
      (node (ref "U16") (pin "18") (pinfunction "RF3_18") (pintype "passive"))
    )
    (net (code "201") (name "Net-(U16-RF4)") (class "Default")
      (node (ref "C775") (pin "2") (pintype "passive"))
      (node (ref "U16") (pin "25") (pinfunction "RF4_25") (pintype "passive"))
    )
    (net (code "202") (name "Net-(U16-RF5)") (class "Default")
      (node (ref "C781") (pin "2") (pintype "passive"))
      (node (ref "U16") (pin "27") (pinfunction "RF5_27") (pintype "passive"))
    )
    (net (code "203") (name "Net-(U16-RF6)") (class "Default")
      (node (ref "C788") (pin "2") (pintype "passive"))
      (node (ref "U16") (pin "29") (pinfunction "RF6_29") (pintype "passive"))
    )
    (net (code "204") (name "Net-(U16-RFC)") (class "Default")
      (node (ref "C772") (pin "1") (pintype "passive"))
      (node (ref "U16") (pin "22") (pinfunction "RFC_22") (pintype "passive"))
    )
    (net (code "205") (name "Net-(U19-A)") (class "Default")
      (node (ref "C804") (pin "1") (pintype "passive"))
      (node (ref "L112") (pin "2") (pinfunction "2_2") (pintype "passive"))
      (node (ref "U19") (pin "16") (pinfunction "A_16") (pintype "passive"))
    )
    (net (code "206") (name "Net-(U19-B)") (class "Default")
      (node (ref "C803") (pin "1") (pintype "passive"))
      (node (ref "L111") (pin "2") (pinfunction "2_2") (pintype "passive"))
      (node (ref "U19") (pin "15") (pinfunction "B_15") (pintype "passive"))
    )
    (net (code "207") (name "Net-(U19-RF1)") (class "Default")
      (node (ref "C744") (pin "2") (pintype "passive"))
      (node (ref "U19") (pin "9") (pinfunction "RF1_9") (pintype "passive"))
    )
    (net (code "208") (name "Net-(U21-A)") (class "Default")
      (node (ref "C903") (pin "1") (pintype "passive"))
      (node (ref "L116") (pin "2") (pinfunction "2_2") (pintype "passive"))
      (node (ref "U21") (pin "16") (pinfunction "A_16") (pintype "passive"))
    )
    (net (code "209") (name "Net-(U21-B)") (class "Default")
      (node (ref "C902") (pin "1") (pintype "passive"))
      (node (ref "L115") (pin "2") (pinfunction "2_2") (pintype "passive"))
      (node (ref "U21") (pin "15") (pinfunction "B_15") (pintype "passive"))
    )
    (net (code "210") (name "Net-(U21-RF1)") (class "Default")
      (node (ref "C748") (pin "2") (pintype "passive"))
      (node (ref "U21") (pin "9") (pinfunction "RF1_9") (pintype "passive"))
    )
    (net (code "211") (name "Net-(U24-A)") (class "Default")
      (node (ref "C911") (pin "1") (pintype "passive"))
      (node (ref "L209") (pin "2") (pinfunction "2_2") (pintype "passive"))
      (node (ref "U24") (pin "16") (pinfunction "A_16") (pintype "passive"))
    )
    (net (code "212") (name "Net-(U24-B)") (class "Default")
      (node (ref "C910") (pin "1") (pintype "passive"))
      (node (ref "L208") (pin "2") (pinfunction "2_2") (pintype "passive"))
      (node (ref "U24") (pin "15") (pinfunction "B_15") (pintype "passive"))
    )
    (net (code "213") (name "Net-(U24-RF1)") (class "Default")
      (node (ref "C751") (pin "2") (pintype "passive"))
      (node (ref "U24") (pin "9") (pinfunction "RF1_9") (pintype "passive"))
    )
    (net (code "214") (name "Net-(U109-A)") (class "Default")
      (node (ref "C779") (pin "1") (pintype "passive"))
      (node (ref "L102") (pin "2") (pinfunction "2_2") (pintype "passive"))
      (node (ref "U109") (pin "16") (pinfunction "A_16") (pintype "passive"))
    )
    (net (code "215") (name "Net-(U109-B)") (class "Default")
      (node (ref "C778") (pin "1") (pintype "passive"))
      (node (ref "L98") (pin "2") (pinfunction "2_2") (pintype "passive"))
      (node (ref "U109") (pin "15") (pinfunction "B_15") (pintype "passive"))
    )
    (net (code "216") (name "Net-(U109-RF1)") (class "Default")
      (node (ref "C777") (pin "2") (pintype "passive"))
      (node (ref "U109") (pin "9") (pinfunction "RF1_9") (pintype "passive"))
    )
    (net (code "217") (name "Net-(U113-A)") (class "Default")
      (node (ref "C759") (pin "1") (pintype "passive"))
      (node (ref "L106") (pin "2") (pinfunction "2_2") (pintype "passive"))
      (node (ref "U113") (pin "16") (pinfunction "A_16") (pintype "passive"))
    )
    (net (code "218") (name "Net-(U113-B)") (class "Default")
      (node (ref "C758") (pin "1") (pintype "passive"))
      (node (ref "L105") (pin "2") (pinfunction "2_2") (pintype "passive"))
      (node (ref "U113") (pin "15") (pinfunction "B_15") (pintype "passive"))
    )
    (net (code "219") (name "Net-(U113-RF1)") (class "Default")
      (node (ref "C784") (pin "2") (pintype "passive"))
      (node (ref "U113") (pin "9") (pinfunction "RF1_9") (pintype "passive"))
    )
    (net (code "220") (name "Net-(U126-A)") (class "Default")
      (node (ref "C791") (pin "1") (pintype "passive"))
      (node (ref "L110") (pin "2") (pinfunction "2_2") (pintype "passive"))
      (node (ref "U126") (pin "16") (pinfunction "A_16") (pintype "passive"))
    )
    (net (code "221") (name "Net-(U126-B)") (class "Default")
      (node (ref "C786") (pin "1") (pintype "passive"))
      (node (ref "L109") (pin "2") (pinfunction "2_2") (pintype "passive"))
      (node (ref "U126") (pin "15") (pinfunction "B_15") (pintype "passive"))
    )
    (net (code "222") (name "Net-(U126-RF1)") (class "Default")
      (node (ref "C790") (pin "2") (pintype "passive"))
      (node (ref "U126") (pin "9") (pinfunction "RF1_9") (pintype "passive"))
    )
    (net (code "223") (name "Net-(U134-A)") (class "Default")
      (node (ref "C810") (pin "1") (pintype "passive"))
      (node (ref "L114") (pin "2") (pinfunction "2_2") (pintype "passive"))
      (node (ref "U134") (pin "16") (pinfunction "A_16") (pintype "passive"))
    )
    (net (code "224") (name "Net-(U134-B)") (class "Default")
      (node (ref "C809") (pin "1") (pintype "passive"))
      (node (ref "L113") (pin "2") (pinfunction "2_2") (pintype "passive"))
      (node (ref "U134") (pin "15") (pinfunction "B_15") (pintype "passive"))
    )
    (net (code "225") (name "Net-(U134-RF1)") (class "Default")
      (node (ref "C796") (pin "2") (pintype "passive"))
      (node (ref "U134") (pin "9") (pinfunction "RF1_9") (pintype "passive"))
    )
    (net (code "226") (name "Net-(U135-A)") (class "Default")
      (node (ref "C905") (pin "1") (pintype "passive"))
      (node (ref "L207") (pin "2") (pinfunction "2_2") (pintype "passive"))
      (node (ref "U135") (pin "16") (pinfunction "A_16") (pintype "passive"))
    )
    (net (code "227") (name "Net-(U135-B)") (class "Default")
      (node (ref "C904") (pin "1") (pintype "passive"))
      (node (ref "L204") (pin "2") (pinfunction "2_2") (pintype "passive"))
      (node (ref "U135") (pin "15") (pinfunction "B_15") (pintype "passive"))
    )
    (net (code "228") (name "Net-(U135-RF1)") (class "Default")
      (node (ref "C802") (pin "2") (pintype "passive"))
      (node (ref "U135") (pin "9") (pinfunction "RF1_9") (pintype "passive"))
    )
    (net (code "229") (name "Net-(U136-A)") (class "Default")
      (node (ref "C913") (pin "1") (pintype "passive"))
      (node (ref "L211") (pin "2") (pinfunction "2_2") (pintype "passive"))
      (node (ref "U136") (pin "16") (pinfunction "A_16") (pintype "passive"))
    )
    (net (code "230") (name "Net-(U136-B)") (class "Default")
      (node (ref "C912") (pin "1") (pintype "passive"))
      (node (ref "L210") (pin "2") (pinfunction "2_2") (pintype "passive"))
      (node (ref "U136") (pin "15") (pinfunction "B_15") (pintype "passive"))
    )
    (net (code "231") (name "Net-(U136-RF1)") (class "Default")
      (node (ref "C808") (pin "2") (pintype "passive"))
      (node (ref "U136") (pin "9") (pinfunction "RF1_9") (pintype "passive"))
    )
    (net (code "232") (name "unconnected-(U14-CP1-Pad36)") (class "Default")
      (node (ref "U14") (pin "36") (pinfunction "CP1_36") (pintype "passive"))
    )
    (net (code "233") (name "unconnected-(U14-CP2-Pad1)") (class "Default")
      (node (ref "U14") (pin "1") (pinfunction "CP2_1") (pintype "passive"))
    )
    (net (code "234") (name "unconnected-(U14-NC-Pad3)") (class "Default")
      (node (ref "U14") (pin "3") (pinfunction "NC_3") (pintype "passive"))
    )
    (net (code "235") (name "unconnected-(U14-NC-Pad10)") (class "Default")
      (node (ref "U14") (pin "10") (pinfunction "NC_10") (pintype "passive"))
    )
    (net (code "236") (name "unconnected-(U14-NC-Pad12)") (class "Default")
      (node (ref "U14") (pin "12") (pinfunction "NC_12") (pintype "passive"))
    )
    (net (code "237") (name "unconnected-(U14-NC-Pad20)") (class "Default")
      (node (ref "U14") (pin "20") (pinfunction "NC_20") (pintype "passive"))
    )
    (net (code "238") (name "unconnected-(U14-NC-Pad31)") (class "Default")
      (node (ref "U14") (pin "31") (pinfunction "NC_31") (pintype "passive"))
    )
    (net (code "239") (name "unconnected-(U14-NC-Pad34)") (class "Default")
      (node (ref "U14") (pin "34") (pinfunction "NC_34") (pintype "passive"))
    )
    (net (code "240") (name "unconnected-(U14-VCC-Pad35)") (class "Default")
      (node (ref "U14") (pin "35") (pinfunction "VCC_35") (pintype "passive"))
    )
    (net (code "241") (name "unconnected-(U14-VEE-Pad2)") (class "Default")
      (node (ref "U14") (pin "2") (pinfunction "VEE_2") (pintype "passive"))
    )
    (net (code "242") (name "unconnected-(U16-CP1-Pad36)") (class "Default")
      (node (ref "U16") (pin "36") (pinfunction "CP1_36") (pintype "passive"))
    )
    (net (code "243") (name "unconnected-(U16-CP2-Pad1)") (class "Default")
      (node (ref "U16") (pin "1") (pinfunction "CP2_1") (pintype "passive"))
    )
    (net (code "244") (name "unconnected-(U16-NC-Pad3)") (class "Default")
      (node (ref "U16") (pin "3") (pinfunction "NC_3") (pintype "passive"))
    )
    (net (code "245") (name "unconnected-(U16-NC-Pad10)") (class "Default")
      (node (ref "U16") (pin "10") (pinfunction "NC_10") (pintype "passive"))
    )
    (net (code "246") (name "unconnected-(U16-NC-Pad12)") (class "Default")
      (node (ref "U16") (pin "12") (pinfunction "NC_12") (pintype "passive"))
    )
    (net (code "247") (name "unconnected-(U16-NC-Pad20)") (class "Default")
      (node (ref "U16") (pin "20") (pinfunction "NC_20") (pintype "passive"))
    )
    (net (code "248") (name "unconnected-(U16-NC-Pad31)") (class "Default")
      (node (ref "U16") (pin "31") (pinfunction "NC_31") (pintype "passive"))
    )
    (net (code "249") (name "unconnected-(U16-NC-Pad34)") (class "Default")
      (node (ref "U16") (pin "34") (pinfunction "NC_34") (pintype "passive"))
    )
    (net (code "250") (name "unconnected-(U16-VCC-Pad35)") (class "Default")
      (node (ref "U16") (pin "35") (pinfunction "VCC_35") (pintype "passive"))
    )
    (net (code "251") (name "unconnected-(U16-VEE-Pad2)") (class "Default")
      (node (ref "U16") (pin "2") (pinfunction "VEE_2") (pintype "passive"))
    )
  )
)
